# SCH_DV_MR_rev_modbus_18_16_2022-01-16.net
KiCad netlist of a schematic drawn in EasyEDA
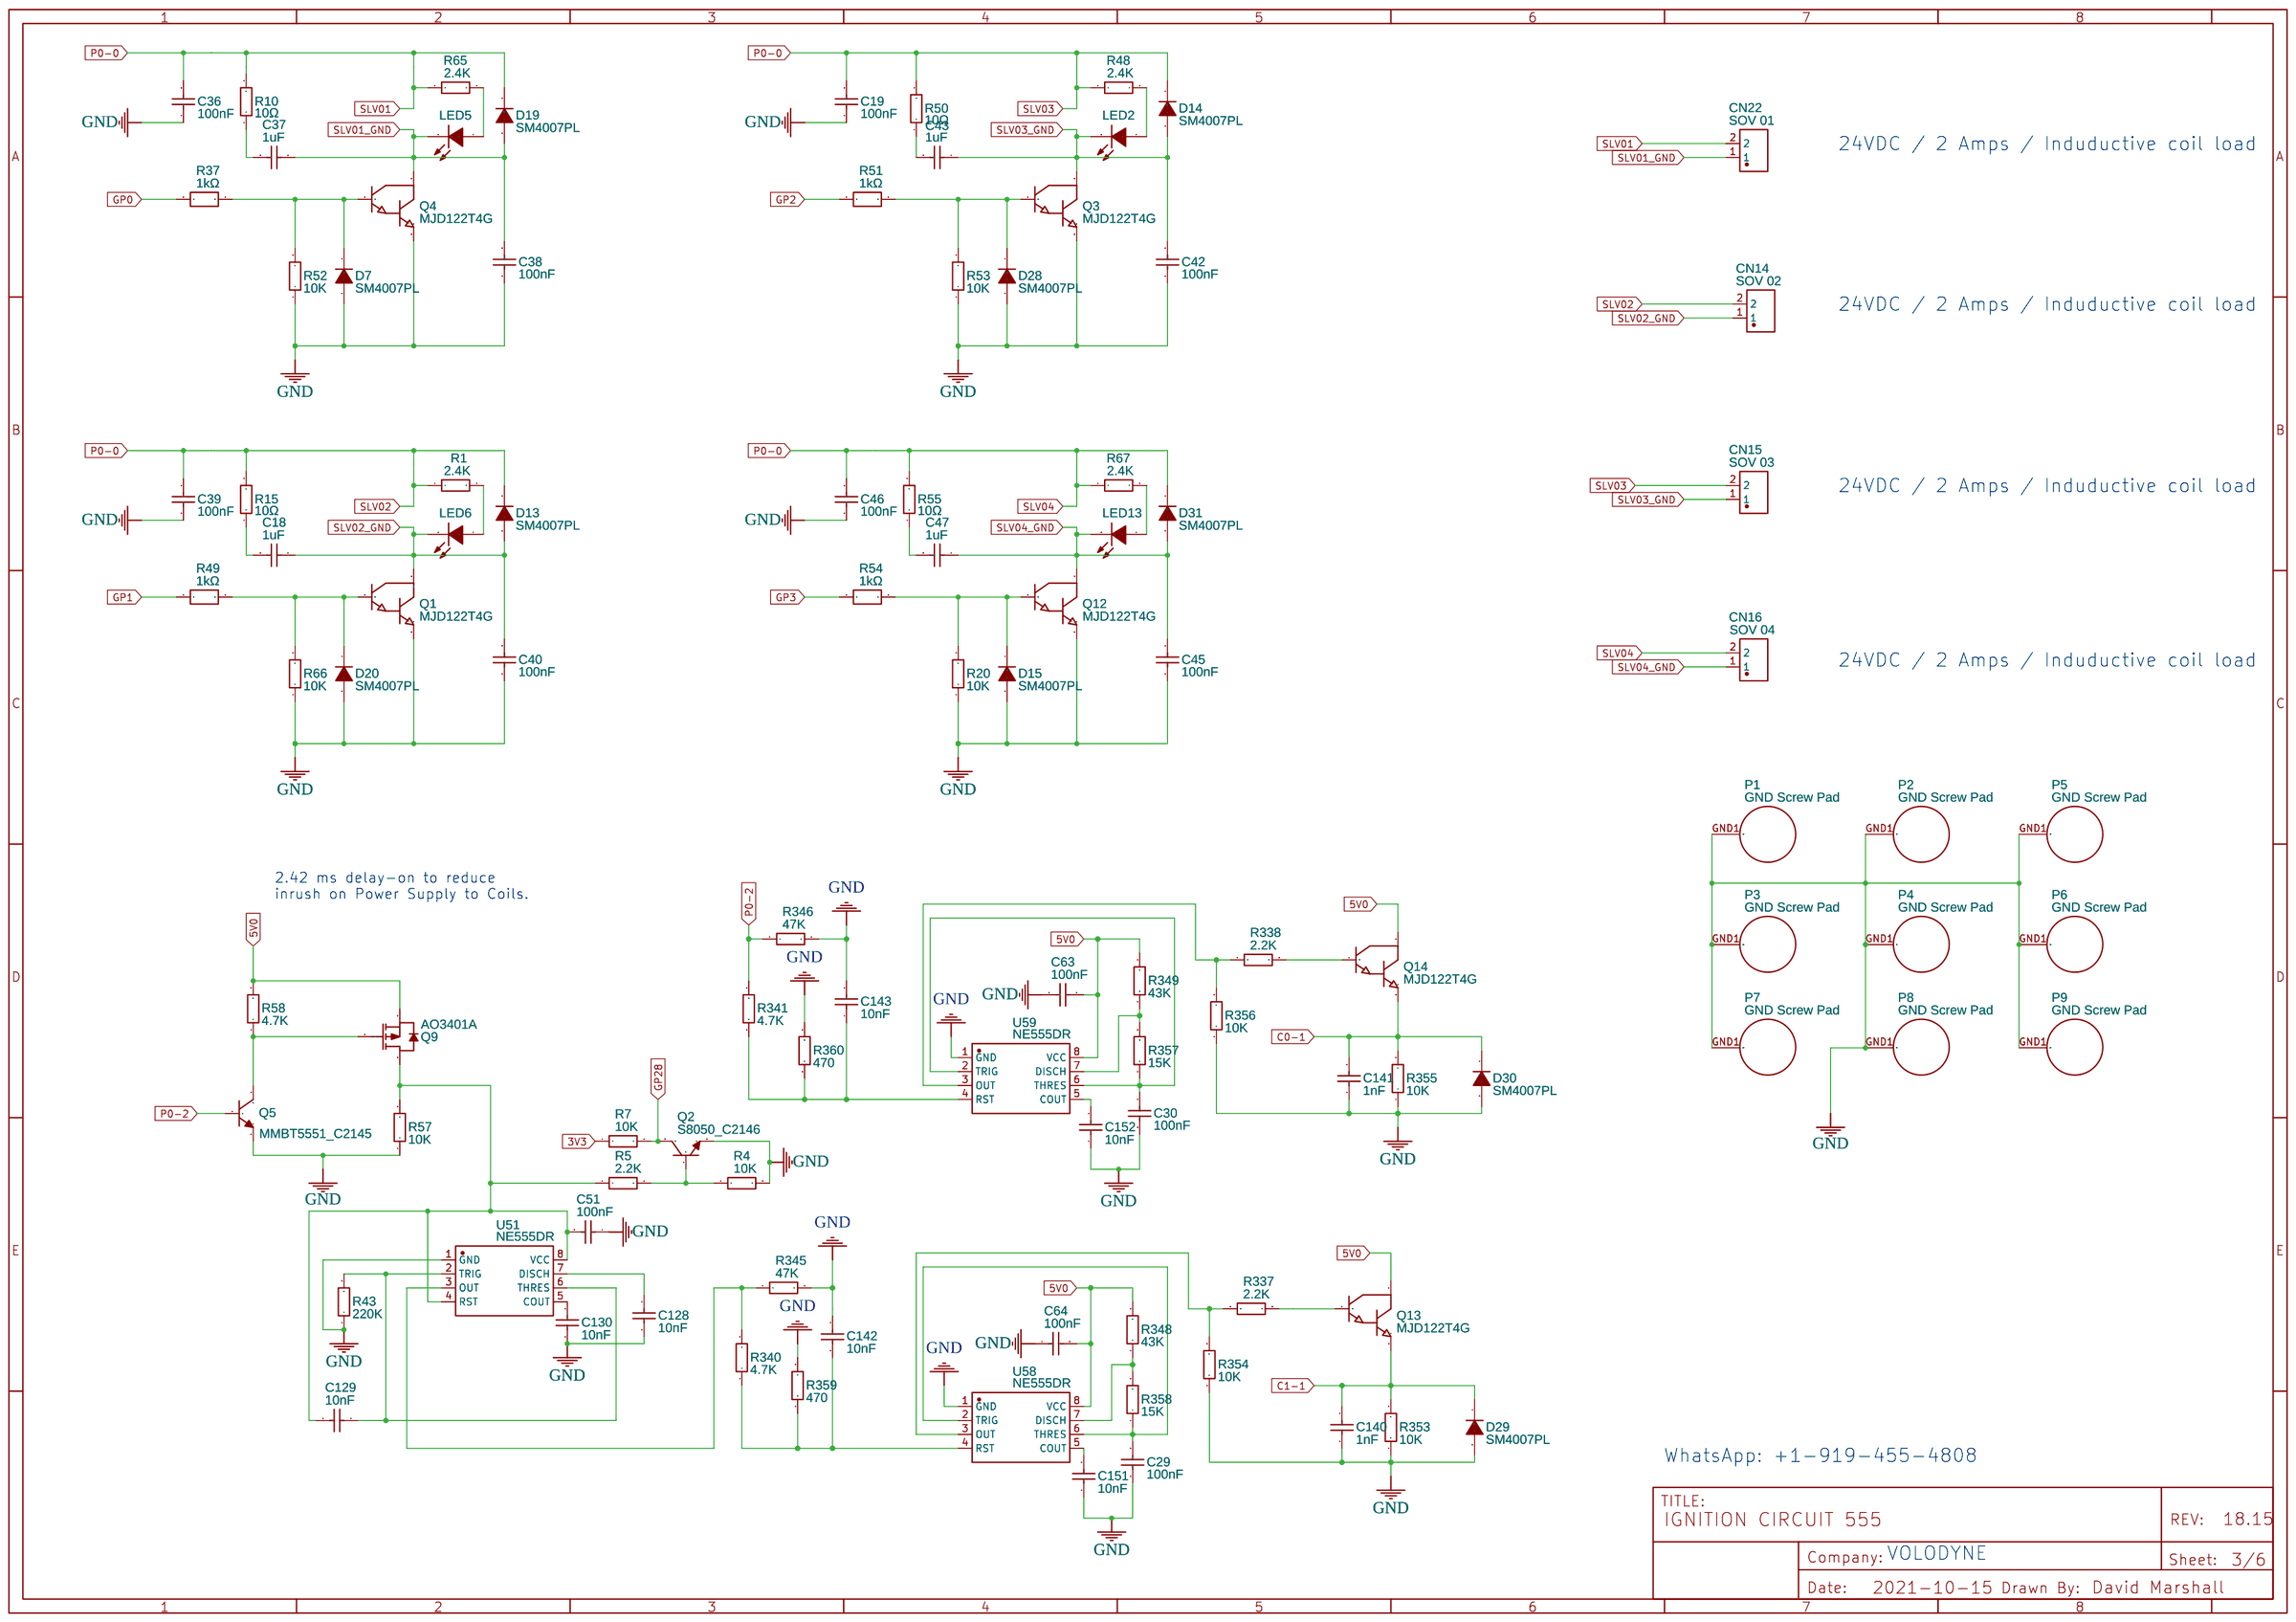
[diagram p0: DV_MR_rev_18.16_modbus_ADC_555 COILER TIMERS]
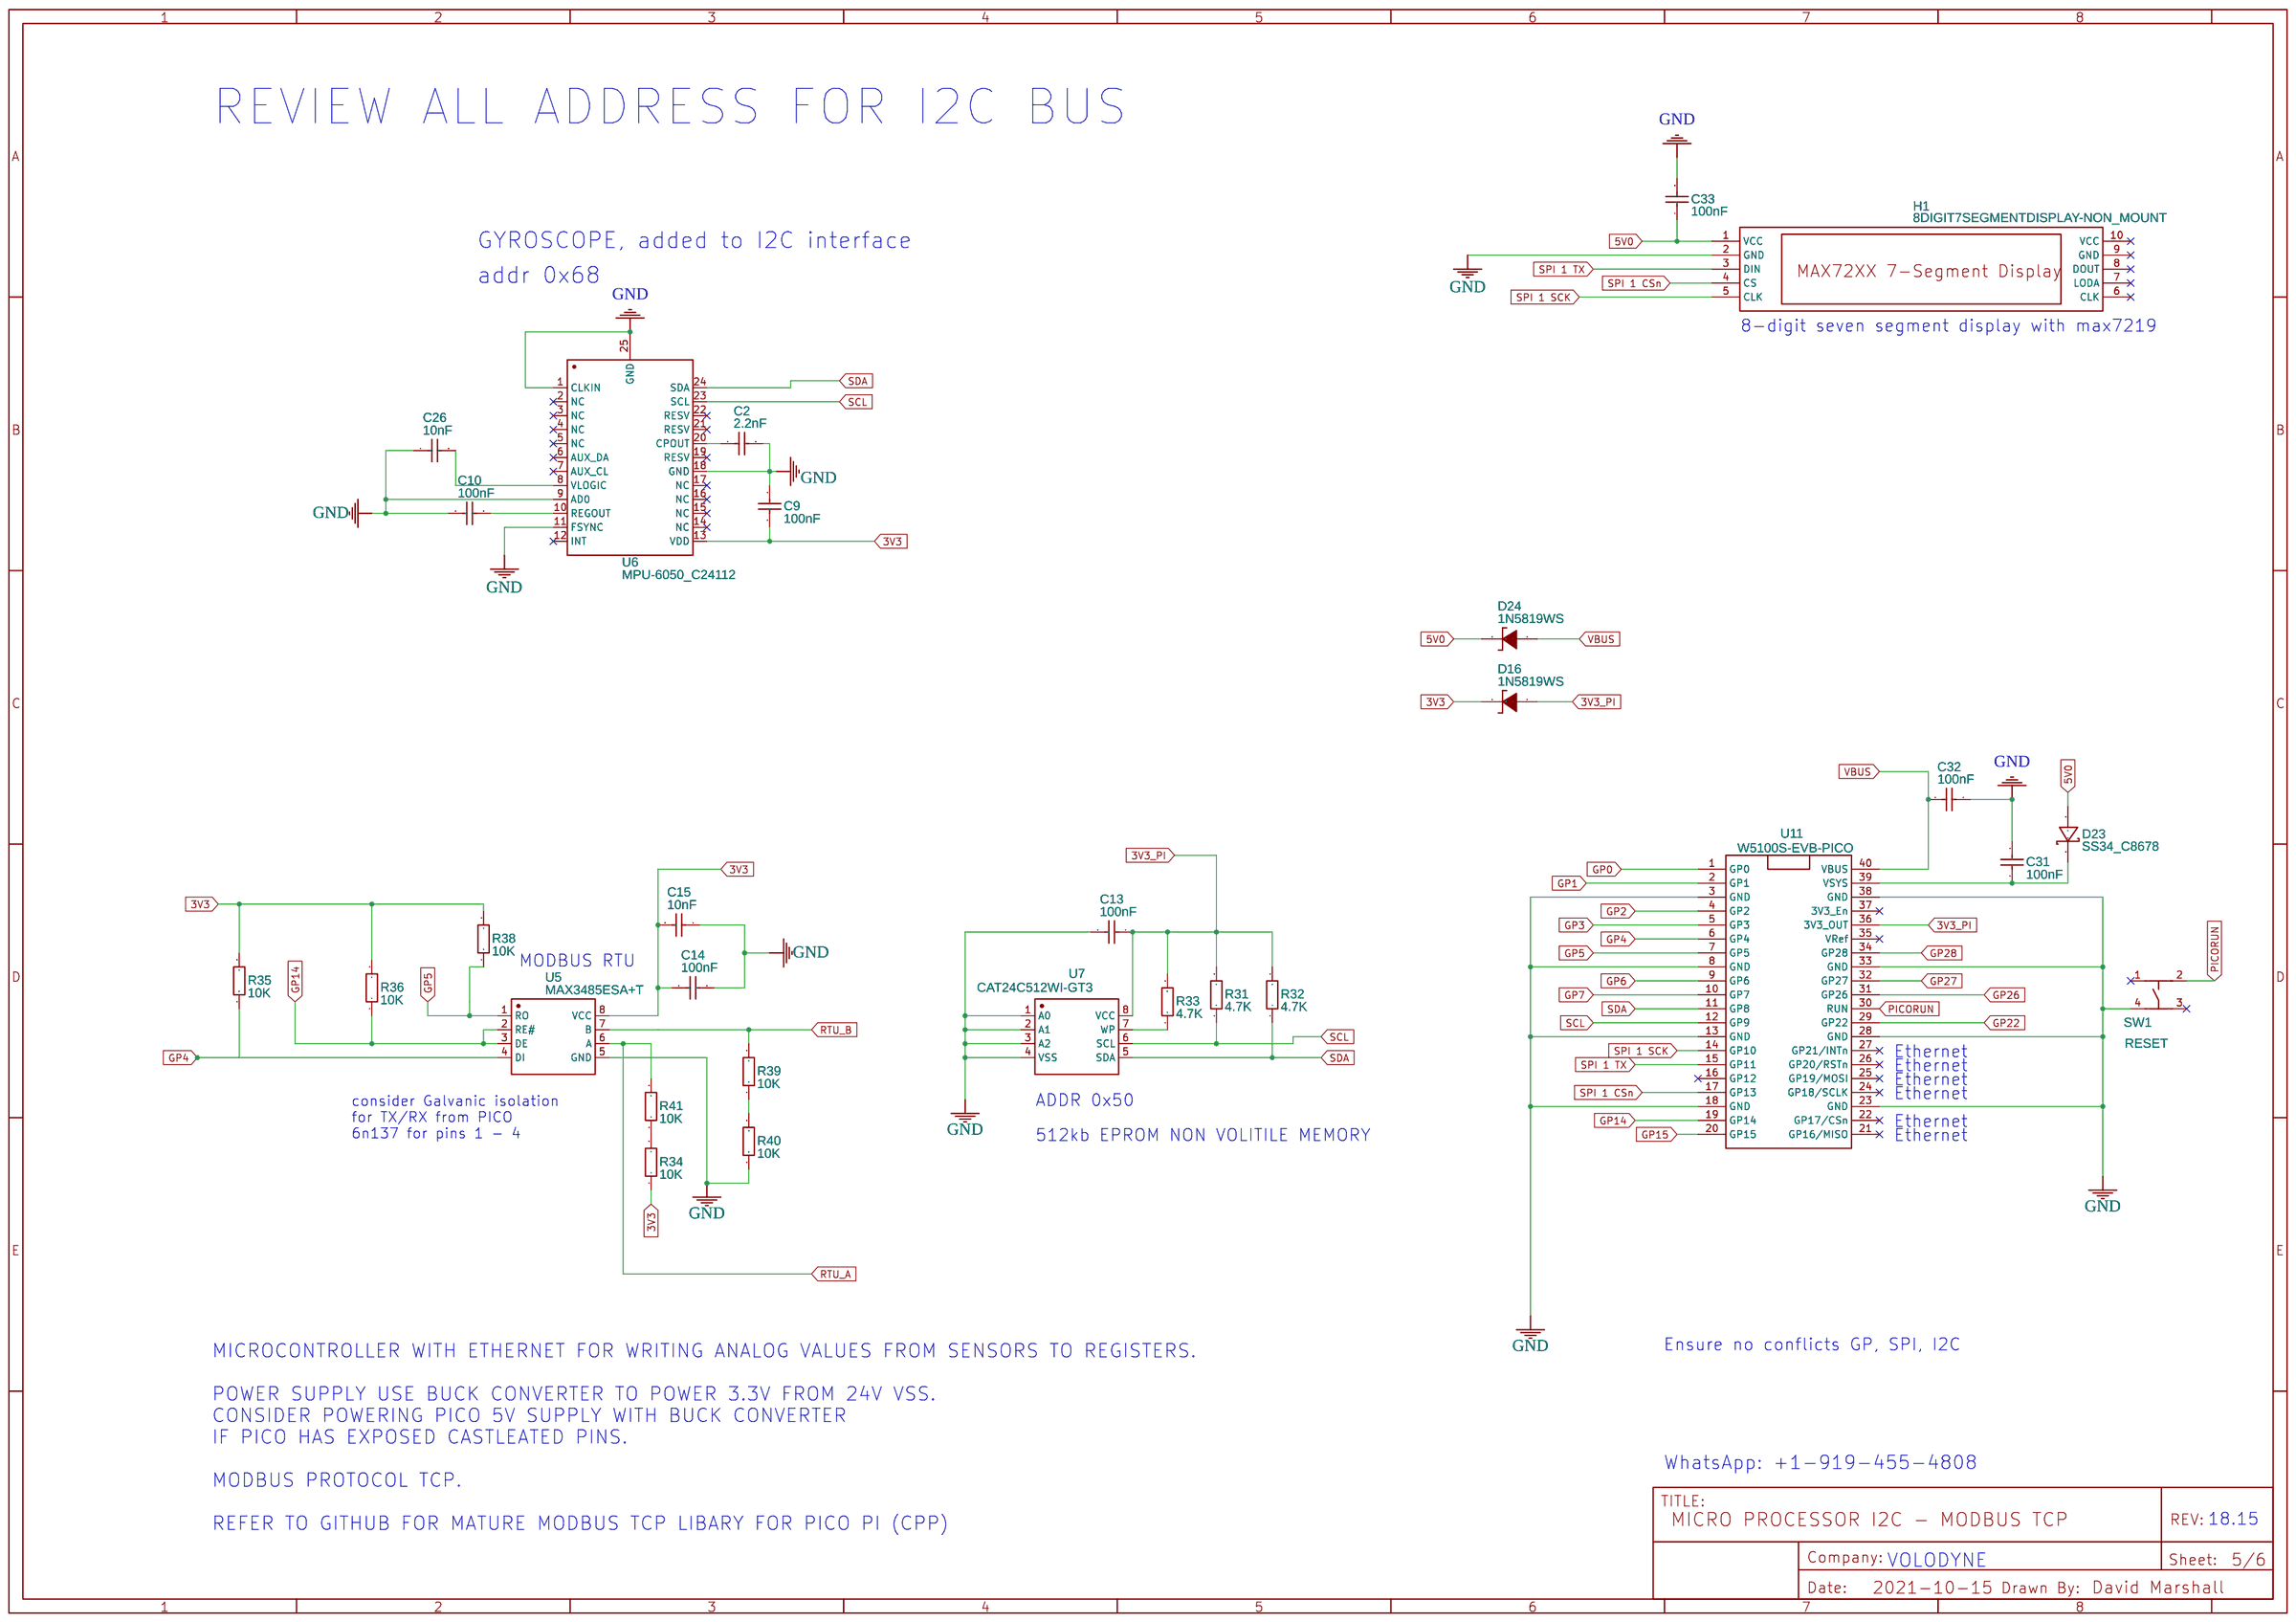
[diagram p1: DV_MR_rev_18.16_modbus_ADC_PICO PI MCU]
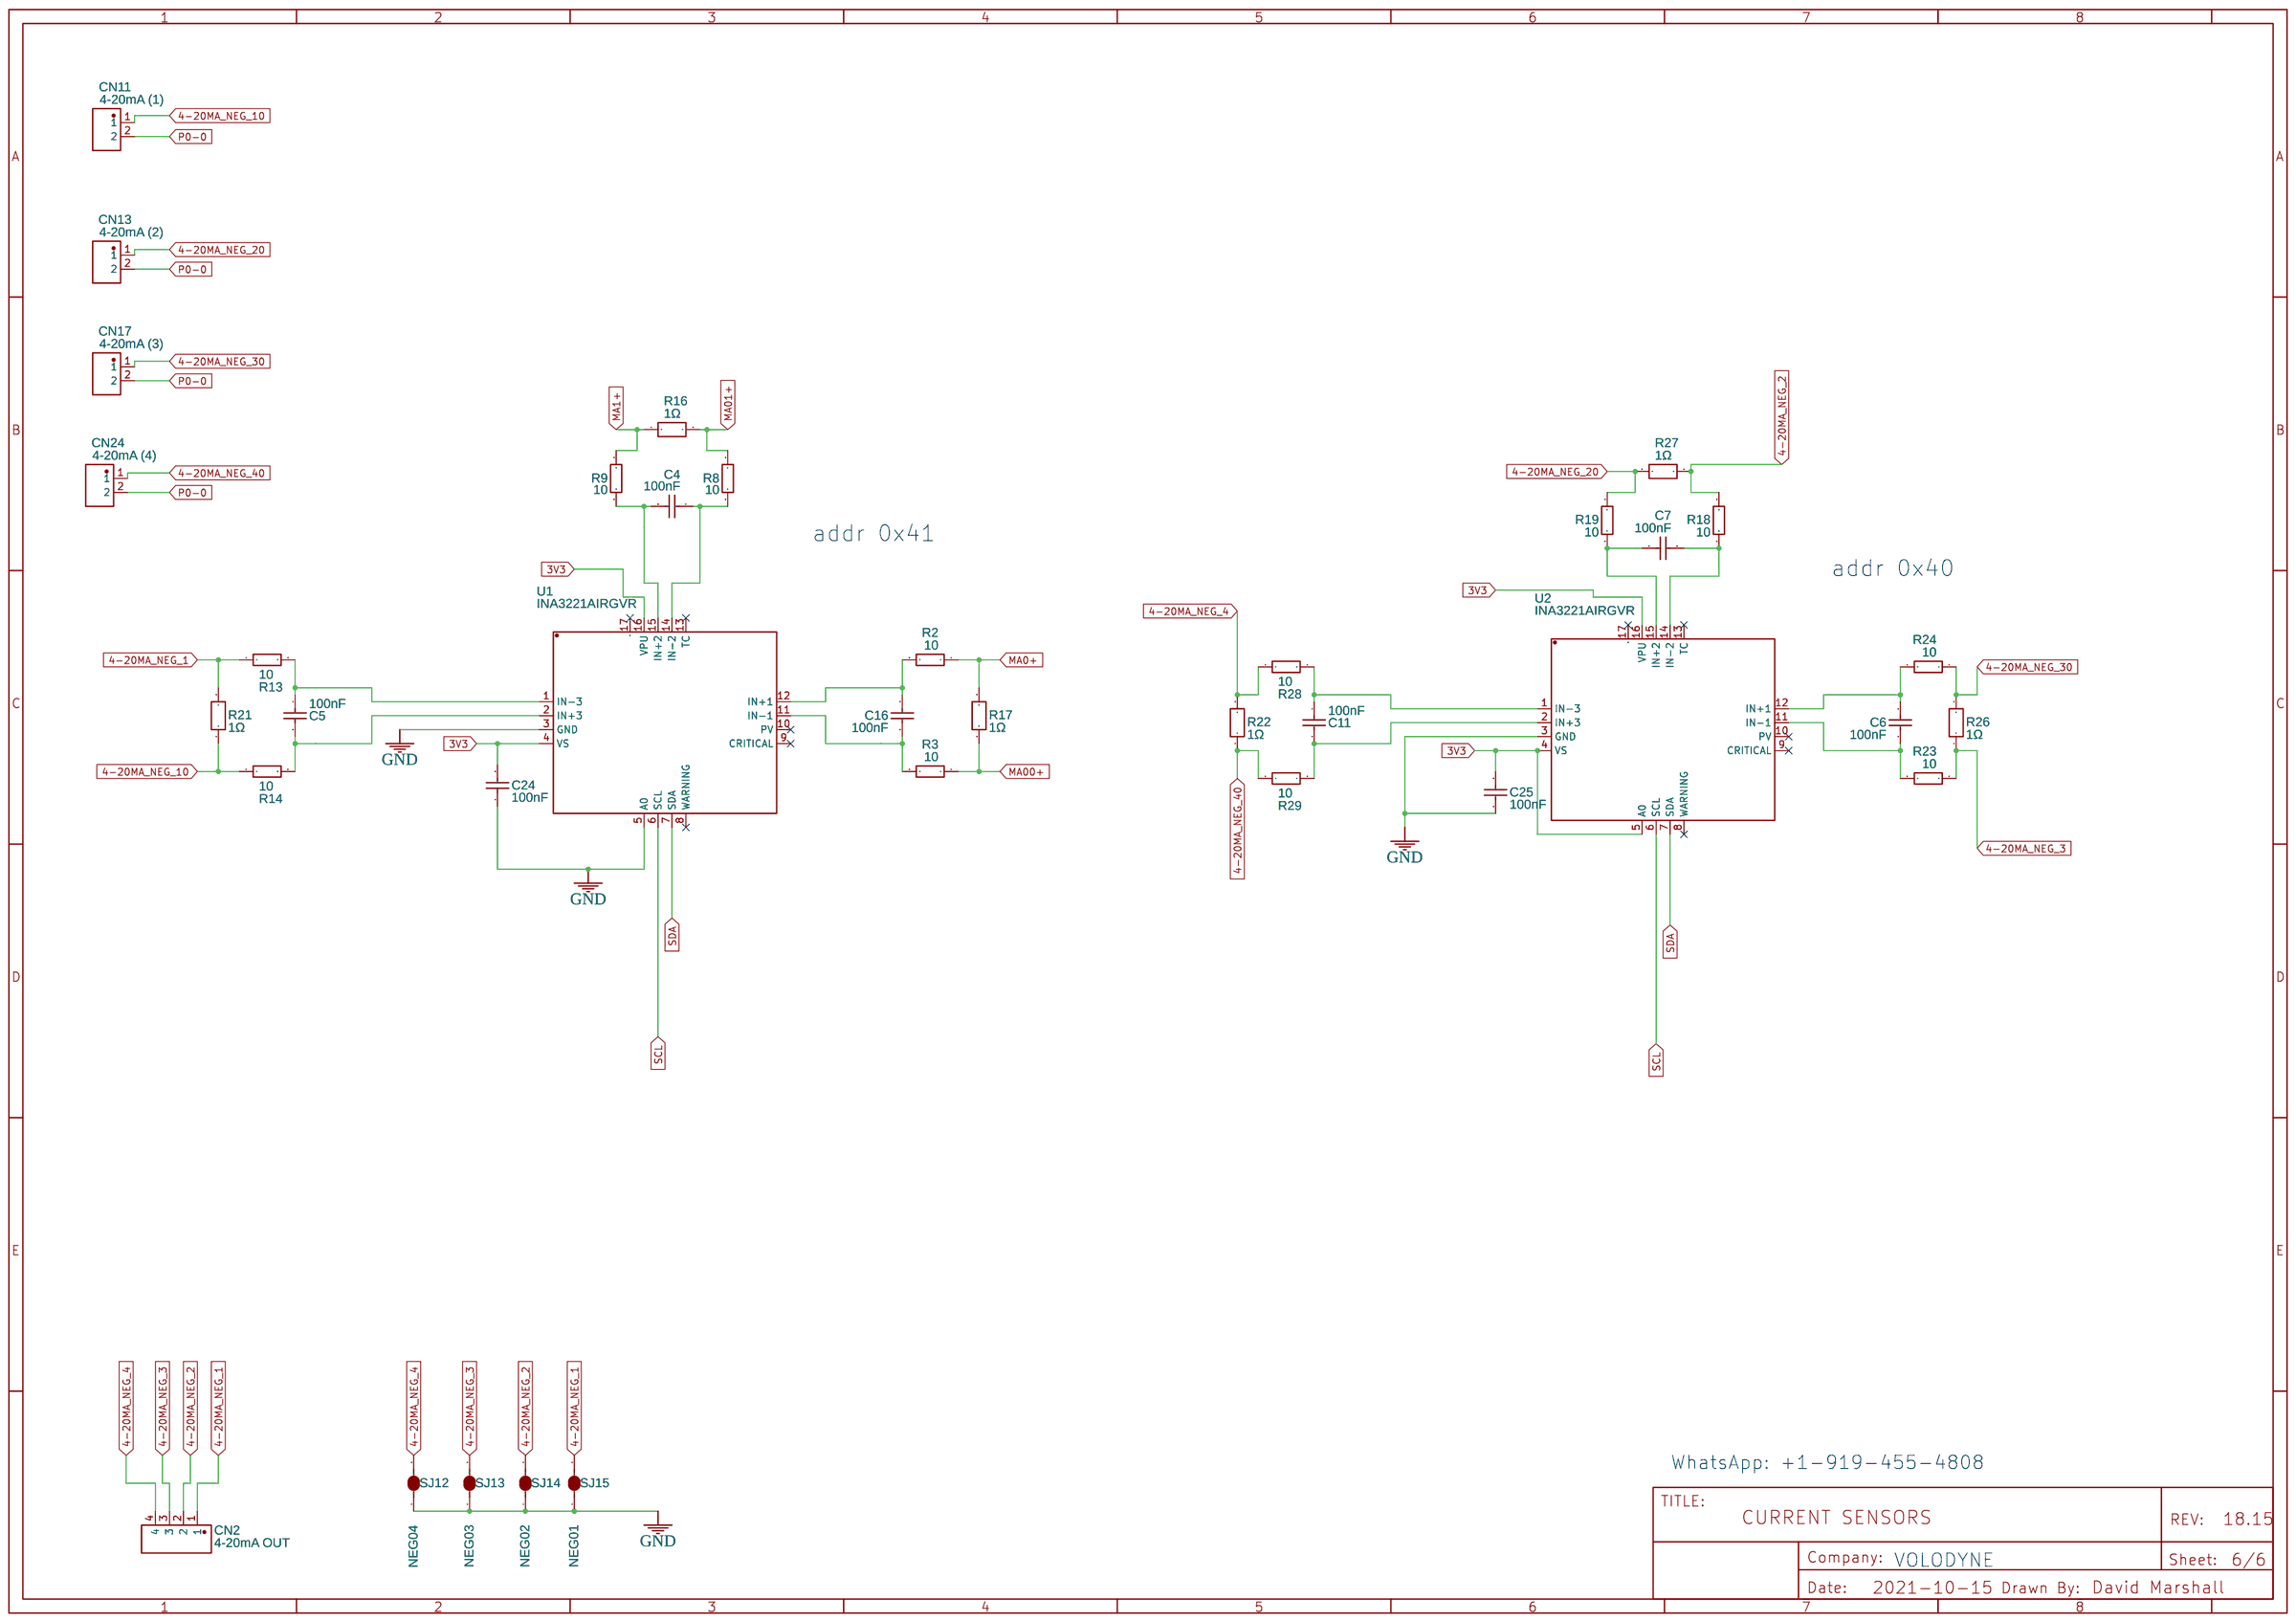
[diagram p2: DV_MR_rev_18.16_modbus_ADC_CURRENT SENSORS]
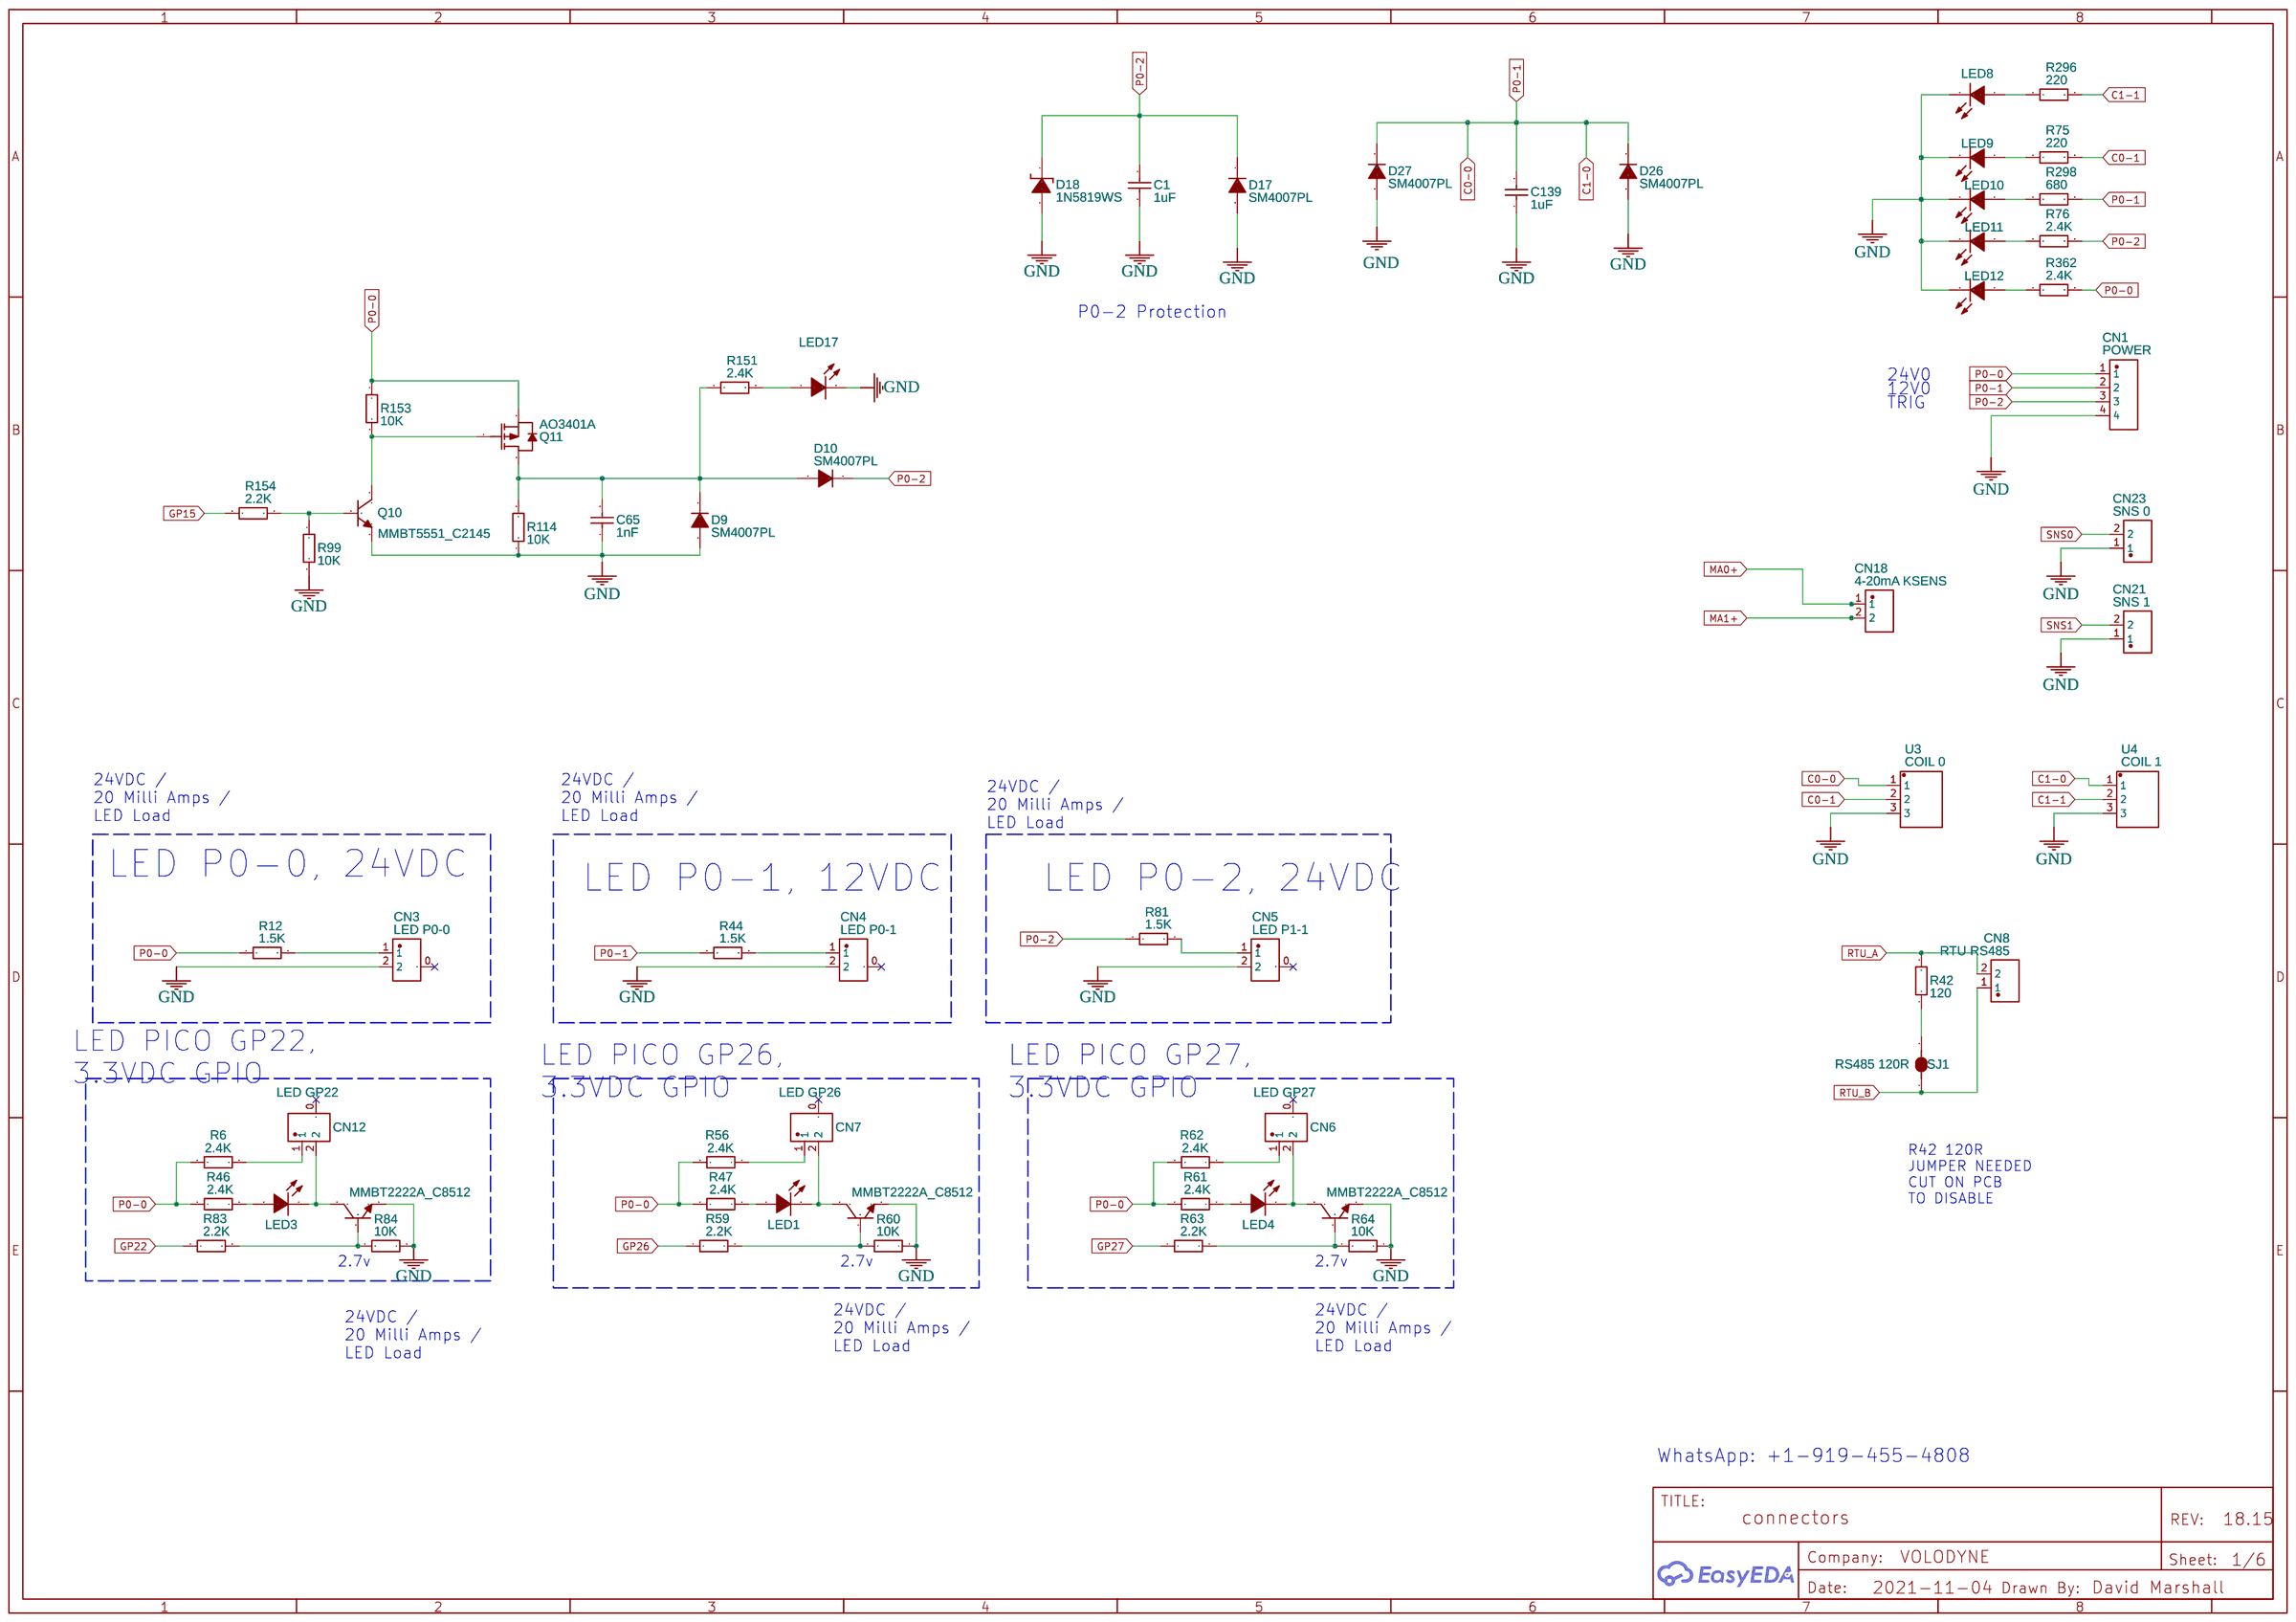
[diagram p3: DV_MR_rev_18.16_modbus_ADC_Connectors]
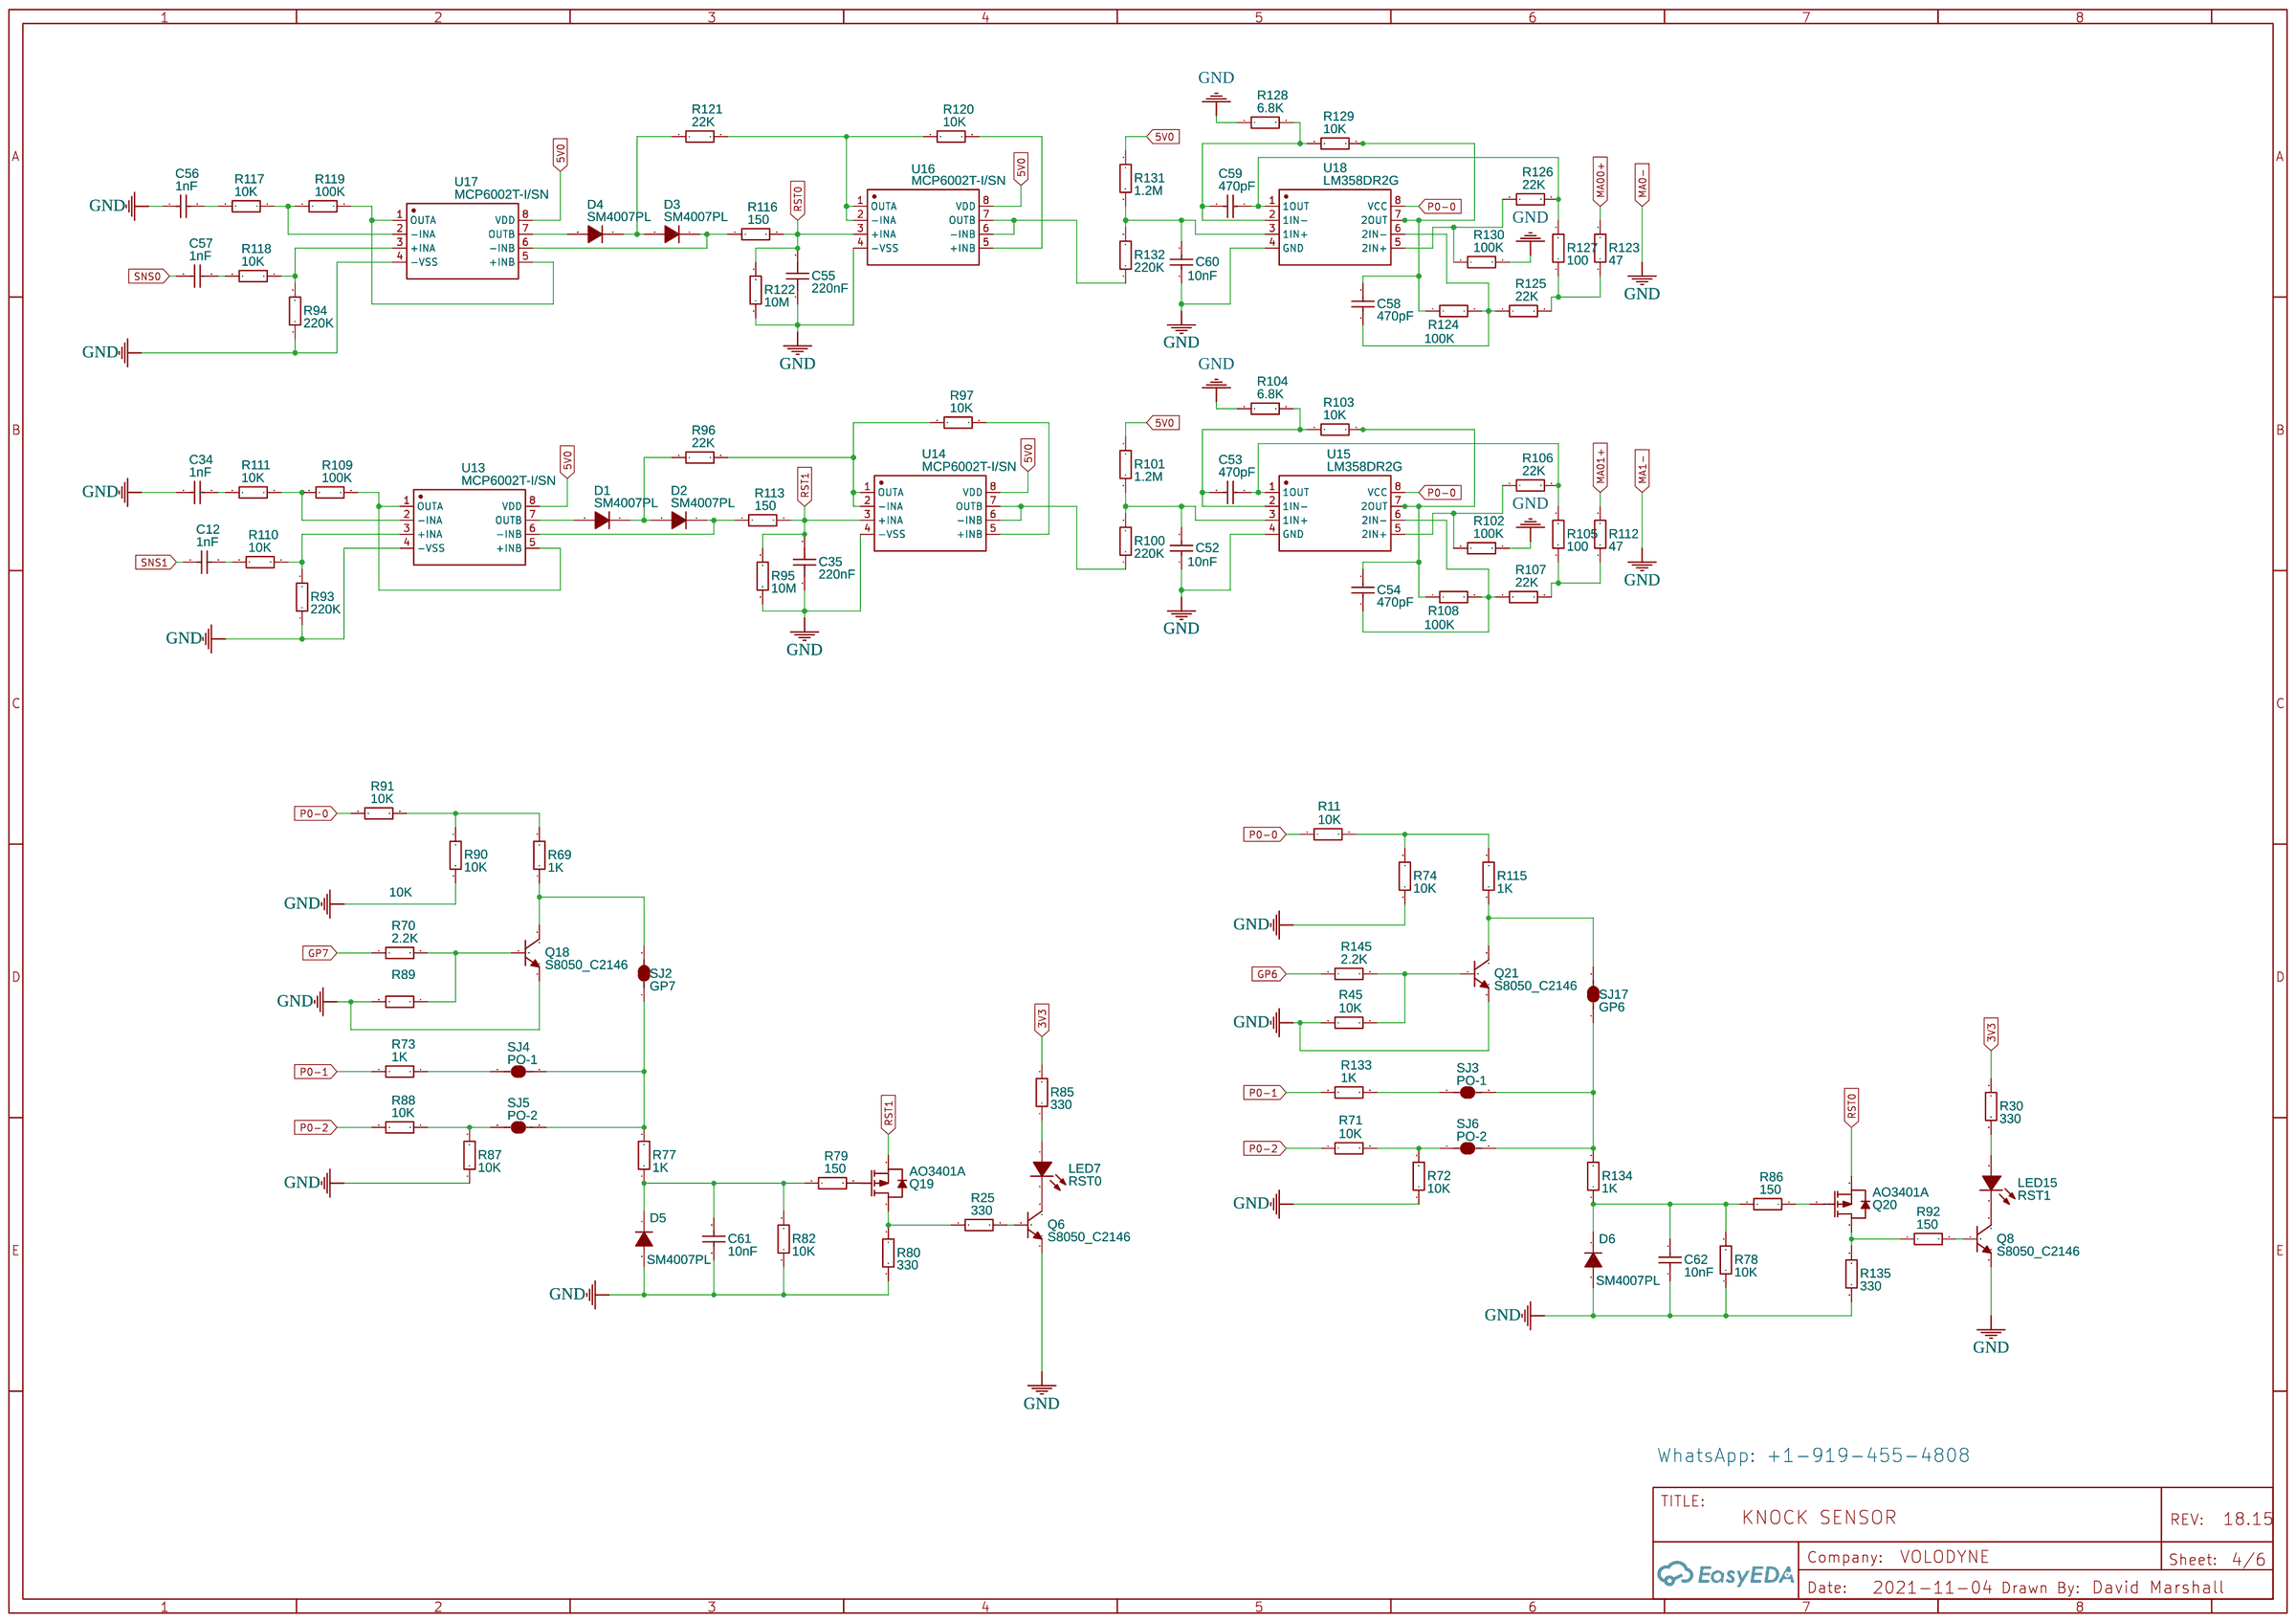
[diagram p4: DV_MR_rev_18.16_modbus_ADC_IGN SENSORS]
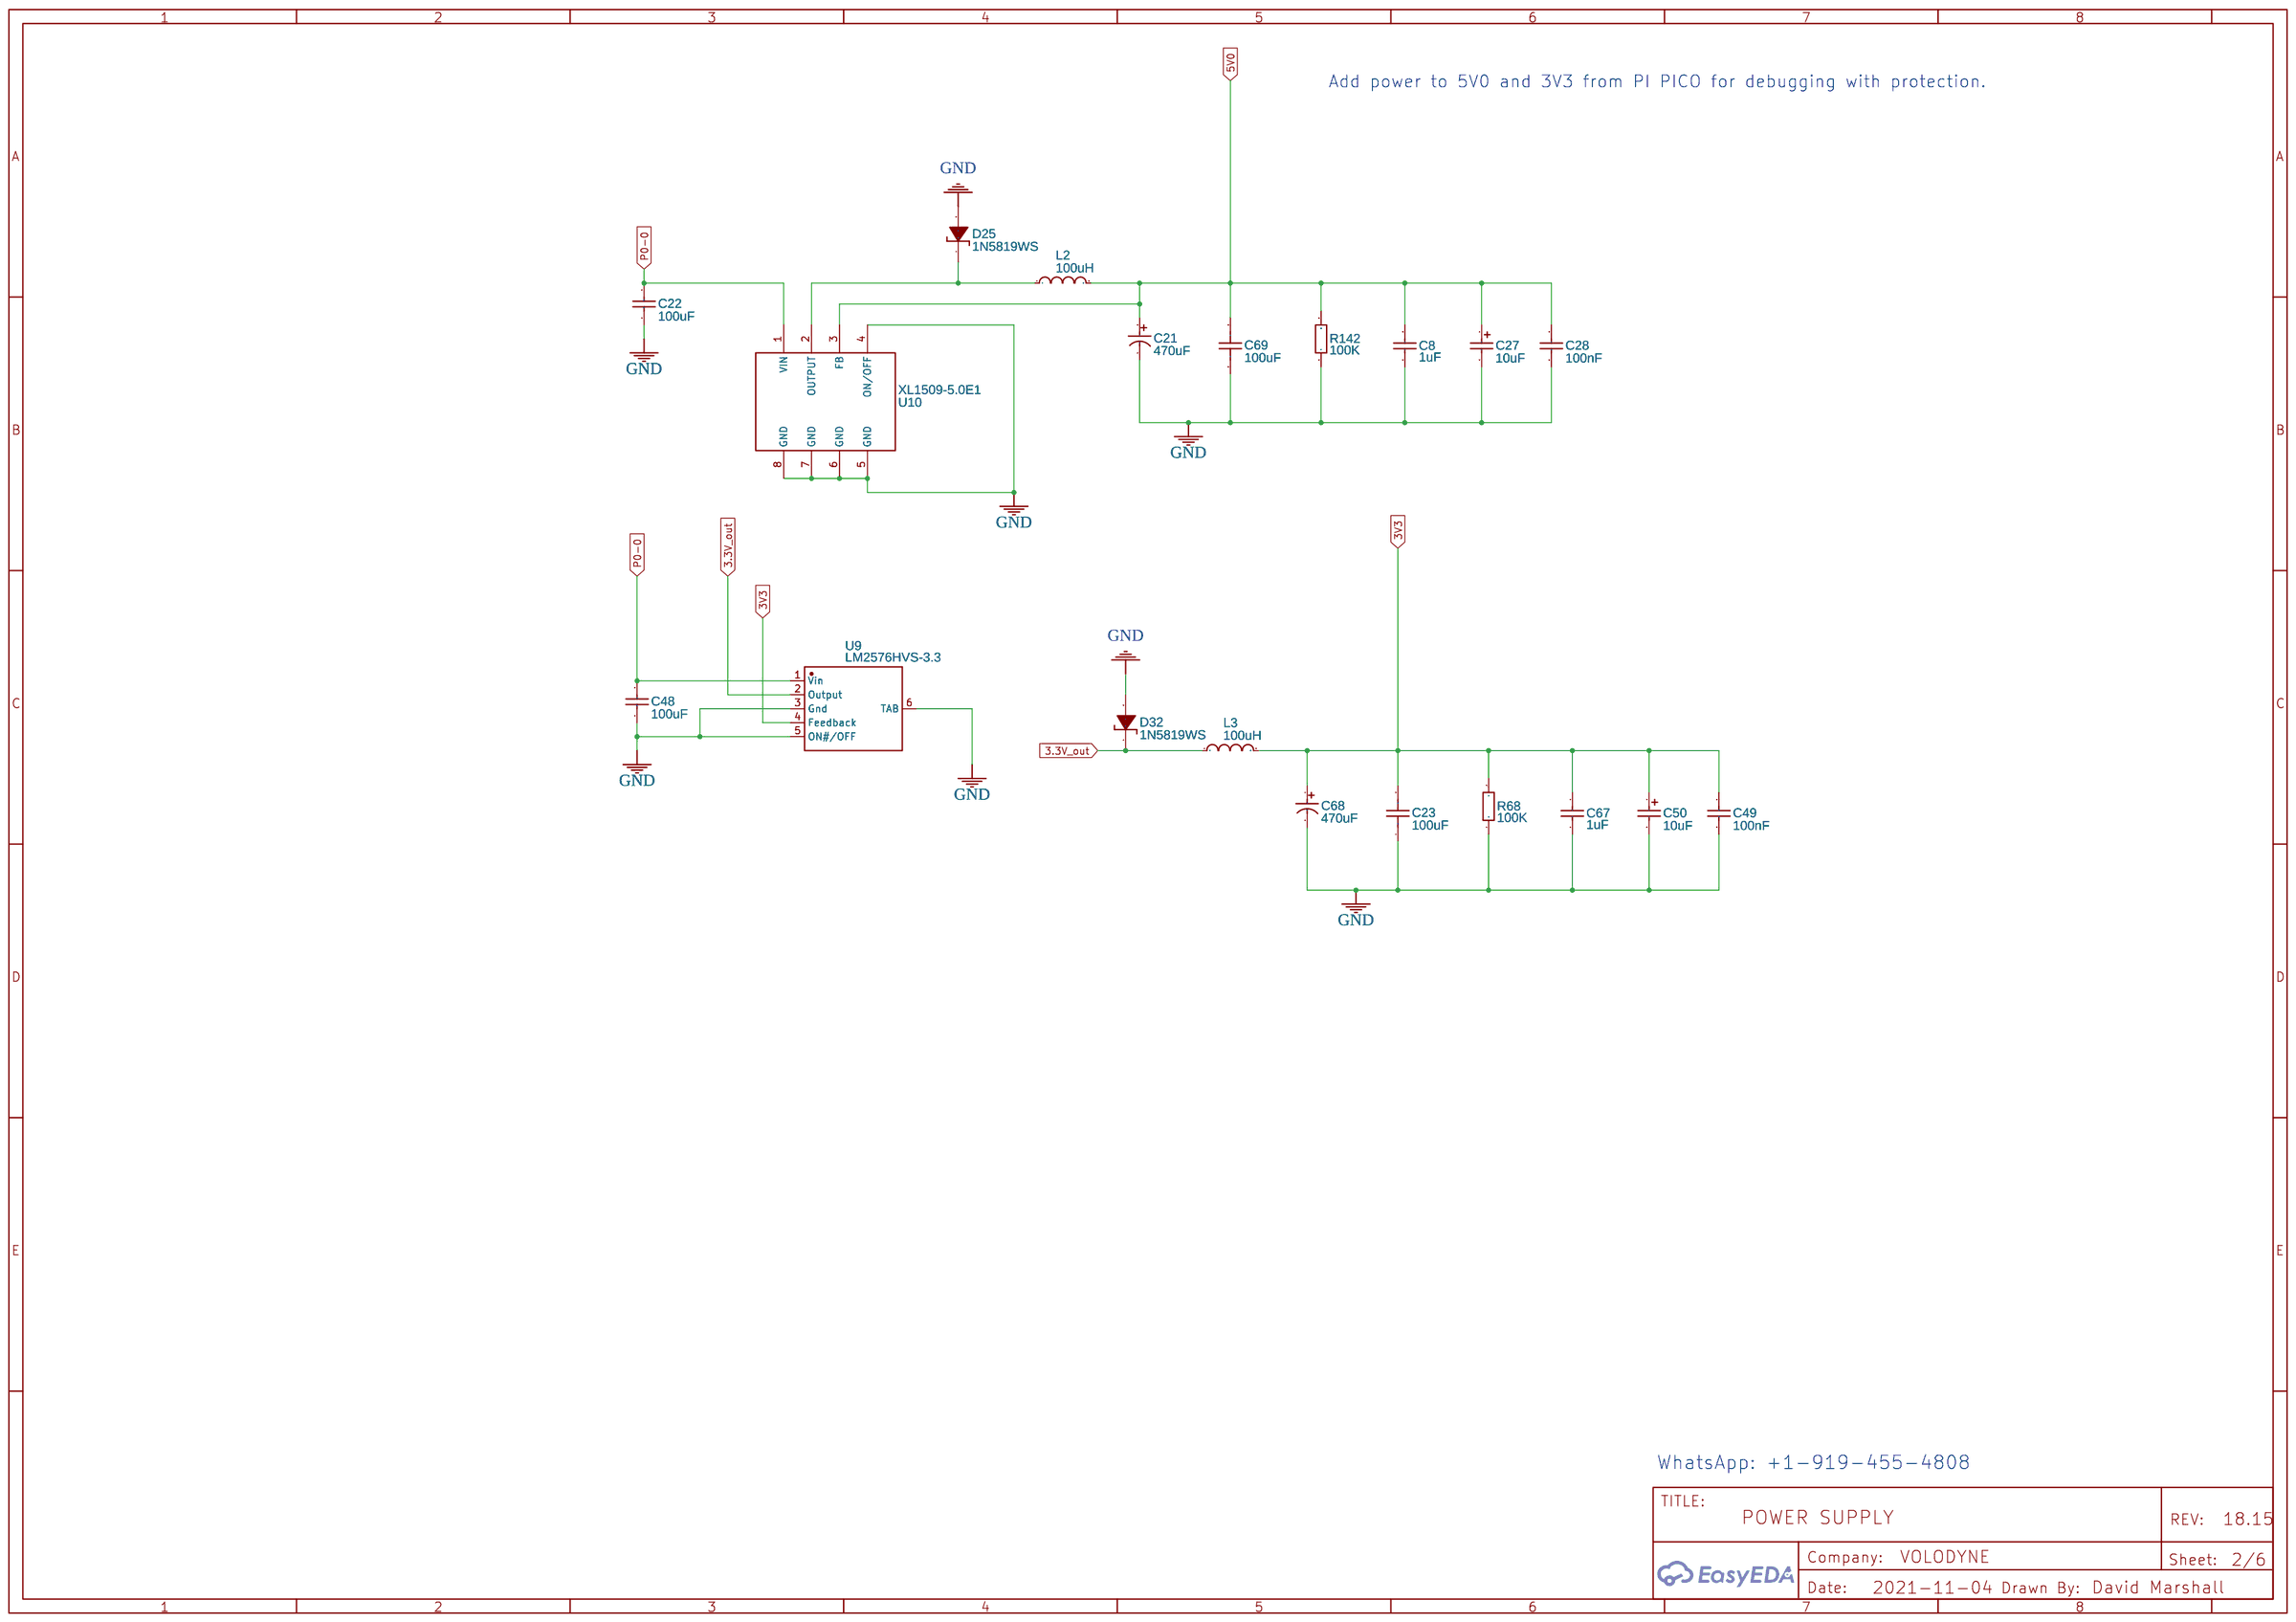
[diagram p5: DV_MR_rev_18.16_modbus_ADC_POWER]

(export (version "E")
  (design (tool "Eeschema 10.0.6"))
  (components
    (comp (ref "C18")
      (value "1uF")
      (fields
        (field (name "BOM_Manufacturer Part") "CL10A105KB8NNNC")
        (field (name "BOM_Supplier Part") "C15849")
      )
      (libsource (lib "") (part "CL10A105KB8NNNC"))
    )
    (comp (ref "C19")
      (value "100nF")
      (fields
        (field (name "BOM_Manufacturer Part") "CL05B104KO5NNNC")
        (field (name "BOM_Supplier Part") "C1525")
      )
      (libsource (lib "") (part "CL05B104KO5NNNC"))
    )
    (comp (ref "C29")
      (value "100nF")
      (fields
        (field (name "BOM_Manufacturer Part") "CL05B104KO5NNNC")
        (field (name "BOM_Supplier Part") "C1525")
      )
      (libsource (lib "") (part "CL05B104KO5NNNC"))
    )
    (comp (ref "C30")
      (value "100nF")
      (fields
        (field (name "BOM_Manufacturer Part") "CL05B104KO5NNNC")
        (field (name "BOM_Supplier Part") "C1525")
      )
      (libsource (lib "") (part "CL05B104KO5NNNC"))
    )
    (comp (ref "C36")
      (value "100nF")
      (fields
        (field (name "BOM_Manufacturer Part") "CL05B104KO5NNNC")
        (field (name "BOM_Supplier Part") "C1525")
      )
      (libsource (lib "") (part "CL05B104KO5NNNC"))
    )
    (comp (ref "C37")
      (value "1uF")
      (fields
        (field (name "BOM_Manufacturer Part") "CL10A105KB8NNNC")
        (field (name "BOM_Supplier Part") "C15849")
      )
      (libsource (lib "") (part "CL10A105KB8NNNC"))
    )
    (comp (ref "C38")
      (value "100nF")
      (fields
        (field (name "BOM_Manufacturer Part") "CL05B104KO5NNNC")
        (field (name "BOM_Supplier Part") "C1525")
      )
      (libsource (lib "") (part "CL05B104KO5NNNC"))
    )
    (comp (ref "C39")
      (value "100nF")
      (fields
        (field (name "BOM_Manufacturer Part") "CL05B104KO5NNNC")
        (field (name "BOM_Supplier Part") "C1525")
      )
      (libsource (lib "") (part "CL05B104KO5NNNC"))
    )
    (comp (ref "C40")
      (value "100nF")
      (fields
        (field (name "BOM_Manufacturer Part") "CL05B104KO5NNNC")
        (field (name "BOM_Supplier Part") "C1525")
      )
      (libsource (lib "") (part "CL05B104KO5NNNC"))
    )
    (comp (ref "C42")
      (value "100nF")
      (fields
        (field (name "BOM_Manufacturer Part") "CL05B104KO5NNNC")
        (field (name "BOM_Supplier Part") "C1525")
      )
      (libsource (lib "") (part "CL05B104KO5NNNC"))
    )
    (comp (ref "C43")
      (value "1uF")
      (fields
        (field (name "BOM_Manufacturer Part") "CL10A105KB8NNNC")
        (field (name "BOM_Supplier Part") "C15849")
      )
      (libsource (lib "") (part "CL10A105KB8NNNC"))
    )
    (comp (ref "C45")
      (value "100nF")
      (fields
        (field (name "BOM_Manufacturer Part") "CL05B104KO5NNNC")
        (field (name "BOM_Supplier Part") "C1525")
      )
      (libsource (lib "") (part "CL05B104KO5NNNC"))
    )
    (comp (ref "C46")
      (value "100nF")
      (fields
        (field (name "BOM_Manufacturer Part") "CL05B104KO5NNNC")
        (field (name "BOM_Supplier Part") "C1525")
      )
      (libsource (lib "") (part "CL05B104KO5NNNC"))
    )
    (comp (ref "C47")
      (value "1uF")
      (fields
        (field (name "BOM_Manufacturer Part") "CL10A105KB8NNNC")
        (field (name "BOM_Supplier Part") "C15849")
      )
      (libsource (lib "") (part "CL10A105KB8NNNC"))
    )
    (comp (ref "C51")
      (value "100nF")
      (fields
        (field (name "BOM_Manufacturer Part") "CL05B104KO5NNNC")
        (field (name "BOM_Supplier Part") "C1525")
      )
      (libsource (lib "") (part "CL05B104KO5NNNC_2"))
    )
    (comp (ref "C63")
      (value "100nF")
      (fields
        (field (name "BOM_Manufacturer Part") "CL05B104KO5NNNC")
        (field (name "BOM_Supplier Part") "C1525")
      )
      (libsource (lib "") (part "CL05B104KO5NNNC_1"))
    )
    (comp (ref "C64")
      (value "100nF")
      (fields
        (field (name "BOM_Manufacturer Part") "CL05B104KO5NNNC")
        (field (name "BOM_Supplier Part") "C1525")
      )
      (libsource (lib "") (part "CL05B104KO5NNNC_1"))
    )
    (comp (ref "C128")
      (value "10nF")
      (fields
        (field (name "BOM_Manufacturer Part") "0603B103K500NT")
        (field (name "BOM_Supplier Part") "C57112")
      )
      (libsource (lib "") (part "0603B103K500NT_2"))
    )
    (comp (ref "C129")
      (value "10nF")
      (fields
        (field (name "BOM_Manufacturer Part") "0603B103K500NT")
        (field (name "BOM_Supplier Part") "C57112")
      )
      (libsource (lib "") (part "0603B103K500NT_1"))
    )
    (comp (ref "C130")
      (value "10nF")
      (fields
        (field (name "BOM_Manufacturer Part") "0603B103K500NT")
        (field (name "BOM_Supplier Part") "C57112")
      )
      (libsource (lib "") (part "0603B103K500NT_2"))
    )
    (comp (ref "C140")
      (value "1nF")
      (fields
        (field (name "BOM_Manufacturer Part") "0402B102K500NT")
        (field (name "BOM_Supplier Part") "C1523")
      )
      (libsource (lib "") (part "0402B102K500NT"))
    )
    (comp (ref "C141")
      (value "1nF")
      (fields
        (field (name "BOM_Manufacturer Part") "0402B102K500NT")
        (field (name "BOM_Supplier Part") "C1523")
      )
      (libsource (lib "") (part "0402B102K500NT"))
    )
    (comp (ref "C142")
      (value "10nF")
      (fields
        (field (name "BOM_Manufacturer Part") "0603B103K500NT")
        (field (name "BOM_Supplier Part") "C57112")
      )
      (libsource (lib "") (part "0603B103K500NT"))
    )
    (comp (ref "C143")
      (value "10nF")
      (fields
        (field (name "BOM_Manufacturer Part") "0603B103K500NT")
        (field (name "BOM_Supplier Part") "C57112")
      )
      (libsource (lib "") (part "0603B103K500NT"))
    )
    (comp (ref "C151")
      (value "10nF")
      (fields
        (field (name "BOM_Manufacturer Part") "0603B103K500NT")
        (field (name "BOM_Supplier Part") "C57112")
      )
      (libsource (lib "") (part "0603B103K500NT"))
    )
    (comp (ref "C152")
      (value "10nF")
      (fields
        (field (name "BOM_Manufacturer Part") "0603B103K500NT")
        (field (name "BOM_Supplier Part") "C57112")
      )
      (libsource (lib "") (part "0603B103K500NT"))
    )
    (comp (ref "CN14")
      (value "SOV 02")
      (fields
        (field (name "BOM_Manufacturer Part") "15EDGVM-3.81-02P-14-00A(H)")
        (field (name "BOM_Supplier Part") "C507020")
      )
      (libsource (lib "") (part "15EDGVM-3.81-02P-14-00A(H)"))
    )
    (comp (ref "CN15")
      (value "SOV 03")
      (fields
        (field (name "BOM_Manufacturer Part") "15EDGVM-3.81-02P-14-00A(H)")
        (field (name "BOM_Supplier Part") "C507020")
      )
      (libsource (lib "") (part "15EDGVM-3.81-02P-14-00A(H)"))
    )
    (comp (ref "CN16")
      (value "SOV 04")
      (fields
        (field (name "BOM_Manufacturer Part") "15EDGVM-3.81-02P-14-00A(H)")
        (field (name "BOM_Supplier Part") "C507020")
      )
      (libsource (lib "") (part "15EDGVM-3.81-02P-14-00A(H)"))
    )
    (comp (ref "CN22")
      (value "SOV 01")
      (fields
        (field (name "BOM_Manufacturer Part") "15EDGVM-3.81-02P-14-00A(H)")
        (field (name "BOM_Supplier Part") "C507020")
      )
      (libsource (lib "") (part "15EDGVM-3.81-02P-14-00A(H)"))
    )
    (comp (ref "D7")
      (value "SM4007PL")
      (fields (field (name "BOM_Supplier Part") "C64898"))
      (libsource (lib "") (part "SM4007PL"))
    )
    (comp (ref "D13")
      (value "SM4007PL")
      (fields (field (name "BOM_Supplier Part") "C64898"))
      (libsource (lib "") (part "SM4007PL"))
    )
    (comp (ref "D14")
      (value "SM4007PL")
      (fields (field (name "BOM_Supplier Part") "C64898"))
      (libsource (lib "") (part "SM4007PL"))
    )
    (comp (ref "D15")
      (value "SM4007PL")
      (fields (field (name "BOM_Supplier Part") "C64898"))
      (libsource (lib "") (part "SM4007PL"))
    )
    (comp (ref "D19")
      (value "SM4007PL")
      (fields (field (name "BOM_Supplier Part") "C64898"))
      (libsource (lib "") (part "SM4007PL"))
    )
    (comp (ref "D20")
      (value "SM4007PL")
      (fields (field (name "BOM_Supplier Part") "C64898"))
      (libsource (lib "") (part "SM4007PL"))
    )
    (comp (ref "D28")
      (value "SM4007PL")
      (fields (field (name "BOM_Supplier Part") "C64898"))
      (libsource (lib "") (part "SM4007PL"))
    )
    (comp (ref "D29")
      (value "SM4007PL")
      (fields (field (name "BOM_Supplier Part") "C64898"))
      (libsource (lib "") (part "SM4007PL"))
    )
    (comp (ref "D30")
      (value "SM4007PL")
      (fields (field (name "BOM_Supplier Part") "C64898"))
      (libsource (lib "") (part "SM4007PL"))
    )
    (comp (ref "D31")
      (value "SM4007PL")
      (fields (field (name "BOM_Supplier Part") "C64898"))
      (libsource (lib "") (part "SM4007PL"))
    )
    (comp (ref "LED2")
      (value "SLV03")
      (fields (field (name "BOM_Manufacturer Part") "KT-0603R") (field (name "BOM_Supplier Part") "C2286"))
      (libsource (lib "") (part "KT-0603R"))
    )
    (comp (ref "LED5")
      (value "SLV01")
      (fields (field (name "BOM_Manufacturer Part") "KT-0603R") (field (name "BOM_Supplier Part") "C2286"))
      (libsource (lib "") (part "KT-0603R"))
    )
    (comp (ref "LED6")
      (value "SLV02")
      (fields (field (name "BOM_Manufacturer Part") "KT-0603R") (field (name "BOM_Supplier Part") "C2286"))
      (libsource (lib "") (part "KT-0603R"))
    )
    (comp (ref "LED13")
      (value "SLV04")
      (fields (field (name "BOM_Manufacturer Part") "KT-0603R") (field (name "BOM_Supplier Part") "C2286"))
      (libsource (lib "") (part "KT-0603R"))
    )
    (comp (ref "P1") (value "GND Screw Pad") (libsource (lib "") (part "GND Screw Pad")))
    (comp (ref "P2") (value "GND Screw Pad") (libsource (lib "") (part "GND Screw Pad")))
    (comp (ref "P3") (value "GND Screw Pad") (libsource (lib "") (part "GND Screw Pad_1")))
    (comp (ref "P4") (value "GND Screw Pad") (libsource (lib "") (part "GND Screw Pad_1")))
    (comp (ref "P5") (value "GND Screw Pad") (libsource (lib "") (part "GND Screw Pad")))
    (comp (ref "P6") (value "GND Screw Pad") (libsource (lib "") (part "GND Screw Pad_1")))
    (comp (ref "P7") (value "GND Screw Pad") (libsource (lib "") (part "GND Screw Pad_2")))
    (comp (ref "P8") (value "GND Screw Pad") (libsource (lib "") (part "GND Screw Pad_2")))
    (comp (ref "P9") (value "GND Screw Pad") (libsource (lib "") (part "GND Screw Pad_2")))
    (comp (ref "Q1")
      (value "MJD122T4G")
      (fields (field (name "BOM_Supplier Part") "C12789"))
      (libsource (lib "") (part "MJD122T4G"))
    )
    (comp (ref "Q2")
      (value "S8050_C2146")
      (fields (field (name "BOM_Manufacturer Part") "S8050") (field (name "BOM_Supplier Part") "C2146"))
      (libsource (lib "") (part "S8050_C2146"))
    )
    (comp (ref "Q3")
      (value "MJD122T4G")
      (fields (field (name "BOM_Supplier Part") "C12789"))
      (libsource (lib "") (part "MJD122T4G"))
    )
    (comp (ref "Q4")
      (value "MJD122T4G")
      (fields (field (name "BOM_Supplier Part") "C12789"))
      (libsource (lib "") (part "MJD122T4G"))
    )
    (comp (ref "Q5")
      (value "MMBT5551_C2145")
      (fields (field (name "BOM_Manufacturer Part") "MMBT5551") (field (name "BOM_Supplier Part") "C2145"))
      (libsource (lib "") (part "MMBT5551_C2145"))
    )
    (comp (ref "Q9")
      (value "AO3401A")
      (fields (field (name "BOM_Supplier Part") "C15127"))
      (libsource (lib "") (part "AO3401A"))
    )
    (comp (ref "Q12")
      (value "MJD122T4G")
      (fields (field (name "BOM_Supplier Part") "C12789"))
      (libsource (lib "") (part "MJD122T4G"))
    )
    (comp (ref "Q13")
      (value "MJD122T4G")
      (fields (field (name "BOM_Supplier Part") "C12789"))
      (libsource (lib "") (part "MJD122T4G"))
    )
    (comp (ref "Q14")
      (value "MJD122T4G")
      (fields (field (name "BOM_Supplier Part") "C12789"))
      (libsource (lib "") (part "MJD122T4G"))
    )
    (comp (ref "R1")
      (value "2.4K")
      (fields
        (field (name "BOM_Manufacturer Part") "1206W4F2401T5E")
        (field (name "BOM_Supplier Part") "C17949")
      )
      (libsource (lib "") (part "1206W4F2401T5E"))
    )
    (comp (ref "R4")
      (value "10K")
      (fields
        (field (name "BOM_Manufacturer Part") "0603WAF1002T5E")
        (field (name "BOM_Supplier Part") "C25804")
      )
      (libsource (lib "") (part "0603WAF1002T5E_1"))
    )
    (comp (ref "R5")
      (value "2.2K")
      (fields
        (field (name "BOM_Manufacturer Part") "0603WAF2201T5E")
        (field (name "BOM_Supplier Part") "C4190")
      )
      (libsource (lib "") (part "0603WAF2201T5E"))
    )
    (comp (ref "R7")
      (value "10K")
      (fields
        (field (name "BOM_Manufacturer Part") "0603WAF1002T5E")
        (field (name "BOM_Supplier Part") "C25804")
      )
      (libsource (lib "") (part "0603WAF1002T5E_1"))
    )
    (comp (ref "R10")
      (value "10Ω")
      (fields
        (field (name "BOM_Manufacturer Part") "0603WAF100JT5E")
        (field (name "BOM_Supplier Part") "C22859")
      )
      (libsource (lib "") (part "0603WAF100JT5E"))
    )
    (comp (ref "R15")
      (value "10Ω")
      (fields
        (field (name "BOM_Manufacturer Part") "0603WAF100JT5E")
        (field (name "BOM_Supplier Part") "C22859")
      )
      (libsource (lib "") (part "0603WAF100JT5E"))
    )
    (comp (ref "R20")
      (value "10K")
      (fields
        (field (name "BOM_Manufacturer Part") "0603WAF1002T5E")
        (field (name "BOM_Supplier Part") "C25804")
      )
      (libsource (lib "") (part "0603WAF1002T5E"))
    )
    (comp (ref "R37")
      (value "1kΩ")
      (fields
        (field (name "BOM_Manufacturer Part") "RN731JTTD1001F25")
        (field (name "BOM_Supplier Part") "C719293")
      )
      (libsource (lib "") (part "RN731JTTD1001F25"))
    )
    (comp (ref "R43")
      (value "220K")
      (fields
        (field (name "BOM_Manufacturer Part") "0603WAF2203T5E")
        (field (name "BOM_Supplier Part") "C22961")
      )
      (libsource (lib "") (part "0603WAF2203T5E"))
    )
    (comp (ref "R48")
      (value "2.4K")
      (fields
        (field (name "BOM_Manufacturer Part") "1206W4F2401T5E")
        (field (name "BOM_Supplier Part") "C17949")
      )
      (libsource (lib "") (part "1206W4F2401T5E"))
    )
    (comp (ref "R49")
      (value "1kΩ")
      (fields
        (field (name "BOM_Manufacturer Part") "RN731JTTD1001F25")
        (field (name "BOM_Supplier Part") "C719293")
      )
      (libsource (lib "") (part "RN731JTTD1001F25"))
    )
    (comp (ref "R50")
      (value "10Ω")
      (fields
        (field (name "BOM_Manufacturer Part") "0603WAF100JT5E")
        (field (name "BOM_Supplier Part") "C22859")
      )
      (libsource (lib "") (part "0603WAF100JT5E"))
    )
    (comp (ref "R51")
      (value "1kΩ")
      (fields
        (field (name "BOM_Manufacturer Part") "RN731JTTD1001F25")
        (field (name "BOM_Supplier Part") "C719293")
      )
      (libsource (lib "") (part "RN731JTTD1001F25"))
    )
    (comp (ref "R52")
      (value "10K")
      (fields
        (field (name "BOM_Manufacturer Part") "0603WAF1002T5E")
        (field (name "BOM_Supplier Part") "C25804")
      )
      (libsource (lib "") (part "0603WAF1002T5E"))
    )
    (comp (ref "R53")
      (value "10K")
      (fields
        (field (name "BOM_Manufacturer Part") "0603WAF1002T5E")
        (field (name "BOM_Supplier Part") "C25804")
      )
      (libsource (lib "") (part "0603WAF1002T5E"))
    )
    (comp (ref "R54")
      (value "1kΩ")
      (fields
        (field (name "BOM_Manufacturer Part") "RN731JTTD1001F25")
        (field (name "BOM_Supplier Part") "C719293")
      )
      (libsource (lib "") (part "RN731JTTD1001F25"))
    )
    (comp (ref "R55")
      (value "10Ω")
      (fields
        (field (name "BOM_Manufacturer Part") "0603WAF100JT5E")
        (field (name "BOM_Supplier Part") "C22859")
      )
      (libsource (lib "") (part "0603WAF100JT5E"))
    )
    (comp (ref "R57")
      (value "10K")
      (fields
        (field (name "BOM_Manufacturer Part") "0603WAF1002T5E")
        (field (name "BOM_Supplier Part") "C25804")
      )
      (libsource (lib "") (part "0603WAF1002T5E"))
    )
    (comp (ref "R58")
      (value "4.7K")
      (fields
        (field (name "BOM_Manufacturer Part") "1206W4F4701T5E")
        (field (name "BOM_Supplier Part") "C17936")
      )
      (libsource (lib "") (part "1206W4F4701T5E"))
    )
    (comp (ref "R65")
      (value "2.4K")
      (fields
        (field (name "BOM_Manufacturer Part") "1206W4F2401T5E")
        (field (name "BOM_Supplier Part") "C17949")
      )
      (libsource (lib "") (part "1206W4F2401T5E"))
    )
    (comp (ref "R66")
      (value "10K")
      (fields
        (field (name "BOM_Manufacturer Part") "0603WAF1002T5E")
        (field (name "BOM_Supplier Part") "C25804")
      )
      (libsource (lib "") (part "0603WAF1002T5E"))
    )
    (comp (ref "R67")
      (value "2.4K")
      (fields
        (field (name "BOM_Manufacturer Part") "1206W4F2401T5E")
        (field (name "BOM_Supplier Part") "C17949")
      )
      (libsource (lib "") (part "1206W4F2401T5E"))
    )
    (comp (ref "R337")
      (value "2.2K")
      (fields
        (field (name "BOM_Manufacturer Part") "0603WAF2201T5E")
        (field (name "BOM_Supplier Part") "C4190")
      )
      (libsource (lib "") (part "0603WAF2201T5E"))
    )
    (comp (ref "R338")
      (value "2.2K")
      (fields
        (field (name "BOM_Manufacturer Part") "0603WAF2201T5E")
        (field (name "BOM_Supplier Part") "C4190")
      )
      (libsource (lib "") (part "0603WAF2201T5E"))
    )
    (comp (ref "R340")
      (value "4.7K")
      (fields
        (field (name "BOM_Manufacturer Part") "1206W4F4701T5E")
        (field (name "BOM_Supplier Part") "C17936")
      )
      (libsource (lib "") (part "1206W4F4701T5E"))
    )
    (comp (ref "R341")
      (value "4.7K")
      (fields
        (field (name "BOM_Manufacturer Part") "1206W4F4701T5E")
        (field (name "BOM_Supplier Part") "C17936")
      )
      (libsource (lib "") (part "1206W4F4701T5E"))
    )
    (comp (ref "R345")
      (value "47K")
      (fields
        (field (name "BOM_Manufacturer Part") "0805W8F4702T5E")
        (field (name "BOM_Supplier Part") "C17713")
      )
      (libsource (lib "") (part "0805W8F4702T5E"))
    )
    (comp (ref "R346")
      (value "47K")
      (fields
        (field (name "BOM_Manufacturer Part") "0805W8F4702T5E")
        (field (name "BOM_Supplier Part") "C17713")
      )
      (libsource (lib "") (part "0805W8F4702T5E"))
    )
    (comp (ref "R348")
      (value "43K")
      (fields
        (field (name "BOM_Manufacturer Part") "0603WAF4302T5E")
        (field (name "BOM_Supplier Part") "C23172")
      )
      (libsource (lib "") (part "0603WAF4302T5E"))
    )
    (comp (ref "R349")
      (value "43K")
      (fields
        (field (name "BOM_Manufacturer Part") "0603WAF4302T5E")
        (field (name "BOM_Supplier Part") "C23172")
      )
      (libsource (lib "") (part "0603WAF4302T5E"))
    )
    (comp (ref "R353")
      (value "10K")
      (fields
        (field (name "BOM_Manufacturer Part") "0603WAF1002T5E")
        (field (name "BOM_Supplier Part") "C25804")
      )
      (libsource (lib "") (part "0603WAF1002T5E"))
    )
    (comp (ref "R354")
      (value "10K")
      (fields
        (field (name "BOM_Manufacturer Part") "0603WAF1002T5E")
        (field (name "BOM_Supplier Part") "C25804")
      )
      (libsource (lib "") (part "0603WAF1002T5E"))
    )
    (comp (ref "R355")
      (value "10K")
      (fields
        (field (name "BOM_Manufacturer Part") "0603WAF1002T5E")
        (field (name "BOM_Supplier Part") "C25804")
      )
      (libsource (lib "") (part "0603WAF1002T5E"))
    )
    (comp (ref "R356")
      (value "10K")
      (fields
        (field (name "BOM_Manufacturer Part") "0603WAF1002T5E")
        (field (name "BOM_Supplier Part") "C25804")
      )
      (libsource (lib "") (part "0603WAF1002T5E"))
    )
    (comp (ref "R357")
      (value "15K")
      (fields
        (field (name "BOM_Manufacturer Part") "0603WAF1502T5E")
        (field (name "BOM_Supplier Part") "C22809")
      )
      (libsource (lib "") (part "0603WAF1502T5E"))
    )
    (comp (ref "R358")
      (value "15K")
      (fields
        (field (name "BOM_Manufacturer Part") "0603WAF1502T5E")
        (field (name "BOM_Supplier Part") "C22809")
      )
      (libsource (lib "") (part "0603WAF1502T5E"))
    )
    (comp (ref "R359")
      (value "470")
      (fields
        (field (name "BOM_Manufacturer Part") "0805W8F4700T5E")
        (field (name "BOM_Supplier Part") "C17710")
      )
      (libsource (lib "") (part "0805W8F4700T5E"))
    )
    (comp (ref "R360")
      (value "470")
      (fields
        (field (name "BOM_Manufacturer Part") "0805W8F4700T5E")
        (field (name "BOM_Supplier Part") "C17710")
      )
      (libsource (lib "") (part "0805W8F4700T5E"))
    )
    (comp (ref "U51")
      (value "NE555DR")
      (fields (field (name "BOM_Supplier Part") "C7593"))
      (libsource (lib "") (part "NE555DR"))
    )
    (comp (ref "U58")
      (value "NE555DR")
      (fields (field (name "BOM_Supplier Part") "C7593"))
      (libsource (lib "") (part "NE555DR"))
    )
    (comp (ref "U59")
      (value "NE555DR")
      (fields (field (name "BOM_Supplier Part") "C7593"))
      (libsource (lib "") (part "NE555DR"))
    )
    (comp (ref "C2")
      (value "2.2nF")
      (fields
        (field (name "BOM_Manufacturer Part") "0402B222K500NT")
        (field (name "BOM_Supplier Part") "C1531")
      )
      (libsource (lib "") (part "0402B222K500NT"))
    )
    (comp (ref "C9")
      (value "100nF")
      (fields
        (field (name "BOM_Manufacturer Part") "CL05B104KO5NNNC")
        (field (name "BOM_Supplier Part") "C1525")
      )
      (libsource (lib "") (part "CL05B104KO5NNNC_5"))
    )
    (comp (ref "C10")
      (value "100nF")
      (fields
        (field (name "BOM_Manufacturer Part") "CL05B104KO5NNNC")
        (field (name "BOM_Supplier Part") "C1525")
      )
      (libsource (lib "") (part "CL05B104KO5NNNC_3"))
    )
    (comp (ref "C13")
      (value "100nF")
      (fields
        (field (name "BOM_Manufacturer Part") "CL05B104KO5NNNC")
        (field (name "BOM_Supplier Part") "C1525")
      )
      (libsource (lib "") (part "CL05B104KO5NNNC_1"))
    )
    (comp (ref "C14")
      (value "100nF")
      (fields
        (field (name "BOM_Manufacturer Part") "CL05B104KO5NNNC")
        (field (name "BOM_Supplier Part") "C1525")
      )
      (libsource (lib "") (part "CL05B104KO5NNNC_1"))
    )
    (comp (ref "C15")
      (value "10nF")
      (fields
        (field (name "BOM_Manufacturer Part") "0603B103K500NT")
        (field (name "BOM_Supplier Part") "C57112")
      )
      (libsource (lib "") (part "0603B103K500NT"))
    )
    (comp (ref "C26")
      (value "10nF")
      (fields
        (field (name "BOM_Manufacturer Part") "0603B103K500NT")
        (field (name "BOM_Supplier Part") "C57112")
      )
      (libsource (lib "") (part "0603B103K500NT_1"))
    )
    (comp (ref "C31")
      (value "100nF")
      (fields
        (field (name "BOM_Manufacturer Part") "CL05B104KO5NNNC")
        (field (name "BOM_Supplier Part") "C1525")
      )
      (libsource (lib "") (part "CL05B104KO5NNNC_4"))
    )
    (comp (ref "C32")
      (value "100nF")
      (fields
        (field (name "BOM_Manufacturer Part") "CL05B104KO5NNNC")
        (field (name "BOM_Supplier Part") "C1525")
      )
      (libsource (lib "") (part "CL05B104KO5NNNC"))
    )
    (comp (ref "C33")
      (value "100nF")
      (fields
        (field (name "BOM_Manufacturer Part") "CL05B104KO5NNNC")
        (field (name "BOM_Supplier Part") "C1525")
      )
      (libsource (lib "") (part "CL05B104KO5NNNC_2"))
    )
    (comp (ref "D16")
      (value "1N5819WS")
      (fields (field (name "BOM_Supplier Part") "C191023"))
      (libsource (lib "") (part "1N5819WS"))
    )
    (comp (ref "D23")
      (value "SS34_C8678")
      (fields (field (name "BOM_Manufacturer Part") "SS34") (field (name "BOM_Supplier Part") "C8678"))
      (libsource (lib "") (part "SS34_C8678"))
    )
    (comp (ref "D24")
      (value "1N5819WS")
      (fields (field (name "BOM_Supplier Part") "C191023"))
      (libsource (lib "") (part "1N5819WS"))
    )
    (comp (ref "H1")
      (value "8DIGIT7SEGMENTDISPLAY-NON_MOUNT")
      (libsource (lib "") (part "8DIGIT7SEGMENTDISPLAY-NON_MOUNT"))
    )
    (comp (ref "R31")
      (value "4.7K")
      (fields
        (field (name "BOM_Manufacturer Part") "1206W4F4701T5E")
        (field (name "BOM_Supplier Part") "C17936")
      )
      (libsource (lib "") (part "1206W4F4701T5E"))
    )
    (comp (ref "R32")
      (value "4.7K")
      (fields
        (field (name "BOM_Manufacturer Part") "1206W4F4701T5E")
        (field (name "BOM_Supplier Part") "C17936")
      )
      (libsource (lib "") (part "1206W4F4701T5E"))
    )
    (comp (ref "R33")
      (value "4.7K")
      (fields
        (field (name "BOM_Manufacturer Part") "1206W4F4701T5E")
        (field (name "BOM_Supplier Part") "C17936")
      )
      (libsource (lib "") (part "1206W4F4701T5E"))
    )
    (comp (ref "R34")
      (value "10K")
      (fields
        (field (name "BOM_Manufacturer Part") "0402WGF1002TCE")
        (field (name "BOM_Supplier Part") "C25744")
      )
      (libsource (lib "") (part "0402WGF1002TCE"))
    )
    (comp (ref "R35")
      (value "10K")
      (fields
        (field (name "BOM_Manufacturer Part") "0402WGF1002TCE")
        (field (name "BOM_Supplier Part") "C25744")
      )
      (libsource (lib "") (part "0402WGF1002TCE"))
    )
    (comp (ref "R36")
      (value "10K")
      (fields
        (field (name "BOM_Manufacturer Part") "0402WGF1002TCE")
        (field (name "BOM_Supplier Part") "C25744")
      )
      (libsource (lib "") (part "0402WGF1002TCE"))
    )
    (comp (ref "R38")
      (value "10K")
      (fields
        (field (name "BOM_Manufacturer Part") "0402WGF1002TCE")
        (field (name "BOM_Supplier Part") "C25744")
      )
      (libsource (lib "") (part "0402WGF1002TCE"))
    )
    (comp (ref "R39")
      (value "10K")
      (fields
        (field (name "BOM_Manufacturer Part") "0402WGF1002TCE")
        (field (name "BOM_Supplier Part") "C25744")
      )
      (libsource (lib "") (part "0402WGF1002TCE"))
    )
    (comp (ref "R40")
      (value "10K")
      (fields
        (field (name "BOM_Manufacturer Part") "0402WGF1002TCE")
        (field (name "BOM_Supplier Part") "C25744")
      )
      (libsource (lib "") (part "0402WGF1002TCE"))
    )
    (comp (ref "R41")
      (value "10K")
      (fields
        (field (name "BOM_Manufacturer Part") "0402WGF1002TCE")
        (field (name "BOM_Supplier Part") "C25744")
      )
      (libsource (lib "") (part "0402WGF1002TCE"))
    )
    (comp (ref "SW1")
      (value "RESET")
      (fields
        (field (name "BOM_Manufacturer Part") "GT-TC048A-H025-L1")
        (field (name "BOM_Supplier Part") "C778166")
      )
      (libsource (lib "") (part "GT-TC048A-H025-L1"))
    )
    (comp (ref "U5")
      (value "MAX3485ESA+T")
      (fields (field (name "BOM_Supplier Part") "C18148"))
      (libsource (lib "") (part "MAX3485ESA+T"))
    )
    (comp (ref "U6")
      (value "MPU-6050_C24112")
      (fields (field (name "BOM_Manufacturer Part") "MPU-6050") (field (name "BOM_Supplier Part") "C24112"))
      (libsource (lib "") (part "MPU-6050_C24112"))
    )
    (comp (ref "U7")
      (value "CAT24C512WI-GT3")
      (fields (field (name "BOM_Supplier Part") "C79986"))
      (libsource (lib "") (part "CAT24C512WI-GT3"))
    )
    (comp (ref "U11")
      (value "W5100S-EVB-PICO")
      (fields
        (field (name "BOM_Manufacturer Part") "W5100S-EVB-Pico")
        (field (name "BOM_Supplier Part") "950-W5100S-EVB-PICO")
      )
      (libsource (lib "") (part "W5100S-EVB-PICO COPY"))
    )
    (comp (ref "C4")
      (value "100nF")
      (fields
        (field (name "BOM_Manufacturer Part") "CL05B104KO5NNNC")
        (field (name "BOM_Supplier Part") "C1525")
      )
      (libsource (lib "") (part "CL05B104KO5NNNC_2"))
    )
    (comp (ref "C5")
      (value "100nF")
      (fields
        (field (name "BOM_Manufacturer Part") "CL05B104KO5NNNC")
        (field (name "BOM_Supplier Part") "C1525")
      )
      (libsource (lib "") (part "CL05B104KO5NNNC"))
    )
    (comp (ref "C6")
      (value "100nF")
      (fields
        (field (name "BOM_Manufacturer Part") "CL05B104KO5NNNC")
        (field (name "BOM_Supplier Part") "C1525")
      )
      (libsource (lib "") (part "CL05B104KO5NNNC_1"))
    )
    (comp (ref "C7")
      (value "100nF")
      (fields
        (field (name "BOM_Manufacturer Part") "CL05B104KO5NNNC")
        (field (name "BOM_Supplier Part") "C1525")
      )
      (libsource (lib "") (part "CL05B104KO5NNNC_2"))
    )
    (comp (ref "C11")
      (value "100nF")
      (fields
        (field (name "BOM_Manufacturer Part") "CL05B104KO5NNNC")
        (field (name "BOM_Supplier Part") "C1525")
      )
      (libsource (lib "") (part "CL05B104KO5NNNC"))
    )
    (comp (ref "C16")
      (value "100nF")
      (fields
        (field (name "BOM_Manufacturer Part") "CL05B104KO5NNNC")
        (field (name "BOM_Supplier Part") "C1525")
      )
      (libsource (lib "") (part "CL05B104KO5NNNC_1"))
    )
    (comp (ref "C24")
      (value "100nF")
      (fields
        (field (name "BOM_Manufacturer Part") "CL05B104KO5NNNC")
        (field (name "BOM_Supplier Part") "C1525")
      )
      (libsource (lib "") (part "CL05B104KO5NNNC_3"))
    )
    (comp (ref "C25")
      (value "100nF")
      (fields
        (field (name "BOM_Manufacturer Part") "CL05B104KO5NNNC")
        (field (name "BOM_Supplier Part") "C1525")
      )
      (libsource (lib "") (part "CL05B104KO5NNNC_3"))
    )
    (comp (ref "CN2")
      (value "4-20mA OUT")
      (fields
        (field (name "BOM_Manufacturer Part") "WJ15EDGVM-3.81-04P-14-00A")
        (field (name "BOM_Supplier Part") "C157478")
      )
      (libsource (lib "") (part "WJ15EDGVM-3.81-04P-14-00A"))
    )
    (comp (ref "CN11")
      (value "4-20mA (1)")
      (fields
        (field (name "BOM_Manufacturer Part") "15EDGVM-3.81-02P-14-00A(H)")
        (field (name "BOM_Supplier Part") "C507020")
      )
      (libsource (lib "") (part "15EDGVM-3.81-02P-14-00A(H)"))
    )
    (comp (ref "CN13")
      (value "4-20mA (2)")
      (fields
        (field (name "BOM_Manufacturer Part") "15EDGVM-3.81-02P-14-00A(H)")
        (field (name "BOM_Supplier Part") "C507020")
      )
      (libsource (lib "") (part "15EDGVM-3.81-02P-14-00A(H)"))
    )
    (comp (ref "CN17")
      (value "4-20mA (3)")
      (fields
        (field (name "BOM_Manufacturer Part") "15EDGVM-3.81-02P-14-00A(H)")
        (field (name "BOM_Supplier Part") "C507020")
      )
      (libsource (lib "") (part "15EDGVM-3.81-02P-14-00A(H)"))
    )
    (comp (ref "CN24")
      (value "4-20mA (4)")
      (fields
        (field (name "BOM_Manufacturer Part") "15EDGVM-3.81-02P-14-00A(H)")
        (field (name "BOM_Supplier Part") "C507020")
      )
      (libsource (lib "") (part "15EDGVM-3.81-02P-14-00A(H)"))
    )
    (comp (ref "R2")
      (value "10")
      (fields
        (field (name "BOM_Manufacturer Part") "0402WGF100JTCE")
        (field (name "BOM_Supplier Part") "C25077")
      )
      (libsource (lib "") (part "0402WGF100JTCE_2"))
    )
    (comp (ref "R3")
      (value "10")
      (fields
        (field (name "BOM_Manufacturer Part") "0402WGF100JTCE")
        (field (name "BOM_Supplier Part") "C25077")
      )
      (libsource (lib "") (part "0402WGF100JTCE_2"))
    )
    (comp (ref "R8")
      (value "10")
      (fields
        (field (name "BOM_Manufacturer Part") "0402WGF100JTCE")
        (field (name "BOM_Supplier Part") "C25077")
      )
      (libsource (lib "") (part "0402WGF100JTCE"))
    )
    (comp (ref "R9")
      (value "10")
      (fields
        (field (name "BOM_Manufacturer Part") "0402WGF100JTCE")
        (field (name "BOM_Supplier Part") "C25077")
      )
      (libsource (lib "") (part "0402WGF100JTCE"))
    )
    (comp (ref "R13")
      (value "10")
      (fields
        (field (name "BOM_Manufacturer Part") "0402WGF100JTCE")
        (field (name "BOM_Supplier Part") "C25077")
      )
      (libsource (lib "") (part "0402WGF100JTCE_1"))
    )
    (comp (ref "R14")
      (value "10")
      (fields
        (field (name "BOM_Manufacturer Part") "0402WGF100JTCE")
        (field (name "BOM_Supplier Part") "C25077")
      )
      (libsource (lib "") (part "0402WGF100JTCE_1"))
    )
    (comp (ref "R16")
      (value "1Ω")
      (fields
        (field (name "BOM_Manufacturer Part") "RT1206BRD071RL")
        (field (name "BOM_Supplier Part") "C513714")
      )
      (libsource (lib "") (part "RT1206BRD071RL_1"))
    )
    (comp (ref "R17")
      (value "1Ω")
      (fields
        (field (name "BOM_Manufacturer Part") "RT1206BRD071RL")
        (field (name "BOM_Supplier Part") "C513714")
      )
      (libsource (lib "") (part "RT1206BRD071RL"))
    )
    (comp (ref "R18")
      (value "10")
      (fields
        (field (name "BOM_Manufacturer Part") "0402WGF100JTCE")
        (field (name "BOM_Supplier Part") "C25077")
      )
      (libsource (lib "") (part "0402WGF100JTCE"))
    )
    (comp (ref "R19")
      (value "10")
      (fields
        (field (name "BOM_Manufacturer Part") "0402WGF100JTCE")
        (field (name "BOM_Supplier Part") "C25077")
      )
      (libsource (lib "") (part "0402WGF100JTCE"))
    )
    (comp (ref "R21")
      (value "1Ω")
      (fields
        (field (name "BOM_Manufacturer Part") "RT1206BRD071RL")
        (field (name "BOM_Supplier Part") "C513714")
      )
      (libsource (lib "") (part "RT1206BRD071RL"))
    )
    (comp (ref "R22")
      (value "1Ω")
      (fields
        (field (name "BOM_Manufacturer Part") "RT1206BRD071RL")
        (field (name "BOM_Supplier Part") "C513714")
      )
      (libsource (lib "") (part "RT1206BRD071RL"))
    )
    (comp (ref "R23")
      (value "10")
      (fields
        (field (name "BOM_Manufacturer Part") "0402WGF100JTCE")
        (field (name "BOM_Supplier Part") "C25077")
      )
      (libsource (lib "") (part "0402WGF100JTCE_2"))
    )
    (comp (ref "R24")
      (value "10")
      (fields
        (field (name "BOM_Manufacturer Part") "0402WGF100JTCE")
        (field (name "BOM_Supplier Part") "C25077")
      )
      (libsource (lib "") (part "0402WGF100JTCE_2"))
    )
    (comp (ref "R26")
      (value "1Ω")
      (fields
        (field (name "BOM_Manufacturer Part") "RT1206BRD071RL")
        (field (name "BOM_Supplier Part") "C513714")
      )
      (libsource (lib "") (part "RT1206BRD071RL"))
    )
    (comp (ref "R27")
      (value "1Ω")
      (fields
        (field (name "BOM_Manufacturer Part") "RT1206BRD071RL")
        (field (name "BOM_Supplier Part") "C513714")
      )
      (libsource (lib "") (part "RT1206BRD071RL_2"))
    )
    (comp (ref "R28")
      (value "10")
      (fields
        (field (name "BOM_Manufacturer Part") "0402WGF100JTCE")
        (field (name "BOM_Supplier Part") "C25077")
      )
      (libsource (lib "") (part "0402WGF100JTCE_1"))
    )
    (comp (ref "R29")
      (value "10")
      (fields
        (field (name "BOM_Manufacturer Part") "0402WGF100JTCE")
        (field (name "BOM_Supplier Part") "C25077")
      )
      (libsource (lib "") (part "0402WGF100JTCE_1"))
    )
    (comp (ref "SJ12") (value "NEG04") (libsource (lib "") (part "JUMPER-PAD-2-NOYES_SILK")))
    (comp (ref "SJ13") (value "NEG03") (libsource (lib "") (part "JUMPER-PAD-2-NOYES_SILK")))
    (comp (ref "SJ14") (value "NEG02") (libsource (lib "") (part "JUMPER-PAD-2-NOYES_SILK")))
    (comp (ref "SJ15") (value "NEG01") (libsource (lib "") (part "JUMPER-PAD-2-NOYES_SILK")))
    (comp (ref "U1")
      (value "INA3221AIRGVR")
      (fields (field (name "BOM_Supplier Part") "C181255"))
      (libsource (lib "") (part "INA3221AIRGVR"))
    )
    (comp (ref "U2")
      (value "INA3221AIRGVR")
      (fields (field (name "BOM_Supplier Part") "C181255"))
      (libsource (lib "") (part "INA3221AIRGVR"))
    )
    (comp (ref "C1")
      (value "1uF")
      (fields
        (field (name "BOM_Manufacturer Part") "CL10A105KB8NNNC")
        (field (name "BOM_Supplier Part") "C15849")
      )
      (libsource (lib "") (part "CL10A105KB8NNNC"))
    )
    (comp (ref "C65")
      (value "1nF")
      (fields
        (field (name "BOM_Manufacturer Part") "0402B102K500NT")
        (field (name "BOM_Supplier Part") "C1523")
      )
      (libsource (lib "") (part "0402B102K500NT"))
    )
    (comp (ref "C139")
      (value "1uF")
      (fields
        (field (name "BOM_Manufacturer Part") "CL10A105KB8NNNC")
        (field (name "BOM_Supplier Part") "C15849")
      )
      (libsource (lib "") (part "CL10A105KB8NNNC"))
    )
    (comp (ref "CN1")
      (value "POWER")
      (fields
        (field (name "BOM_Manufacturer Part") "WJ15EDGVM-3.81-04P-14-00A")
        (field (name "BOM_Supplier Part") "C157478")
      )
      (libsource (lib "") (part "WJ15EDGVM-3.81-04P-14-00A"))
    )
    (comp (ref "CN3")
      (value "LED P0-0")
      (fields
        (field (name "BOM_Manufacturer Part") "A2008WV-S-2P")
        (field (name "BOM_Supplier Part") "C273123")
      )
      (libsource (lib "") (part "A2008WV-S-2P_1"))
    )
    (comp (ref "CN4")
      (value "LED P0-1")
      (fields
        (field (name "BOM_Manufacturer Part") "A2008WV-S-2P")
        (field (name "BOM_Supplier Part") "C273123")
      )
      (libsource (lib "") (part "A2008WV-S-2P_1"))
    )
    (comp (ref "CN5")
      (value "LED P1-1")
      (fields
        (field (name "BOM_Manufacturer Part") "A2008WV-S-2P")
        (field (name "BOM_Supplier Part") "C273123")
      )
      (libsource (lib "") (part "A2008WV-S-2P_1"))
    )
    (comp (ref "CN6")
      (value "LED GP27")
      (fields
        (field (name "BOM_Manufacturer Part") "A2008WV-S-2P")
        (field (name "BOM_Supplier Part") "C273123")
      )
      (libsource (lib "") (part "A2008WV-S-2P"))
    )
    (comp (ref "CN7")
      (value "LED GP26")
      (fields
        (field (name "BOM_Manufacturer Part") "A2008WV-S-2P")
        (field (name "BOM_Supplier Part") "C273123")
      )
      (libsource (lib "") (part "A2008WV-S-2P"))
    )
    (comp (ref "CN8")
      (value "RTU RS485")
      (fields
        (field (name "BOM_Manufacturer Part") "15EDGVM-3.81-02P-14-00A(H)")
        (field (name "BOM_Supplier Part") "C507020")
      )
      (libsource (lib "") (part "15EDGVM-3.81-02P-14-00A(H)"))
    )
    (comp (ref "CN12")
      (value "LED GP22")
      (fields
        (field (name "BOM_Manufacturer Part") "A2008WV-S-2P")
        (field (name "BOM_Supplier Part") "C273123")
      )
      (libsource (lib "") (part "A2008WV-S-2P"))
    )
    (comp (ref "CN18")
      (value "4-20mA KSENS")
      (fields
        (field (name "BOM_Manufacturer Part") "15EDGVM-3.81-02P-14-00A(H)")
        (field (name "BOM_Supplier Part") "C507020")
      )
      (libsource (lib "") (part "15EDGVM-3.81-02P-14-00A(H)_1"))
    )
    (comp (ref "CN21")
      (value "SNS 1")
      (fields
        (field (name "BOM_Manufacturer Part") "15EDGVM-3.81-02P-14-00A(H)")
        (field (name "BOM_Supplier Part") "C507020")
      )
      (libsource (lib "") (part "15EDGVM-3.81-02P-14-00A(H)"))
    )
    (comp (ref "CN23")
      (value "SNS 0")
      (fields
        (field (name "BOM_Manufacturer Part") "15EDGVM-3.81-02P-14-00A(H)")
        (field (name "BOM_Supplier Part") "C507020")
      )
      (libsource (lib "") (part "15EDGVM-3.81-02P-14-00A(H)"))
    )
    (comp (ref "D9")
      (value "SM4007PL")
      (fields (field (name "BOM_Supplier Part") "C64898"))
      (libsource (lib "") (part "SM4007PL"))
    )
    (comp (ref "D10")
      (value "SM4007PL")
      (fields (field (name "BOM_Supplier Part") "C64898"))
      (libsource (lib "") (part "SM4007PL_1"))
    )
    (comp (ref "D17")
      (value "SM4007PL")
      (fields (field (name "BOM_Supplier Part") "C64898"))
      (libsource (lib "") (part "SM4007PL"))
    )
    (comp (ref "D18")
      (value "1N5819WS")
      (fields (field (name "BOM_Supplier Part") "C191023"))
      (libsource (lib "") (part "1N5819WS"))
    )
    (comp (ref "D26")
      (value "SM4007PL")
      (fields (field (name "BOM_Supplier Part") "C64898"))
      (libsource (lib "") (part "SM4007PL"))
    )
    (comp (ref "D27")
      (value "SM4007PL")
      (fields (field (name "BOM_Supplier Part") "C64898"))
      (libsource (lib "") (part "SM4007PL"))
    )
    (comp (ref "LED1")
      (value "LED GP26")
      (fields (field (name "BOM_Manufacturer Part") "KT-0603R") (field (name "BOM_Supplier Part") "C2286"))
      (libsource (lib "") (part "KT-0603R"))
    )
    (comp (ref "LED3")
      (value "LED GP22")
      (fields (field (name "BOM_Manufacturer Part") "KT-0603R") (field (name "BOM_Supplier Part") "C2286"))
      (libsource (lib "") (part "KT-0603R"))
    )
    (comp (ref "LED4")
      (value "LED GP27")
      (fields (field (name "BOM_Manufacturer Part") "KT-0603R") (field (name "BOM_Supplier Part") "C2286"))
      (libsource (lib "") (part "KT-0603R"))
    )
    (comp (ref "LED8")
      (value "C1-1")
      (fields
        (field (name "BOM_Manufacturer Part") "whiteLEDSMD")
        (field (name "BOM_Supplier Part") "C34499")
      )
      (libsource (lib "") (part "whiteLEDSMD"))
    )
    (comp (ref "LED9")
      (value "C0-1")
      (fields
        (field (name "BOM_Manufacturer Part") "whiteLEDSMD")
        (field (name "BOM_Supplier Part") "C34499")
      )
      (libsource (lib "") (part "whiteLEDSMD"))
    )
    (comp (ref "LED10")
      (value "P0-1")
      (fields
        (field (name "BOM_Manufacturer Part") "whiteLEDSMD")
        (field (name "BOM_Supplier Part") "C34499")
      )
      (libsource (lib "") (part "whiteLEDSMD"))
    )
    (comp (ref "LED11")
      (value "P1-1")
      (fields
        (field (name "BOM_Manufacturer Part") "whiteLEDSMD")
        (field (name "BOM_Supplier Part") "C34499")
      )
      (libsource (lib "") (part "whiteLEDSMD"))
    )
    (comp (ref "LED12")
      (value "P0-0")
      (fields
        (field (name "BOM_Manufacturer Part") "whiteLEDSMD")
        (field (name "BOM_Supplier Part") "C34499")
      )
      (libsource (lib "") (part "whiteLEDSMD"))
    )
    (comp (ref "LED17")
      (value "GP15 TRIG")
      (fields
        (field (name "BOM_Manufacturer Part") "0603White light")
        (field (name "BOM_Supplier Part") "C2290")
      )
      (libsource (lib "") (part "0603White light_C2290"))
    )
    (comp (ref "Q10")
      (value "MMBT5551_C2145")
      (fields (field (name "BOM_Manufacturer Part") "MMBT5551") (field (name "BOM_Supplier Part") "C2145"))
      (libsource (lib "") (part "MMBT5551_C2145"))
    )
    (comp (ref "Q11")
      (value "AO3401A")
      (fields (field (name "BOM_Supplier Part") "C15127"))
      (libsource (lib "") (part "AO3401A"))
    )
    (comp (ref "Q15")
      (value "MMBT2222A_C8512")
      (fields (field (name "BOM_Manufacturer Part") "MMBT2222A") (field (name "BOM_Supplier Part") "C8512"))
      (libsource (lib "") (part "MMBT2222A_C8512"))
    )
    (comp (ref "Q17")
      (value "MMBT2222A_C8512")
      (fields (field (name "BOM_Manufacturer Part") "MMBT2222A") (field (name "BOM_Supplier Part") "C8512"))
      (libsource (lib "") (part "MMBT2222A_C8512"))
    )
    (comp (ref "Q22")
      (value "MMBT2222A_C8512")
      (fields (field (name "BOM_Manufacturer Part") "MMBT2222A") (field (name "BOM_Supplier Part") "C8512"))
      (libsource (lib "") (part "MMBT2222A_C8512"))
    )
    (comp (ref "R6")
      (value "2.4K")
      (fields
        (field (name "BOM_Manufacturer Part") "1206W4F2401T5E")
        (field (name "BOM_Supplier Part") "C17949")
      )
      (libsource (lib "") (part "1206W4F2401T5E"))
    )
    (comp (ref "R12")
      (value "1.5K")
      (fields
        (field (name "BOM_Manufacturer Part") "0603WAF1501T5E")
        (field (name "BOM_Supplier Part") "C22843")
      )
      (libsource (lib "") (part "0603WAF1501T5E"))
    )
    (comp (ref "R42")
      (value "120")
      (fields
        (field (name "BOM_Manufacturer Part") "0603WAF1200T5E")
        (field (name "BOM_Supplier Part") "C22787")
      )
      (libsource (lib "") (part "0603WAF1200T5E"))
    )
    (comp (ref "R44")
      (value "1.5K")
      (fields
        (field (name "BOM_Manufacturer Part") "0603WAF1501T5E")
        (field (name "BOM_Supplier Part") "C22843")
      )
      (libsource (lib "") (part "0603WAF1501T5E"))
    )
    (comp (ref "R46")
      (value "2.4K")
      (fields
        (field (name "BOM_Manufacturer Part") "1206W4F2401T5E")
        (field (name "BOM_Supplier Part") "C17949")
      )
      (libsource (lib "") (part "1206W4F2401T5E_1"))
    )
    (comp (ref "R47")
      (value "2.4K")
      (fields
        (field (name "BOM_Manufacturer Part") "1206W4F2401T5E")
        (field (name "BOM_Supplier Part") "C17949")
      )
      (libsource (lib "") (part "1206W4F2401T5E_1"))
    )
    (comp (ref "R56")
      (value "2.4K")
      (fields
        (field (name "BOM_Manufacturer Part") "1206W4F2401T5E")
        (field (name "BOM_Supplier Part") "C17949")
      )
      (libsource (lib "") (part "1206W4F2401T5E"))
    )
    (comp (ref "R59")
      (value "2.2K")
      (fields
        (field (name "BOM_Manufacturer Part") "0603WAF2201T5E")
        (field (name "BOM_Supplier Part") "C4190")
      )
      (libsource (lib "") (part "0603WAF2201T5E"))
    )
    (comp (ref "R60")
      (value "10K")
      (fields
        (field (name "BOM_Manufacturer Part") "0603WAF1002T5E")
        (field (name "BOM_Supplier Part") "C25804")
      )
      (libsource (lib "") (part "0603WAF1002T5E_1"))
    )
    (comp (ref "R61")
      (value "2.4K")
      (fields
        (field (name "BOM_Manufacturer Part") "1206W4F2401T5E")
        (field (name "BOM_Supplier Part") "C17949")
      )
      (libsource (lib "") (part "1206W4F2401T5E_1"))
    )
    (comp (ref "R62")
      (value "2.4K")
      (fields
        (field (name "BOM_Manufacturer Part") "1206W4F2401T5E")
        (field (name "BOM_Supplier Part") "C17949")
      )
      (libsource (lib "") (part "1206W4F2401T5E"))
    )
    (comp (ref "R63")
      (value "2.2K")
      (fields
        (field (name "BOM_Manufacturer Part") "0603WAF2201T5E")
        (field (name "BOM_Supplier Part") "C4190")
      )
      (libsource (lib "") (part "0603WAF2201T5E"))
    )
    (comp (ref "R64")
      (value "10K")
      (fields
        (field (name "BOM_Manufacturer Part") "0603WAF1002T5E")
        (field (name "BOM_Supplier Part") "C25804")
      )
      (libsource (lib "") (part "0603WAF1002T5E_1"))
    )
    (comp (ref "R75")
      (value "220")
      (fields
        (field (name "BOM_Manufacturer Part") "0402WGF2200TCE")
        (field (name "BOM_Supplier Part") "C25091")
      )
      (libsource (lib "") (part "0402WGF2200TCE"))
    )
    (comp (ref "R76")
      (value "2.4K")
      (fields
        (field (name "BOM_Manufacturer Part") "1206W4F2401T5E")
        (field (name "BOM_Supplier Part") "C17949")
      )
      (libsource (lib "") (part "1206W4F2401T5E_1"))
    )
    (comp (ref "R81")
      (value "1.5K")
      (fields
        (field (name "BOM_Manufacturer Part") "0603WAF1501T5E")
        (field (name "BOM_Supplier Part") "C22843")
      )
      (libsource (lib "") (part "0603WAF1501T5E"))
    )
    (comp (ref "R83")
      (value "2.2K")
      (fields
        (field (name "BOM_Manufacturer Part") "0603WAF2201T5E")
        (field (name "BOM_Supplier Part") "C4190")
      )
      (libsource (lib "") (part "0603WAF2201T5E"))
    )
    (comp (ref "R84")
      (value "10K")
      (fields
        (field (name "BOM_Manufacturer Part") "0603WAF1002T5E")
        (field (name "BOM_Supplier Part") "C25804")
      )
      (libsource (lib "") (part "0603WAF1002T5E_1"))
    )
    (comp (ref "R99")
      (value "10K")
      (fields
        (field (name "BOM_Manufacturer Part") "0603WAF1002T5E")
        (field (name "BOM_Supplier Part") "C25804")
      )
      (libsource (lib "") (part "0603WAF1002T5E"))
    )
    (comp (ref "R114")
      (value "10K")
      (fields
        (field (name "BOM_Manufacturer Part") "0603WAF1002T5E")
        (field (name "BOM_Supplier Part") "C25804")
      )
      (libsource (lib "") (part "0603WAF1002T5E_2"))
    )
    (comp (ref "R151")
      (value "2.4K")
      (fields
        (field (name "BOM_Manufacturer Part") "1206W4F2401T5E")
        (field (name "BOM_Supplier Part") "C17949")
      )
      (libsource (lib "") (part "1206W4F2401T5E_1"))
    )
    (comp (ref "R153")
      (value "10K")
      (fields
        (field (name "BOM_Manufacturer Part") "0603WAF1002T5E")
        (field (name "BOM_Supplier Part") "C25804")
      )
      (libsource (lib "") (part "0603WAF1002T5E"))
    )
    (comp (ref "R154")
      (value "2.2K")
      (fields
        (field (name "BOM_Manufacturer Part") "0603WAF2201T5E")
        (field (name "BOM_Supplier Part") "C4190")
      )
      (libsource (lib "") (part "0603WAF2201T5E"))
    )
    (comp (ref "R296")
      (value "220")
      (fields
        (field (name "BOM_Manufacturer Part") "0402WGF2200TCE")
        (field (name "BOM_Supplier Part") "C25091")
      )
      (libsource (lib "") (part "0402WGF2200TCE"))
    )
    (comp (ref "R298")
      (value "680")
      (fields
        (field (name "BOM_Manufacturer Part") "0402WGF6800TCE")
        (field (name "BOM_Supplier Part") "C25130")
      )
      (libsource (lib "") (part "0402WGF6800TCE"))
    )
    (comp (ref "R362")
      (value "2.4K")
      (fields
        (field (name "BOM_Manufacturer Part") "1206W4F2401T5E")
        (field (name "BOM_Supplier Part") "C17949")
      )
      (libsource (lib "") (part "1206W4F2401T5E_1"))
    )
    (comp (ref "SJ1") (value "RS485 120R") (libsource (lib "") (part "JUMPER-PAD-2-NOYES_SILK")))
    (comp (ref "U3")
      (value "COIL 0")
      (fields
        (field (name "BOM_Manufacturer Part") "WJ15EDGVM-3.81-3P-14-00A")
        (field (name "BOM_Supplier Part") "C106870")
      )
      (libsource (lib "") (part "WJ15EDGVM-3.81-3P-14-00A"))
    )
    (comp (ref "U4")
      (value "COIL 1")
      (fields
        (field (name "BOM_Manufacturer Part") "WJ15EDGVM-3.81-3P-14-00A")
        (field (name "BOM_Supplier Part") "C106870")
      )
      (libsource (lib "") (part "WJ15EDGVM-3.81-3P-14-00A"))
    )
    (comp (ref "C12")
      (value "1nF")
      (fields
        (field (name "BOM_Manufacturer Part") "0402B102K500NT")
        (field (name "BOM_Supplier Part") "C1523")
      )
      (libsource (lib "") (part "0402B102K500NT"))
    )
    (comp (ref "C34")
      (value "1nF")
      (fields
        (field (name "BOM_Manufacturer Part") "0402B102K500NT")
        (field (name "BOM_Supplier Part") "C1523")
      )
      (libsource (lib "") (part "0402B102K500NT"))
    )
    (comp (ref "C35")
      (value "220nF")
      (fields
        (field (name "BOM_Manufacturer Part") "PE224J2A0501")
        (field (name "BOM_Supplier Part") "C393118")
      )
      (libsource (lib "") (part "PE224J2A0501"))
    )
    (comp (ref "C52")
      (value "10nF")
      (fields
        (field (name "BOM_Manufacturer Part") "0603B103K500NT")
        (field (name "BOM_Supplier Part") "C57112")
      )
      (libsource (lib "") (part "0603B103K500NT"))
    )
    (comp (ref "C53")
      (value "470pF")
      (fields
        (field (name "BOM_Manufacturer Part") "0603B471K500NT")
        (field (name "BOM_Supplier Part") "C1620")
      )
      (libsource (lib "") (part "0603B471K500NT_1"))
    )
    (comp (ref "C54")
      (value "470pF")
      (fields
        (field (name "BOM_Manufacturer Part") "0603B471K500NT")
        (field (name "BOM_Supplier Part") "C1620")
      )
      (libsource (lib "") (part "0603B471K500NT"))
    )
    (comp (ref "C55")
      (value "220nF")
      (fields
        (field (name "BOM_Manufacturer Part") "PE224J2A0501")
        (field (name "BOM_Supplier Part") "C393118")
      )
      (libsource (lib "") (part "PE224J2A0501"))
    )
    (comp (ref "C56")
      (value "1nF")
      (fields
        (field (name "BOM_Manufacturer Part") "0402B102K500NT")
        (field (name "BOM_Supplier Part") "C1523")
      )
      (libsource (lib "") (part "0402B102K500NT"))
    )
    (comp (ref "C57")
      (value "1nF")
      (fields
        (field (name "BOM_Manufacturer Part") "0402B102K500NT")
        (field (name "BOM_Supplier Part") "C1523")
      )
      (libsource (lib "") (part "0402B102K500NT"))
    )
    (comp (ref "C58")
      (value "470pF")
      (fields
        (field (name "BOM_Manufacturer Part") "0603B471K500NT")
        (field (name "BOM_Supplier Part") "C1620")
      )
      (libsource (lib "") (part "0603B471K500NT"))
    )
    (comp (ref "C59")
      (value "470pF")
      (fields
        (field (name "BOM_Manufacturer Part") "0603B471K500NT")
        (field (name "BOM_Supplier Part") "C1620")
      )
      (libsource (lib "") (part "0603B471K500NT_1"))
    )
    (comp (ref "C60")
      (value "10nF")
      (fields
        (field (name "BOM_Manufacturer Part") "0603B103K500NT")
        (field (name "BOM_Supplier Part") "C57112")
      )
      (libsource (lib "") (part "0603B103K500NT"))
    )
    (comp (ref "C61")
      (value "10nF")
      (fields
        (field (name "BOM_Manufacturer Part") "0603B103K500NT")
        (field (name "BOM_Supplier Part") "C57112")
      )
      (libsource (lib "") (part "0603B103K500NT"))
    )
    (comp (ref "C62")
      (value "10nF")
      (fields
        (field (name "BOM_Manufacturer Part") "0603B103K500NT")
        (field (name "BOM_Supplier Part") "C57112")
      )
      (libsource (lib "") (part "0603B103K500NT"))
    )
    (comp (ref "D1")
      (value "SM4007PL")
      (fields (field (name "BOM_Supplier Part") "C64898"))
      (libsource (lib "") (part "SM4007PL"))
    )
    (comp (ref "D2")
      (value "SM4007PL")
      (fields (field (name "BOM_Supplier Part") "C64898"))
      (libsource (lib "") (part "SM4007PL"))
    )
    (comp (ref "D3")
      (value "SM4007PL")
      (fields (field (name "BOM_Supplier Part") "C64898"))
      (libsource (lib "") (part "SM4007PL"))
    )
    (comp (ref "D4")
      (value "SM4007PL")
      (fields (field (name "BOM_Supplier Part") "C64898"))
      (libsource (lib "") (part "SM4007PL"))
    )
    (comp (ref "D5")
      (value "SM4007PL")
      (fields (field (name "BOM_Supplier Part") "C64898"))
      (libsource (lib "") (part "SM4007PL_1"))
    )
    (comp (ref "D6")
      (value "SM4007PL")
      (fields (field (name "BOM_Supplier Part") "C64898"))
      (libsource (lib "") (part "SM4007PL_1"))
    )
    (comp (ref "LED7")
      (value "RST0")
      (fields
        (field (name "BOM_Manufacturer Part") "0603White light")
        (field (name "BOM_Supplier Part") "C2290")
      )
      (libsource (lib "") (part "0603White light_C2290"))
    )
    (comp (ref "LED15")
      (value "RST1")
      (fields
        (field (name "BOM_Manufacturer Part") "0603White light")
        (field (name "BOM_Supplier Part") "C2290")
      )
      (libsource (lib "") (part "0603White light_C2290"))
    )
    (comp (ref "Q6")
      (value "S8050_C2146")
      (fields (field (name "BOM_Manufacturer Part") "S8050") (field (name "BOM_Supplier Part") "C2146"))
      (libsource (lib "") (part "S8050_C2146"))
    )
    (comp (ref "Q8")
      (value "S8050_C2146")
      (fields (field (name "BOM_Manufacturer Part") "S8050") (field (name "BOM_Supplier Part") "C2146"))
      (libsource (lib "") (part "S8050_C2146"))
    )
    (comp (ref "Q18")
      (value "S8050_C2146")
      (fields (field (name "BOM_Manufacturer Part") "S8050") (field (name "BOM_Supplier Part") "C2146"))
      (libsource (lib "") (part "S8050_C2146"))
    )
    (comp (ref "Q19")
      (value "AO3401A")
      (fields (field (name "BOM_Supplier Part") "C15127"))
      (libsource (lib "") (part "AO3401A"))
    )
    (comp (ref "Q20")
      (value "AO3401A")
      (fields (field (name "BOM_Supplier Part") "C15127"))
      (libsource (lib "") (part "AO3401A"))
    )
    (comp (ref "Q21")
      (value "S8050_C2146")
      (fields (field (name "BOM_Manufacturer Part") "S8050") (field (name "BOM_Supplier Part") "C2146"))
      (libsource (lib "") (part "S8050_C2146"))
    )
    (comp (ref "R11")
      (value "10K")
      (fields
        (field (name "BOM_Manufacturer Part") "0402WGF1002TCE")
        (field (name "BOM_Supplier Part") "C25744")
      )
      (libsource (lib "") (part "0402WGF1002TCE_1"))
    )
    (comp (ref "R25")
      (value "330")
      (fields
        (field (name "BOM_Manufacturer Part") "0402WGF3300TCE")
        (field (name "BOM_Supplier Part") "C25104")
      )
      (libsource (lib "") (part "0402WGF3300TCE_2"))
    )
    (comp (ref "R30")
      (value "330")
      (fields
        (field (name "BOM_Manufacturer Part") "0402WGF3300TCE")
        (field (name "BOM_Supplier Part") "C25104")
      )
      (libsource (lib "") (part "0402WGF3300TCE"))
    )
    (comp (ref "R45")
      (value "10K")
      (fields
        (field (name "BOM_Manufacturer Part") "0402WGF1002TCE")
        (field (name "BOM_Supplier Part") "C25744")
      )
      (libsource (lib "") (part "0402WGF1002TCE_1"))
    )
    (comp (ref "R69")
      (value "1K")
      (fields
        (field (name "BOM_Manufacturer Part") "0402WGF1001TCE")
        (field (name "BOM_Supplier Part") "C11702")
      )
      (libsource (lib "") (part "0402WGF1001TCE"))
    )
    (comp (ref "R70")
      (value "2.2K")
      (fields
        (field (name "BOM_Manufacturer Part") "0603WAF2201T5E")
        (field (name "BOM_Supplier Part") "C4190")
      )
      (libsource (lib "") (part "0603WAF2201T5E"))
    )
    (comp (ref "R71")
      (value "10K")
      (fields
        (field (name "BOM_Manufacturer Part") "0402WGF1002TCE")
        (field (name "BOM_Supplier Part") "C25744")
      )
      (libsource (lib "") (part "0402WGF1002TCE_1"))
    )
    (comp (ref "R72")
      (value "10K")
      (fields
        (field (name "BOM_Manufacturer Part") "0402WGF1002TCE")
        (field (name "BOM_Supplier Part") "C25744")
      )
      (libsource (lib "") (part "0402WGF1002TCE_2"))
    )
    (comp (ref "R73")
      (value "1K")
      (fields
        (field (name "BOM_Manufacturer Part") "0402WGF1001TCE")
        (field (name "BOM_Supplier Part") "C11702")
      )
      (libsource (lib "") (part "0402WGF1001TCE_1"))
    )
    (comp (ref "R74")
      (value "10K")
      (fields
        (field (name "BOM_Manufacturer Part") "0402WGF1002TCE")
        (field (name "BOM_Supplier Part") "C25744")
      )
      (libsource (lib "") (part "0402WGF1002TCE_2"))
    )
    (comp (ref "R77")
      (value "1K")
      (fields
        (field (name "BOM_Manufacturer Part") "0402WGF1001TCE")
        (field (name "BOM_Supplier Part") "C11702")
      )
      (libsource (lib "") (part "0402WGF1001TCE"))
    )
    (comp (ref "R78")
      (value "10K")
      (fields
        (field (name "BOM_Manufacturer Part") "0402WGF1002TCE")
        (field (name "BOM_Supplier Part") "C25744")
      )
      (libsource (lib "") (part "0402WGF1002TCE_2"))
    )
    (comp (ref "R79")
      (value "150")
      (fields
        (field (name "BOM_Manufacturer Part") "0402WGF1500TCE")
        (field (name "BOM_Supplier Part") "C25082")
      )
      (libsource (lib "") (part "0402WGF1500TCE"))
    )
    (comp (ref "R80")
      (value "330")
      (fields
        (field (name "BOM_Manufacturer Part") "0603WAF3300T5E")
        (field (name "BOM_Supplier Part") "C23138")
      )
      (libsource (lib "") (part "0603WAF3300T5E"))
    )
    (comp (ref "R82")
      (value "10K")
      (fields
        (field (name "BOM_Manufacturer Part") "0402WGF1002TCE")
        (field (name "BOM_Supplier Part") "C25744")
      )
      (libsource (lib "") (part "0402WGF1002TCE_2"))
    )
    (comp (ref "R85")
      (value "330")
      (fields
        (field (name "BOM_Manufacturer Part") "0402WGF3300TCE")
        (field (name "BOM_Supplier Part") "C25104")
      )
      (libsource (lib "") (part "0402WGF3300TCE_1"))
    )
    (comp (ref "R86")
      (value "150")
      (fields
        (field (name "BOM_Manufacturer Part") "0402WGF1500TCE")
        (field (name "BOM_Supplier Part") "C25082")
      )
      (libsource (lib "") (part "0402WGF1500TCE"))
    )
    (comp (ref "R87")
      (value "10K")
      (fields
        (field (name "BOM_Manufacturer Part") "0402WGF1002TCE")
        (field (name "BOM_Supplier Part") "C25744")
      )
      (libsource (lib "") (part "0402WGF1002TCE_2"))
    )
    (comp (ref "R88")
      (value "10K")
      (fields
        (field (name "BOM_Manufacturer Part") "0402WGF1002TCE")
        (field (name "BOM_Supplier Part") "C25744")
      )
      (libsource (lib "") (part "0402WGF1002TCE_3"))
    )
    (comp (ref "R89")
      (value "10K")
      (fields
        (field (name "BOM_Manufacturer Part") "0402WGF1002TCE")
        (field (name "BOM_Supplier Part") "C25744")
      )
      (libsource (lib "") (part "0402WGF1002TCE_3"))
    )
    (comp (ref "R90")
      (value "10K")
      (fields
        (field (name "BOM_Manufacturer Part") "0402WGF1002TCE")
        (field (name "BOM_Supplier Part") "C25744")
      )
      (libsource (lib "") (part "0402WGF1002TCE"))
    )
    (comp (ref "R91")
      (value "10K")
      (fields
        (field (name "BOM_Manufacturer Part") "0402WGF1002TCE")
        (field (name "BOM_Supplier Part") "C25744")
      )
      (libsource (lib "") (part "0402WGF1002TCE_1"))
    )
    (comp (ref "R92")
      (value "150")
      (fields
        (field (name "BOM_Manufacturer Part") "0402WGF1500TCE")
        (field (name "BOM_Supplier Part") "C25082")
      )
      (libsource (lib "") (part "0402WGF1500TCE"))
    )
    (comp (ref "R93")
      (value "220K")
      (fields
        (field (name "BOM_Manufacturer Part") "0603WAF2203T5E")
        (field (name "BOM_Supplier Part") "C22961")
      )
      (libsource (lib "") (part "0603WAF2203T5E"))
    )
    (comp (ref "R94")
      (value "220K")
      (fields
        (field (name "BOM_Manufacturer Part") "0603WAF2203T5E")
        (field (name "BOM_Supplier Part") "C22961")
      )
      (libsource (lib "") (part "0603WAF2203T5E"))
    )
    (comp (ref "R95")
      (value "10M")
      (fields
        (field (name "BOM_Manufacturer Part") "0603WAF1005T5E")
        (field (name "BOM_Supplier Part") "C7250")
      )
      (libsource (lib "") (part "0603WAF1005T5E"))
    )
    (comp (ref "R96")
      (value "22K")
      (fields
        (field (name "BOM_Manufacturer Part") "0402WGF2202TCE")
        (field (name "BOM_Supplier Part") "C25768")
      )
      (libsource (lib "") (part "0402WGF2202TCE"))
    )
    (comp (ref "R97")
      (value "10K")
      (fields
        (field (name "BOM_Manufacturer Part") "0402WGF1002TCE")
        (field (name "BOM_Supplier Part") "C25744")
      )
      (libsource (lib "") (part "0402WGF1002TCE_1"))
    )
    (comp (ref "R100")
      (value "220K")
      (fields
        (field (name "BOM_Manufacturer Part") "0603WAF2203T5E")
        (field (name "BOM_Supplier Part") "C22961")
      )
      (libsource (lib "") (part "0603WAF2203T5E"))
    )
    (comp (ref "R101")
      (value "1.2M")
      (fields
        (field (name "BOM_Manufacturer Part") "0805W8F1204T5E")
        (field (name "BOM_Supplier Part") "C17380")
      )
      (libsource (lib "") (part "0805W8F1204T5E"))
    )
    (comp (ref "R102")
      (value "100K")
      (fields
        (field (name "BOM_Manufacturer Part") "0603WAF1003T5E")
        (field (name "BOM_Supplier Part") "C25803")
      )
      (libsource (lib "") (part "0603WAF1003T5E"))
    )
    (comp (ref "R103")
      (value "10K")
      (fields
        (field (name "BOM_Manufacturer Part") "0402WGF1002TCE")
        (field (name "BOM_Supplier Part") "C25744")
      )
      (libsource (lib "") (part "0402WGF1002TCE_1"))
    )
    (comp (ref "R104")
      (value "6.8K")
      (fields
        (field (name "BOM_Manufacturer Part") "0603WAF6801T5E")
        (field (name "BOM_Supplier Part") "C23212")
      )
      (libsource (lib "") (part "0603WAF6801T5E"))
    )
    (comp (ref "R105")
      (value "100")
      (fields
        (field (name "BOM_Manufacturer Part") "0603WAF1000T5E")
        (field (name "BOM_Supplier Part") "C22775")
      )
      (libsource (lib "") (part "0603WAF1000T5E"))
    )
    (comp (ref "R106")
      (value "22K")
      (fields
        (field (name "BOM_Manufacturer Part") "0402WGF2202TCE")
        (field (name "BOM_Supplier Part") "C25768")
      )
      (libsource (lib "") (part "0402WGF2202TCE"))
    )
    (comp (ref "R107")
      (value "22K")
      (fields
        (field (name "BOM_Manufacturer Part") "0402WGF2202TCE")
        (field (name "BOM_Supplier Part") "C25768")
      )
      (libsource (lib "") (part "0402WGF2202TCE"))
    )
    (comp (ref "R108")
      (value "100K")
      (fields
        (field (name "BOM_Manufacturer Part") "0603WAF1003T5E")
        (field (name "BOM_Supplier Part") "C25803")
      )
      (libsource (lib "") (part "0603WAF1003T5E"))
    )
    (comp (ref "R109")
      (value "100K")
      (fields
        (field (name "BOM_Manufacturer Part") "0603WAF1003T5E")
        (field (name "BOM_Supplier Part") "C25803")
      )
      (libsource (lib "") (part "0603WAF1003T5E"))
    )
    (comp (ref "R110")
      (value "10K")
      (fields
        (field (name "BOM_Manufacturer Part") "0603WAF1002T5E")
        (field (name "BOM_Supplier Part") "C25804")
      )
      (libsource (lib "") (part "0603WAF1002T5E"))
    )
    (comp (ref "R111")
      (value "10K")
      (fields
        (field (name "BOM_Manufacturer Part") "0603WAF1002T5E")
        (field (name "BOM_Supplier Part") "C25804")
      )
      (libsource (lib "") (part "0603WAF1002T5E"))
    )
    (comp (ref "R112")
      (value "47")
      (fields
        (field (name "BOM_Manufacturer Part") "0603WAF470JT5E")
        (field (name "BOM_Supplier Part") "C23182")
      )
      (libsource (lib "") (part "0603WAF470JT5E"))
    )
    (comp (ref "R113")
      (value "150")
      (fields
        (field (name "BOM_Manufacturer Part") "0805W8F1500T5E")
        (field (name "BOM_Supplier Part") "C17471")
      )
      (libsource (lib "") (part "0805W8F1500T5E"))
    )
    (comp (ref "R115")
      (value "1K")
      (fields
        (field (name "BOM_Manufacturer Part") "0402WGF1001TCE")
        (field (name "BOM_Supplier Part") "C11702")
      )
      (libsource (lib "") (part "0402WGF1001TCE"))
    )
    (comp (ref "R116")
      (value "150")
      (fields
        (field (name "BOM_Manufacturer Part") "0805W8F1500T5E")
        (field (name "BOM_Supplier Part") "C17471")
      )
      (libsource (lib "") (part "0805W8F1500T5E"))
    )
    (comp (ref "R117")
      (value "10K")
      (fields
        (field (name "BOM_Manufacturer Part") "0603WAF1002T5E")
        (field (name "BOM_Supplier Part") "C25804")
      )
      (libsource (lib "") (part "0603WAF1002T5E"))
    )
    (comp (ref "R118")
      (value "10K")
      (fields
        (field (name "BOM_Manufacturer Part") "0603WAF1002T5E")
        (field (name "BOM_Supplier Part") "C25804")
      )
      (libsource (lib "") (part "0603WAF1002T5E"))
    )
    (comp (ref "R119")
      (value "100K")
      (fields
        (field (name "BOM_Manufacturer Part") "0603WAF1003T5E")
        (field (name "BOM_Supplier Part") "C25803")
      )
      (libsource (lib "") (part "0603WAF1003T5E"))
    )
    (comp (ref "R120")
      (value "10K")
      (fields
        (field (name "BOM_Manufacturer Part") "0402WGF1002TCE")
        (field (name "BOM_Supplier Part") "C25744")
      )
      (libsource (lib "") (part "0402WGF1002TCE_1"))
    )
    (comp (ref "R121")
      (value "22K")
      (fields
        (field (name "BOM_Manufacturer Part") "0402WGF2202TCE")
        (field (name "BOM_Supplier Part") "C25768")
      )
      (libsource (lib "") (part "0402WGF2202TCE"))
    )
    (comp (ref "R122")
      (value "10M")
      (fields
        (field (name "BOM_Manufacturer Part") "0603WAF1005T5E")
        (field (name "BOM_Supplier Part") "C7250")
      )
      (libsource (lib "") (part "0603WAF1005T5E"))
    )
    (comp (ref "R123")
      (value "47")
      (fields
        (field (name "BOM_Manufacturer Part") "0603WAF470JT5E")
        (field (name "BOM_Supplier Part") "C23182")
      )
      (libsource (lib "") (part "0603WAF470JT5E"))
    )
    (comp (ref "R124")
      (value "100K")
      (fields
        (field (name "BOM_Manufacturer Part") "0603WAF1003T5E")
        (field (name "BOM_Supplier Part") "C25803")
      )
      (libsource (lib "") (part "0603WAF1003T5E"))
    )
    (comp (ref "R125")
      (value "22K")
      (fields
        (field (name "BOM_Manufacturer Part") "0402WGF2202TCE")
        (field (name "BOM_Supplier Part") "C25768")
      )
      (libsource (lib "") (part "0402WGF2202TCE"))
    )
    (comp (ref "R126")
      (value "22K")
      (fields
        (field (name "BOM_Manufacturer Part") "0402WGF2202TCE")
        (field (name "BOM_Supplier Part") "C25768")
      )
      (libsource (lib "") (part "0402WGF2202TCE"))
    )
    (comp (ref "R127")
      (value "100")
      (fields
        (field (name "BOM_Manufacturer Part") "0603WAF1000T5E")
        (field (name "BOM_Supplier Part") "C22775")
      )
      (libsource (lib "") (part "0603WAF1000T5E"))
    )
    (comp (ref "R128")
      (value "6.8K")
      (fields
        (field (name "BOM_Manufacturer Part") "0603WAF6801T5E")
        (field (name "BOM_Supplier Part") "C23212")
      )
      (libsource (lib "") (part "0603WAF6801T5E"))
    )
    (comp (ref "R129")
      (value "10K")
      (fields
        (field (name "BOM_Manufacturer Part") "0402WGF1002TCE")
        (field (name "BOM_Supplier Part") "C25744")
      )
      (libsource (lib "") (part "0402WGF1002TCE_1"))
    )
    (comp (ref "R130")
      (value "100K")
      (fields
        (field (name "BOM_Manufacturer Part") "0603WAF1003T5E")
        (field (name "BOM_Supplier Part") "C25803")
      )
      (libsource (lib "") (part "0603WAF1003T5E"))
    )
    (comp (ref "R131")
      (value "1.2M")
      (fields
        (field (name "BOM_Manufacturer Part") "0805W8F1204T5E")
        (field (name "BOM_Supplier Part") "C17380")
      )
      (libsource (lib "") (part "0805W8F1204T5E"))
    )
    (comp (ref "R132")
      (value "220K")
      (fields
        (field (name "BOM_Manufacturer Part") "0603WAF2203T5E")
        (field (name "BOM_Supplier Part") "C22961")
      )
      (libsource (lib "") (part "0603WAF2203T5E"))
    )
    (comp (ref "R133")
      (value "1K")
      (fields
        (field (name "BOM_Manufacturer Part") "0402WGF1001TCE")
        (field (name "BOM_Supplier Part") "C11702")
      )
      (libsource (lib "") (part "0402WGF1001TCE_2"))
    )
    (comp (ref "R134")
      (value "1K")
      (fields
        (field (name "BOM_Manufacturer Part") "0402WGF1001TCE")
        (field (name "BOM_Supplier Part") "C11702")
      )
      (libsource (lib "") (part "0402WGF1001TCE"))
    )
    (comp (ref "R135")
      (value "330")
      (fields
        (field (name "BOM_Manufacturer Part") "0402WGF3300TCE")
        (field (name "BOM_Supplier Part") "C25104")
      )
      (libsource (lib "") (part "0402WGF3300TCE_1"))
    )
    (comp (ref "R145")
      (value "2.2K")
      (fields
        (field (name "BOM_Manufacturer Part") "0603WAF2201T5E")
        (field (name "BOM_Supplier Part") "C4190")
      )
      (libsource (lib "") (part "0603WAF2201T5E"))
    )
    (comp (ref "SJ2") (value "GP7") (libsource (lib "") (part "JUMPER-PAD-2-NC_BY_TRACE")))
    (comp (ref "SJ3") (value "PO-1") (libsource (lib "") (part "JUMPER-PAD-2-NOYES_SILK")))
    (comp (ref "SJ4") (value "PO-1") (libsource (lib "") (part "JUMPER-PAD-2-NOYES_SILK")))
    (comp (ref "SJ5") (value "PO-2") (libsource (lib "") (part "JUMPER-PAD-2-NOYES_SILK")))
    (comp (ref "SJ6") (value "PO-2") (libsource (lib "") (part "JUMPER-PAD-2-NOYES_SILK")))
    (comp (ref "SJ17") (value "GP6") (libsource (lib "") (part "JUMPER-PAD-2-NC_BY_TRACE")))
    (comp (ref "U13")
      (value "MCP6002T-I/SN")
      (fields (field (name "BOM_Supplier Part") "C7377"))
      (libsource (lib "") (part "MCP6002T-I/SN"))
    )
    (comp (ref "U14")
      (value "MCP6002T-I/SN")
      (fields (field (name "BOM_Supplier Part") "C7377"))
      (libsource (lib "") (part "MCP6002T-I/SN"))
    )
    (comp (ref "U15")
      (value "LM358DR2G")
      (fields (field (name "BOM_Supplier Part") "C7950"))
      (libsource (lib "") (part "LM358DR2G"))
    )
    (comp (ref "U16")
      (value "MCP6002T-I/SN")
      (fields (field (name "BOM_Supplier Part") "C7377"))
      (libsource (lib "") (part "MCP6002T-I/SN"))
    )
    (comp (ref "U17")
      (value "MCP6002T-I/SN")
      (fields (field (name "BOM_Supplier Part") "C7377"))
      (libsource (lib "") (part "MCP6002T-I/SN"))
    )
    (comp (ref "U18")
      (value "LM358DR2G")
      (fields (field (name "BOM_Supplier Part") "C7950"))
      (libsource (lib "") (part "LM358DR2G"))
    )
    (comp (ref "C8")
      (value "1uF")
      (fields
        (field (name "BOM_Manufacturer Part") "CL10A105KB8NNNC")
        (field (name "BOM_Supplier Part") "C15849")
      )
      (libsource (lib "") (part "CL10A105KB8NNNC"))
    )
    (comp (ref "C21")
      (value "470uF")
      (fields
        (field (name "BOM_Manufacturer Part") "RVT1V471M1010")
        (field (name "BOM_Supplier Part") "C3350")
      )
      (libsource (lib "") (part "RVT1V471M1010"))
    )
    (comp (ref "C22")
      (value "100uF")
      (fields
        (field (name "BOM_Manufacturer Part") "CL31A107MQHNNNE")
        (field (name "BOM_Supplier Part") "C15008")
      )
      (libsource (lib "") (part "CL31A107MQHNNNE"))
    )
    (comp (ref "C23")
      (value "100uF")
      (fields
        (field (name "BOM_Manufacturer Part") "EMK325ABJ107MM-P")
        (field (name "BOM_Supplier Part") "C90143")
      )
      (libsource (lib "") (part "EMK325ABJ107MM-P"))
    )
    (comp (ref "C27")
      (value "10uF")
      (fields
        (field (name "BOM_Manufacturer Part") "CA45-A-16V-10uF-K")
        (field (name "BOM_Supplier Part") "C128254")
      )
      (libsource (lib "") (part "CA45-A-16V-10UF-K"))
    )
    (comp (ref "C28")
      (value "100nF")
      (fields
        (field (name "BOM_Manufacturer Part") "CL05B104KO5NNNC")
        (field (name "BOM_Supplier Part") "C1525")
      )
      (libsource (lib "") (part "CL05B104KO5NNNC"))
    )
    (comp (ref "C48")
      (value "100uF")
      (fields
        (field (name "BOM_Manufacturer Part") "CL31A107MQHNNNE")
        (field (name "BOM_Supplier Part") "C15008")
      )
      (libsource (lib "") (part "CL31A107MQHNNNE"))
    )
    (comp (ref "C49")
      (value "100nF")
      (fields
        (field (name "BOM_Manufacturer Part") "CL05B104KO5NNNC")
        (field (name "BOM_Supplier Part") "C1525")
      )
      (libsource (lib "") (part "CL05B104KO5NNNC"))
    )
    (comp (ref "C50")
      (value "10uF")
      (fields
        (field (name "BOM_Manufacturer Part") "CA45-A-16V-10uF-K")
        (field (name "BOM_Supplier Part") "C128254")
      )
      (libsource (lib "") (part "CA45-A-16V-10UF-K"))
    )
    (comp (ref "C67")
      (value "1uF")
      (fields
        (field (name "BOM_Manufacturer Part") "CL10A105KB8NNNC")
        (field (name "BOM_Supplier Part") "C15849")
      )
      (libsource (lib "") (part "CL10A105KB8NNNC"))
    )
    (comp (ref "C68")
      (value "470uF")
      (fields
        (field (name "BOM_Manufacturer Part") "RVT1V471M1010")
        (field (name "BOM_Supplier Part") "C3350")
      )
      (libsource (lib "") (part "RVT1V471M1010"))
    )
    (comp (ref "C69")
      (value "100uF")
      (fields
        (field (name "BOM_Manufacturer Part") "EMK325ABJ107MM-P")
        (field (name "BOM_Supplier Part") "C90143")
      )
      (libsource (lib "") (part "EMK325ABJ107MM-P"))
    )
    (comp (ref "D25")
      (value "1N5819WS")
      (fields (field (name "BOM_Supplier Part") "C191023"))
      (libsource (lib "") (part "1N5819WS"))
    )
    (comp (ref "D32")
      (value "1N5819WS")
      (fields (field (name "BOM_Supplier Part") "C191023"))
      (libsource (lib "") (part "1N5819WS"))
    )
    (comp (ref "L2")
      (value "100uH")
      (fields
        (field (name "BOM_Manufacturer Part") "SMMS1360-101M")
        (field (name "BOM_Supplier Part") "C149534")
      )
      (libsource (lib "") (part "SMMS1360-101M"))
    )
    (comp (ref "L3")
      (value "100uH")
      (fields
        (field (name "BOM_Manufacturer Part") "SMMS1360-101M")
        (field (name "BOM_Supplier Part") "C149534")
      )
      (libsource (lib "") (part "SMMS1360-101M"))
    )
    (comp (ref "R68")
      (value "100K")
      (fields
        (field (name "BOM_Manufacturer Part") "0603WAF1003T5E")
        (field (name "BOM_Supplier Part") "C25803")
      )
      (libsource (lib "") (part "0603WAF1003T5E"))
    )
    (comp (ref "R142")
      (value "100K")
      (fields
        (field (name "BOM_Manufacturer Part") "0603WAF1003T5E")
        (field (name "BOM_Supplier Part") "C25803")
      )
      (libsource (lib "") (part "0603WAF1003T5E"))
    )
    (comp (ref "U9")
      (value "LM2576HVS-3.3")
      (fields (field (name "BOM_Supplier Part") "C347436"))
      (libsource (lib "") (part "LM2576HVS-3.3"))
    )
    (comp (ref "U10")
      (value "XL1509-5.0E1")
      (fields (field (name "BOM_Supplier Part") "C61063"))
      (libsource (lib "") (part "XL1509-5.0E1"))
    )
  )
  (nets
    (net (code "1") (name "3.3V_out") (class "Default")
      (node (ref "D32") (pin "1") (pinfunction "C_1") (pintype "unspecified"))
      (node (ref "L3") (pin "1") (pinfunction "1_1") (pintype "unspecified"))
      (node (ref "U9") (pin "2") (pinfunction "Output_2") (pintype "unspecified"))
    )
    (net (code "2") (name "3V3") (class "Default")
      (node (ref "C14") (pin "2") (pinfunction "2_2") (pintype "input"))
      (node (ref "C15") (pin "2") (pinfunction "2_2") (pintype "input"))
      (node (ref "C23") (pin "2") (pinfunction "2_2") (pintype "unspecified"))
      (node (ref "C24") (pin "2") (pinfunction "2_2") (pintype "input"))
      (node (ref "C25") (pin "2") (pinfunction "2_2") (pintype "input"))
      (node (ref "C49") (pin "1") (pinfunction "1_1") (pintype "input"))
      (node (ref "C50") (pin "1") (pinfunction "1_1") (pintype "input"))
      (node (ref "C67") (pin "2") (pinfunction "2_2") (pintype "input"))
      (node (ref "C68") (pin "1") (pinfunction "1_1") (pintype "input"))
      (node (ref "C9") (pin "2") (pinfunction "2_2") (pintype "input"))
      (node (ref "D16") (pin "1") (pinfunction "C_1") (pintype "unspecified"))
      (node (ref "L3") (pin "2") (pinfunction "2_2") (pintype "unspecified"))
      (node (ref "R30") (pin "1") (pinfunction "1_1") (pintype "input"))
      (node (ref "R34") (pin "1") (pinfunction "1_1") (pintype "input"))
      (node (ref "R35") (pin "2") (pinfunction "2_2") (pintype "input"))
      (node (ref "R36") (pin "2") (pinfunction "2_2") (pintype "input"))
      (node (ref "R38") (pin "2") (pinfunction "2_2") (pintype "input"))
      (node (ref "R68") (pin "2") (pinfunction "2_2") (pintype "input"))
      (node (ref "R7") (pin "1") (pinfunction "1_1") (pintype "input"))
      (node (ref "R85") (pin "2") (pinfunction "2_2") (pintype "input"))
      (node (ref "U1") (pin "16") (pinfunction "VPU_16") (pintype "unspecified"))
      (node (ref "U1") (pin "4") (pinfunction "VS_4") (pintype "unspecified"))
      (node (ref "U2") (pin "16") (pinfunction "VPU_16") (pintype "unspecified"))
      (node (ref "U2") (pin "4") (pinfunction "VS_4") (pintype "unspecified"))
      (node (ref "U2") (pin "5") (pinfunction "A0_5") (pintype "unspecified"))
      (node (ref "U5") (pin "8") (pinfunction "VCC_8") (pintype "unspecified"))
      (node (ref "U6") (pin "13") (pinfunction "VDD_13") (pintype "unspecified"))
      (node (ref "U9") (pin "4") (pinfunction "Feedback_4") (pintype "unspecified"))
    )
    (net (code "3") (name "3V3_PI") (class "Default")
      (node (ref "C13") (pin "1") (pinfunction "1_1") (pintype "input"))
      (node (ref "D16") (pin "2") (pinfunction "A_2") (pintype "unspecified"))
      (node (ref "R31") (pin "2") (pinfunction "2_2") (pintype "input"))
      (node (ref "R32") (pin "2") (pinfunction "2_2") (pintype "input"))
      (node (ref "R33") (pin "2") (pinfunction "2_2") (pintype "input"))
      (node (ref "U11") (pin "36") (pinfunction "3V3_OUT_36") (pintype "unspecified"))
      (node (ref "U7") (pin "8") (pinfunction "VCC_8") (pintype "unspecified"))
    )
    (net (code "4") (name "4-20MA_NEG_1") (class "Default")
      (node (ref "CN2") (pin "1") (pinfunction "1_1") (pintype "unspecified"))
      (node (ref "R13") (pin "1") (pinfunction "1_1") (pintype "input"))
      (node (ref "R21") (pin "2") (pinfunction "2_2") (pintype "unspecified"))
      (node (ref "SJ15") (pin "2") (pinfunction "2_2") (pintype "unspecified"))
    )
    (net (code "5") (name "4-20MA_NEG_2") (class "Default")
      (node (ref "CN2") (pin "2") (pinfunction "2_2") (pintype "unspecified"))
      (node (ref "R18") (pin "1") (pinfunction "1_1") (pintype "input"))
      (node (ref "R27") (pin "1") (pinfunction "1_1") (pintype "unspecified"))
      (node (ref "SJ14") (pin "2") (pinfunction "2_2") (pintype "unspecified"))
    )
    (net (code "6") (name "4-20MA_NEG_3") (class "Default")
      (node (ref "CN2") (pin "3") (pinfunction "3_3") (pintype "unspecified"))
      (node (ref "R23") (pin "1") (pinfunction "1_1") (pintype "input"))
      (node (ref "R26") (pin "1") (pinfunction "1_1") (pintype "unspecified"))
      (node (ref "SJ13") (pin "2") (pinfunction "2_2") (pintype "unspecified"))
    )
    (net (code "7") (name "4-20MA_NEG_4") (class "Default")
      (node (ref "CN2") (pin "4") (pinfunction "4_4") (pintype "unspecified"))
      (node (ref "R22") (pin "2") (pinfunction "2_2") (pintype "unspecified"))
      (node (ref "R28") (pin "1") (pinfunction "1_1") (pintype "input"))
      (node (ref "SJ12") (pin "2") (pinfunction "2_2") (pintype "unspecified"))
    )
    (net (code "8") (name "4-20MA_NEG_10") (class "Default")
      (node (ref "CN11") (pin "1") (pinfunction "1_1") (pintype "unspecified"))
      (node (ref "R14") (pin "1") (pinfunction "1_1") (pintype "input"))
      (node (ref "R21") (pin "1") (pinfunction "1_1") (pintype "unspecified"))
    )
    (net (code "9") (name "4-20MA_NEG_20") (class "Default")
      (node (ref "CN13") (pin "1") (pinfunction "1_1") (pintype "unspecified"))
      (node (ref "R19") (pin "1") (pinfunction "1_1") (pintype "input"))
      (node (ref "R27") (pin "2") (pinfunction "2_2") (pintype "unspecified"))
    )
    (net (code "10") (name "4-20MA_NEG_30") (class "Default")
      (node (ref "CN17") (pin "1") (pinfunction "1_1") (pintype "unspecified"))
      (node (ref "R24") (pin "1") (pinfunction "1_1") (pintype "input"))
      (node (ref "R26") (pin "2") (pinfunction "2_2") (pintype "unspecified"))
    )
    (net (code "11") (name "4-20MA_NEG_40") (class "Default")
      (node (ref "CN24") (pin "1") (pinfunction "1_1") (pintype "unspecified"))
      (node (ref "R22") (pin "1") (pinfunction "1_1") (pintype "unspecified"))
      (node (ref "R29") (pin "1") (pinfunction "1_1") (pintype "input"))
    )
    (net (code "12") (name "5V0") (class "Default")
      (node (ref "C21") (pin "1") (pinfunction "1_1") (pintype "input"))
      (node (ref "C27") (pin "1") (pinfunction "1_1") (pintype "input"))
      (node (ref "C28") (pin "1") (pinfunction "1_1") (pintype "input"))
      (node (ref "C33") (pin "1") (pinfunction "1_1") (pintype "input"))
      (node (ref "C63") (pin "2") (pinfunction "2_2") (pintype "input"))
      (node (ref "C64") (pin "2") (pinfunction "2_2") (pintype "input"))
      (node (ref "C69") (pin "2") (pinfunction "2_2") (pintype "unspecified"))
      (node (ref "C8") (pin "2") (pinfunction "2_2") (pintype "input"))
      (node (ref "D23") (pin "2") (pinfunction "A_2") (pintype "unspecified"))
      (node (ref "D24") (pin "1") (pinfunction "C_1") (pintype "unspecified"))
      (node (ref "H1") (pin "1") (pinfunction "VCC_1") (pintype "unspecified"))
      (node (ref "L2") (pin "2") (pinfunction "2_2") (pintype "unspecified"))
      (node (ref "Q13") (pin "2") (pinfunction "C_2") (pintype "unspecified"))
      (node (ref "Q14") (pin "2") (pinfunction "C_2") (pintype "unspecified"))
      (node (ref "Q9") (pin "2") (pinfunction "S_2") (pintype "unspecified"))
      (node (ref "R101") (pin "1") (pinfunction "1_1") (pintype "input"))
      (node (ref "R131") (pin "1") (pinfunction "1_1") (pintype "input"))
      (node (ref "R142") (pin "2") (pinfunction "2_2") (pintype "input"))
      (node (ref "R348") (pin "2") (pinfunction "2_2") (pintype "input"))
      (node (ref "R349") (pin "2") (pinfunction "2_2") (pintype "input"))
      (node (ref "R58") (pin "2") (pinfunction "2_2") (pintype "input"))
      (node (ref "U10") (pin "3") (pinfunction "FB_3") (pintype "unspecified"))
      (node (ref "U13") (pin "8") (pinfunction "VDD_8") (pintype "unspecified"))
      (node (ref "U14") (pin "8") (pinfunction "VDD_8") (pintype "unspecified"))
      (node (ref "U16") (pin "8") (pinfunction "VDD_8") (pintype "unspecified"))
      (node (ref "U17") (pin "8") (pinfunction "VDD_8") (pintype "unspecified"))
      (node (ref "U58") (pin "8") (pinfunction "VCC_8") (pintype "unspecified"))
      (node (ref "U59") (pin "8") (pinfunction "VCC_8") (pintype "unspecified"))
    )
    (net (code "13") (name "C0-0") (class "Default")
      (node (ref "C139") (pin "2") (pinfunction "2_2") (pintype "input"))
      (node (ref "CN1") (pin "2") (pinfunction "2_2") (pintype "unspecified"))
      (node (ref "D26") (pin "1") (pinfunction "C_1") (pintype "unspecified"))
      (node (ref "D27") (pin "1") (pinfunction "C_1") (pintype "unspecified"))
      (node (ref "R133") (pin "1") (pinfunction "1_1") (pintype "input"))
      (node (ref "R298") (pin "2") (pinfunction "2_2") (pintype "input"))
      (node (ref "R44") (pin "1") (pinfunction "1_1") (pintype "input"))
      (node (ref "R73") (pin "2") (pinfunction "2_2") (pintype "input"))
      (node (ref "U3") (pin "1") (pinfunction "1_1") (pintype "unspecified"))
      (node (ref "U4") (pin "1") (pinfunction "1_1") (pintype "unspecified"))
    )
    (net (code "14") (name "C0-1") (class "Default")
      (node (ref "C141") (pin "2") (pinfunction "2_2") (pintype "input"))
      (node (ref "D30") (pin "1") (pinfunction "C_1") (pintype "unspecified"))
      (node (ref "Q14") (pin "3") (pinfunction "E_3") (pintype "unspecified"))
      (node (ref "R355") (pin "2") (pinfunction "2_2") (pintype "input"))
      (node (ref "R75") (pin "2") (pinfunction "2_2") (pintype "input"))
      (node (ref "U3") (pin "2") (pinfunction "2_2") (pintype "unspecified"))
    )
    (net (code "15") (name "C1-1") (class "Default")
      (node (ref "C140") (pin "2") (pinfunction "2_2") (pintype "input"))
      (node (ref "D29") (pin "1") (pinfunction "C_1") (pintype "unspecified"))
      (node (ref "Q13") (pin "3") (pinfunction "E_3") (pintype "unspecified"))
      (node (ref "R296") (pin "2") (pinfunction "2_2") (pintype "input"))
      (node (ref "R353") (pin "2") (pinfunction "2_2") (pintype "input"))
      (node (ref "U4") (pin "2") (pinfunction "2_2") (pintype "unspecified"))
    )
    (net (code "16") (name "GP0") (class "Default")
      (node (ref "R37") (pin "1") (pinfunction "1_1") (pintype "unspecified"))
      (node (ref "U11") (pin "1") (pinfunction "GP0_1") (pintype "unspecified"))
    )
    (net (code "17") (name "GP1") (class "Default")
      (node (ref "R49") (pin "1") (pinfunction "1_1") (pintype "unspecified"))
      (node (ref "U11") (pin "2") (pinfunction "GP1_2") (pintype "unspecified"))
    )
    (net (code "18") (name "GP2") (class "Default")
      (node (ref "R51") (pin "1") (pinfunction "1_1") (pintype "unspecified"))
      (node (ref "U11") (pin "4") (pinfunction "GP2_4") (pintype "unspecified"))
    )
    (net (code "19") (name "GP3") (class "Default")
      (node (ref "R54") (pin "1") (pinfunction "1_1") (pintype "unspecified"))
      (node (ref "U11") (pin "5") (pinfunction "GP3_5") (pintype "unspecified"))
    )
    (net (code "20") (name "GP4") (class "Default")
      (node (ref "R35") (pin "1") (pinfunction "1_1") (pintype "input"))
      (node (ref "U11") (pin "6") (pinfunction "GP4_6") (pintype "unspecified"))
      (node (ref "U5") (pin "4") (pinfunction "DI_4") (pintype "unspecified"))
    )
    (net (code "21") (name "GP5") (class "Default")
      (node (ref "R38") (pin "1") (pinfunction "1_1") (pintype "input"))
      (node (ref "U11") (pin "7") (pinfunction "GP5_7") (pintype "unspecified"))
      (node (ref "U5") (pin "1") (pinfunction "RO_1") (pintype "unspecified"))
    )
    (net (code "22") (name "GP6") (class "Default")
      (node (ref "R145") (pin "1") (pinfunction "1_1") (pintype "input"))
      (node (ref "U11") (pin "9") (pinfunction "GP6_9") (pintype "unspecified"))
    )
    (net (code "23") (name "GP7") (class "Default")
      (node (ref "R70") (pin "1") (pinfunction "1_1") (pintype "input"))
      (node (ref "U11") (pin "10") (pinfunction "GP7_10") (pintype "unspecified"))
    )
    (net (code "24") (name "GP14") (class "Default")
      (node (ref "R36") (pin "1") (pinfunction "1_1") (pintype "input"))
      (node (ref "U11") (pin "19") (pinfunction "GP14_19") (pintype "unspecified"))
      (node (ref "U5") (pin "2") (pinfunction "RE#_2") (pintype "unspecified"))
      (node (ref "U5") (pin "3") (pinfunction "DE_3") (pintype "unspecified"))
    )
    (net (code "25") (name "GP15") (class "Default")
      (node (ref "R154") (pin "1") (pinfunction "1_1") (pintype "input"))
      (node (ref "U11") (pin "20") (pinfunction "GP15_20") (pintype "unspecified"))
    )
    (net (code "26") (name "GP22") (class "Default")
      (node (ref "R83") (pin "1") (pinfunction "1_1") (pintype "input"))
      (node (ref "U11") (pin "29") (pinfunction "GP22_29") (pintype "unspecified"))
    )
    (net (code "27") (name "GP26") (class "Default")
      (node (ref "R59") (pin "1") (pinfunction "1_1") (pintype "input"))
      (node (ref "U11") (pin "31") (pinfunction "GP26_31") (pintype "unspecified"))
    )
    (net (code "28") (name "GP27") (class "Default")
      (node (ref "R63") (pin "1") (pinfunction "1_1") (pintype "input"))
      (node (ref "U11") (pin "32") (pinfunction "GP27_32") (pintype "unspecified"))
    )
    (net (code "29") (name "GP28") (class "Default")
      (node (ref "Q2") (pin "3") (pinfunction "C_3") (pintype "unspecified"))
      (node (ref "R7") (pin "2") (pinfunction "2_2") (pintype "input"))
      (node (ref "U11") (pin "34") (pinfunction "GP28_34") (pintype "unspecified"))
    )
    (net (code "30") (name "MA0+") (class "Default")
      (node (ref "CN18") (pin "1") (pinfunction "1_1") (pintype "unspecified"))
      (node (ref "R17") (pin "2") (pinfunction "2_2") (pintype "unspecified"))
      (node (ref "R2") (pin "1") (pinfunction "1_1") (pintype "input"))
    )
    (net (code "31") (name "MA00+") (class "Default")
      (node (ref "R123") (pin "2") (pinfunction "2_2") (pintype "input"))
      (node (ref "R17") (pin "1") (pinfunction "1_1") (pintype "unspecified"))
      (node (ref "R3") (pin "1") (pinfunction "1_1") (pintype "input"))
    )
    (net (code "32") (name "MA0-") (class "Default")
      (node (ref "C1") (pin "1") (pinfunction "1_1") (pintype "input"))
      (node (ref "C10") (pin "1") (pinfunction "1_1") (pintype "input"))
      (node (ref "C128") (pin "2") (pinfunction "2_2") (pintype "input"))
      (node (ref "C13") (pin "2") (pinfunction "2_2") (pintype "input"))
      (node (ref "C130") (pin "2") (pinfunction "2_2") (pintype "input"))
      (node (ref "C139") (pin "1") (pinfunction "1_1") (pintype "input"))
      (node (ref "C14") (pin "1") (pinfunction "1_1") (pintype "input"))
      (node (ref "C140") (pin "1") (pinfunction "1_1") (pintype "input"))
      (node (ref "C141") (pin "1") (pinfunction "1_1") (pintype "input"))
      (node (ref "C142") (pin "2") (pinfunction "2_2") (pintype "input"))
      (node (ref "C143") (pin "2") (pinfunction "2_2") (pintype "input"))
      (node (ref "C15") (pin "1") (pinfunction "1_1") (pintype "input"))
      (node (ref "C151") (pin "1") (pinfunction "1_1") (pintype "input"))
      (node (ref "C152") (pin "1") (pinfunction "1_1") (pintype "input"))
      (node (ref "C19") (pin "1") (pinfunction "1_1") (pintype "input"))
      (node (ref "C2") (pin "2") (pinfunction "2_2") (pintype "input"))
      (node (ref "C21") (pin "2") (pinfunction "2_2") (pintype "input"))
      (node (ref "C22") (pin "1") (pinfunction "1_1") (pintype "input"))
      (node (ref "C23") (pin "1") (pinfunction "1_1") (pintype "unspecified"))
      (node (ref "C24") (pin "1") (pinfunction "1_1") (pintype "input"))
      (node (ref "C25") (pin "1") (pinfunction "1_1") (pintype "input"))
      (node (ref "C26") (pin "1") (pinfunction "1_1") (pintype "input"))
      (node (ref "C27") (pin "2") (pinfunction "2_2") (pintype "input"))
      (node (ref "C28") (pin "2") (pinfunction "2_2") (pintype "input"))
      (node (ref "C29") (pin "1") (pinfunction "1_1") (pintype "input"))
      (node (ref "C30") (pin "1") (pinfunction "1_1") (pintype "input"))
      (node (ref "C31") (pin "1") (pinfunction "1_1") (pintype "input"))
      (node (ref "C32") (pin "2") (pinfunction "2_2") (pintype "input"))
      (node (ref "C33") (pin "2") (pinfunction "2_2") (pintype "input"))
      (node (ref "C34") (pin "1") (pinfunction "1_1") (pintype "input"))
      (node (ref "C35") (pin "1") (pinfunction "1_1") (pintype "unspecified"))
      (node (ref "C36") (pin "1") (pinfunction "1_1") (pintype "input"))
      (node (ref "C38") (pin "1") (pinfunction "1_1") (pintype "input"))
      (node (ref "C39") (pin "1") (pinfunction "1_1") (pintype "input"))
      (node (ref "C40") (pin "1") (pinfunction "1_1") (pintype "input"))
      (node (ref "C42") (pin "1") (pinfunction "1_1") (pintype "input"))
      (node (ref "C45") (pin "1") (pinfunction "1_1") (pintype "input"))
      (node (ref "C46") (pin "1") (pinfunction "1_1") (pintype "input"))
      (node (ref "C48") (pin "1") (pinfunction "1_1") (pintype "input"))
      (node (ref "C49") (pin "2") (pinfunction "2_2") (pintype "input"))
      (node (ref "C50") (pin "2") (pinfunction "2_2") (pintype "input"))
      (node (ref "C51") (pin "1") (pinfunction "1_1") (pintype "input"))
      (node (ref "C52") (pin "1") (pinfunction "1_1") (pintype "input"))
      (node (ref "C55") (pin "1") (pinfunction "1_1") (pintype "unspecified"))
      (node (ref "C56") (pin "1") (pinfunction "1_1") (pintype "input"))
      (node (ref "C60") (pin "1") (pinfunction "1_1") (pintype "input"))
      (node (ref "C61") (pin "1") (pinfunction "1_1") (pintype "input"))
      (node (ref "C62") (pin "1") (pinfunction "1_1") (pintype "input"))
      (node (ref "C63") (pin "1") (pinfunction "1_1") (pintype "input"))
      (node (ref "C64") (pin "1") (pinfunction "1_1") (pintype "input"))
      (node (ref "C65") (pin "1") (pinfunction "1_1") (pintype "input"))
      (node (ref "C67") (pin "1") (pinfunction "1_1") (pintype "input"))
      (node (ref "C68") (pin "2") (pinfunction "2_2") (pintype "input"))
      (node (ref "C69") (pin "1") (pinfunction "1_1") (pintype "unspecified"))
      (node (ref "C8") (pin "1") (pinfunction "1_1") (pintype "input"))
      (node (ref "C9") (pin "1") (pinfunction "1_1") (pintype "input"))
      (node (ref "CN1") (pin "4") (pinfunction "4_4") (pintype "unspecified"))
      (node (ref "CN21") (pin "1") (pinfunction "1_1") (pintype "unspecified"))
      (node (ref "CN23") (pin "1") (pinfunction "1_1") (pintype "unspecified"))
      (node (ref "CN3") (pin "2") (pinfunction "2_2") (pintype "unspecified"))
      (node (ref "CN4") (pin "2") (pinfunction "2_2") (pintype "unspecified"))
      (node (ref "CN5") (pin "2") (pinfunction "2_2") (pintype "unspecified"))
      (node (ref "D15") (pin "2") (pinfunction "A_2") (pintype "unspecified"))
      (node (ref "D17") (pin "2") (pinfunction "A_2") (pintype "unspecified"))
      (node (ref "D18") (pin "2") (pinfunction "A_2") (pintype "unspecified"))
      (node (ref "D20") (pin "2") (pinfunction "A_2") (pintype "unspecified"))
      (node (ref "D25") (pin "2") (pinfunction "A_2") (pintype "unspecified"))
      (node (ref "D26") (pin "2") (pinfunction "A_2") (pintype "unspecified"))
      (node (ref "D27") (pin "2") (pinfunction "A_2") (pintype "unspecified"))
      (node (ref "D28") (pin "2") (pinfunction "A_2") (pintype "unspecified"))
      (node (ref "D29") (pin "2") (pinfunction "A_2") (pintype "unspecified"))
      (node (ref "D30") (pin "2") (pinfunction "A_2") (pintype "unspecified"))
      (node (ref "D32") (pin "2") (pinfunction "A_2") (pintype "unspecified"))
      (node (ref "D5") (pin "2") (pinfunction "A_2") (pintype "unspecified"))
      (node (ref "D6") (pin "2") (pinfunction "A_2") (pintype "unspecified"))
      (node (ref "D7") (pin "2") (pinfunction "A_2") (pintype "unspecified"))
      (node (ref "D9") (pin "2") (pinfunction "A_2") (pintype "unspecified"))
      (node (ref "H1") (pin "2") (pinfunction "GND_2") (pintype "unspecified"))
      (node (ref "LED10") (pin "2") (pinfunction "K_2") (pintype "unspecified"))
      (node (ref "LED11") (pin "2") (pinfunction "K_2") (pintype "unspecified"))
      (node (ref "LED12") (pin "2") (pinfunction "K_2") (pintype "unspecified"))
      (node (ref "LED17") (pin "2") (pinfunction "K_2") (pintype "unspecified"))
      (node (ref "LED8") (pin "2") (pinfunction "K_2") (pintype "unspecified"))
      (node (ref "LED9") (pin "2") (pinfunction "K_2") (pintype "unspecified"))
      (node (ref "P1") (pin "GND1") (pinfunction "GND_GND1") (pintype "unspecified"))
      (node (ref "P2") (pin "GND1") (pinfunction "GND_GND1") (pintype "unspecified"))
      (node (ref "P3") (pin "GND1") (pinfunction "GND_GND1") (pintype "unspecified"))
      (node (ref "P4") (pin "GND1") (pinfunction "GND_GND1") (pintype "unspecified"))
      (node (ref "P5") (pin "GND1") (pinfunction "GND_GND1") (pintype "unspecified"))
      (node (ref "P6") (pin "GND1") (pinfunction "GND_GND1") (pintype "unspecified"))
      (node (ref "P7") (pin "GND1") (pinfunction "GND_GND1") (pintype "unspecified"))
      (node (ref "P8") (pin "GND1") (pinfunction "GND_GND1") (pintype "unspecified"))
      (node (ref "P9") (pin "GND1") (pinfunction "GND_GND1") (pintype "unspecified"))
      (node (ref "Q1") (pin "3") (pinfunction "E_3") (pintype "unspecified"))
      (node (ref "Q10") (pin "2") (pinfunction "E_2") (pintype "unspecified"))
      (node (ref "Q12") (pin "3") (pinfunction "E_3") (pintype "unspecified"))
      (node (ref "Q15") (pin "2") (pinfunction "E_2") (pintype "unspecified"))
      (node (ref "Q17") (pin "2") (pinfunction "E_2") (pintype "unspecified"))
      (node (ref "Q18") (pin "2") (pinfunction "E_2") (pintype "unspecified"))
      (node (ref "Q2") (pin "2") (pinfunction "E_2") (pintype "unspecified"))
      (node (ref "Q21") (pin "2") (pinfunction "E_2") (pintype "unspecified"))
      (node (ref "Q22") (pin "2") (pinfunction "E_2") (pintype "unspecified"))
      (node (ref "Q3") (pin "3") (pinfunction "E_3") (pintype "unspecified"))
      (node (ref "Q4") (pin "3") (pinfunction "E_3") (pintype "unspecified"))
      (node (ref "Q5") (pin "2") (pinfunction "E_2") (pintype "unspecified"))
      (node (ref "Q6") (pin "2") (pinfunction "E_2") (pintype "unspecified"))
      (node (ref "Q8") (pin "2") (pinfunction "E_2") (pintype "unspecified"))
      (node (ref "R102") (pin "2") (pinfunction "2_2") (pintype "input"))
      (node (ref "R104") (pin "1") (pinfunction "1_1") (pintype "input"))
      (node (ref "R114") (pin "1") (pinfunction "1_1") (pintype "input"))
      (node (ref "R122") (pin "1") (pinfunction "1_1") (pintype "input"))
      (node (ref "R128") (pin "1") (pinfunction "1_1") (pintype "input"))
      (node (ref "R130") (pin "2") (pinfunction "2_2") (pintype "input"))
      (node (ref "R135") (pin "1") (pinfunction "1_1") (pintype "input"))
      (node (ref "R142") (pin "1") (pinfunction "1_1") (pintype "input"))
      (node (ref "R20") (pin "1") (pinfunction "1_1") (pintype "input"))
      (node (ref "R345") (pin "2") (pinfunction "2_2") (pintype "input"))
      (node (ref "R346") (pin "2") (pinfunction "2_2") (pintype "input"))
      (node (ref "R353") (pin "1") (pinfunction "1_1") (pintype "input"))
      (node (ref "R354") (pin "1") (pinfunction "1_1") (pintype "input"))
      (node (ref "R355") (pin "1") (pinfunction "1_1") (pintype "input"))
      (node (ref "R356") (pin "1") (pinfunction "1_1") (pintype "input"))
      (node (ref "R359") (pin "2") (pinfunction "2_2") (pintype "input"))
      (node (ref "R360") (pin "2") (pinfunction "2_2") (pintype "input"))
      (node (ref "R4") (pin "2") (pinfunction "2_2") (pintype "input"))
      (node (ref "R40") (pin "1") (pinfunction "1_1") (pintype "input"))
      (node (ref "R43") (pin "1") (pinfunction "1_1") (pintype "input"))
      (node (ref "R45") (pin "1") (pinfunction "1_1") (pintype "input"))
      (node (ref "R52") (pin "1") (pinfunction "1_1") (pintype "input"))
      (node (ref "R53") (pin "1") (pinfunction "1_1") (pintype "input"))
      (node (ref "R57") (pin "1") (pinfunction "1_1") (pintype "input"))
      (node (ref "R60") (pin "1") (pinfunction "1_1") (pintype "input"))
      (node (ref "R64") (pin "1") (pinfunction "1_1") (pintype "input"))
      (node (ref "R66") (pin "1") (pinfunction "1_1") (pintype "input"))
      (node (ref "R68") (pin "1") (pinfunction "1_1") (pintype "input"))
      (node (ref "R72") (pin "1") (pinfunction "1_1") (pintype "input"))
      (node (ref "R74") (pin "1") (pinfunction "1_1") (pintype "input"))
      (node (ref "R78") (pin "1") (pinfunction "1_1") (pintype "input"))
      (node (ref "R80") (pin "1") (pinfunction "1_1") (pintype "input"))
      (node (ref "R82") (pin "1") (pinfunction "1_1") (pintype "input"))
      (node (ref "R84") (pin "1") (pinfunction "1_1") (pintype "input"))
      (node (ref "R87") (pin "1") (pinfunction "1_1") (pintype "input"))
      (node (ref "R89") (pin "2") (pinfunction "2_2") (pintype "input"))
      (node (ref "R90") (pin "2") (pinfunction "2_2") (pintype "input"))
      (node (ref "R93") (pin "1") (pinfunction "1_1") (pintype "input"))
      (node (ref "R94") (pin "1") (pinfunction "1_1") (pintype "input"))
      (node (ref "R95") (pin "1") (pinfunction "1_1") (pintype "input"))
      (node (ref "R99") (pin "2") (pinfunction "2_2") (pintype "input"))
      (node (ref "SJ12") (pin "1") (pinfunction "1_1") (pintype "unspecified"))
      (node (ref "SJ13") (pin "1") (pinfunction "1_1") (pintype "unspecified"))
      (node (ref "SJ14") (pin "1") (pinfunction "1_1") (pintype "unspecified"))
      (node (ref "SJ15") (pin "1") (pinfunction "1_1") (pintype "unspecified"))
      (node (ref "SW1") (pin "4") (pinfunction "4_4") (pintype "unspecified"))
      (node (ref "U1") (pin "3") (pinfunction "GND_3") (pintype "unspecified"))
      (node (ref "U1") (pin "5") (pinfunction "A0_5") (pintype "unspecified"))
      (node (ref "U10") (pin "4") (pinfunction "ON/OFF_4") (pintype "unspecified"))
      (node (ref "U10") (pin "5") (pinfunction "GND_5") (pintype "unspecified"))
      (node (ref "U10") (pin "6") (pinfunction "GND_6") (pintype "unspecified"))
      (node (ref "U10") (pin "7") (pinfunction "GND_7") (pintype "unspecified"))
      (node (ref "U10") (pin "8") (pinfunction "GND_8") (pintype "unspecified"))
      (node (ref "U11") (pin "13") (pinfunction "GND_13") (pintype "unspecified"))
      (node (ref "U11") (pin "18") (pinfunction "GND_18") (pintype "unspecified"))
      (node (ref "U11") (pin "23") (pinfunction "GND_23") (pintype "unspecified"))
      (node (ref "U11") (pin "28") (pinfunction "GND_28") (pintype "unspecified"))
      (node (ref "U11") (pin "3") (pinfunction "GND_3") (pintype "unspecified"))
      (node (ref "U11") (pin "33") (pinfunction "GND_33") (pintype "unspecified"))
      (node (ref "U11") (pin "38") (pinfunction "GND_38") (pintype "unspecified"))
      (node (ref "U11") (pin "8") (pinfunction "GND_8") (pintype "unspecified"))
      (node (ref "U13") (pin "4") (pinfunction "-VSS_4") (pintype "unspecified"))
      (node (ref "U14") (pin "4") (pinfunction "-VSS_4") (pintype "unspecified"))
      (node (ref "U15") (pin "4") (pinfunction "GND_4") (pintype "unspecified"))
      (node (ref "U16") (pin "4") (pinfunction "-VSS_4") (pintype "unspecified"))
      (node (ref "U17") (pin "4") (pinfunction "-VSS_4") (pintype "unspecified"))
      (node (ref "U18") (pin "4") (pinfunction "GND_4") (pintype "unspecified"))
      (node (ref "U2") (pin "3") (pinfunction "GND_3") (pintype "unspecified"))
      (node (ref "U3") (pin "3") (pinfunction "3_3") (pintype "unspecified"))
      (node (ref "U4") (pin "3") (pinfunction "3_3") (pintype "unspecified"))
      (node (ref "U5") (pin "5") (pinfunction "GND_5") (pintype "unspecified"))
      (node (ref "U51") (pin "1") (pinfunction "GND_1") (pintype "unspecified"))
      (node (ref "U58") (pin "1") (pinfunction "GND_1") (pintype "unspecified"))
      (node (ref "U59") (pin "1") (pinfunction "GND_1") (pintype "unspecified"))
      (node (ref "U6") (pin "1") (pinfunction "CLKIN_1") (pintype "unspecified"))
      (node (ref "U6") (pin "11") (pinfunction "FSYNC_11") (pintype "unspecified"))
      (node (ref "U6") (pin "18") (pinfunction "GND_18") (pintype "unspecified"))
      (node (ref "U6") (pin "25") (pinfunction "GND_25") (pintype "unspecified"))
      (node (ref "U6") (pin "9") (pinfunction "AD0_9") (pintype "unspecified"))
      (node (ref "U7") (pin "1") (pinfunction "A0_1") (pintype "unspecified"))
      (node (ref "U7") (pin "2") (pinfunction "A1_2") (pintype "unspecified"))
      (node (ref "U7") (pin "3") (pinfunction "A2_3") (pintype "unspecified"))
      (node (ref "U7") (pin "4") (pinfunction "VSS_4") (pintype "unspecified"))
      (node (ref "U9") (pin "3") (pinfunction "Gnd_3") (pintype "unspecified"))
      (node (ref "U9") (pin "5") (pinfunction "ON#/OFF_5") (pintype "unspecified"))
      (node (ref "U9") (pin "6") (pinfunction "TAB_6") (pintype "unspecified"))
    )
    (net (code "33") (name "MA1+") (class "Default")
      (node (ref "CN18") (pin "2") (pinfunction "2_2") (pintype "unspecified"))
      (node (ref "R16") (pin "1") (pinfunction "1_1") (pintype "unspecified"))
      (node (ref "R9") (pin "1") (pinfunction "1_1") (pintype "input"))
    )
    (net (code "34") (name "MA01+") (class "Default")
      (node (ref "R112") (pin "2") (pinfunction "2_2") (pintype "input"))
      (node (ref "R16") (pin "2") (pinfunction "2_2") (pintype "unspecified"))
      (node (ref "R8") (pin "1") (pinfunction "1_1") (pintype "input"))
    )
    (net (code "35") (name "Net-(C12-Pad2)") (class "Default")
      (node (ref "C12") (pin "2") (pinfunction "2_2") (pintype "input"))
      (node (ref "R110") (pin "2") (pinfunction "2_2") (pintype "input"))
    )
    (net (code "36") (name "Net-(C18-Pad2)") (class "Default")
      (node (ref "C18") (pin "2") (pinfunction "2_2") (pintype "input"))
      (node (ref "R15") (pin "1") (pinfunction "1_1") (pintype "input"))
    )
    (net (code "37") (name "Net-(C34-Pad2)") (class "Default")
      (node (ref "C34") (pin "2") (pinfunction "2_2") (pintype "input"))
      (node (ref "R111") (pin "2") (pinfunction "2_2") (pintype "input"))
    )
    (net (code "38") (name "Net-(C37-Pad2)") (class "Default")
      (node (ref "C37") (pin "2") (pinfunction "2_2") (pintype "input"))
      (node (ref "R10") (pin "1") (pinfunction "1_1") (pintype "input"))
    )
    (net (code "39") (name "Net-(C43-Pad2)") (class "Default")
      (node (ref "C43") (pin "2") (pinfunction "2_2") (pintype "input"))
      (node (ref "R50") (pin "1") (pinfunction "1_1") (pintype "input"))
    )
    (net (code "40") (name "Net-(C47-Pad2)") (class "Default")
      (node (ref "C47") (pin "2") (pinfunction "2_2") (pintype "input"))
      (node (ref "R55") (pin "1") (pinfunction "1_1") (pintype "input"))
    )
    (net (code "41") (name "Net-(C56-Pad2)") (class "Default")
      (node (ref "C56") (pin "2") (pinfunction "2_2") (pintype "input"))
      (node (ref "R117") (pin "2") (pinfunction "2_2") (pintype "input"))
    )
    (net (code "42") (name "Net-(C57-Pad2)") (class "Default")
      (node (ref "C57") (pin "2") (pinfunction "2_2") (pintype "input"))
      (node (ref "R118") (pin "2") (pinfunction "2_2") (pintype "input"))
    )
    (net (code "43") (name "Net-(CN3-Pad1)") (class "Default")
      (node (ref "CN3") (pin "1") (pinfunction "1_1") (pintype "unspecified"))
      (node (ref "R12") (pin "2") (pinfunction "2_2") (pintype "input"))
    )
    (net (code "44") (name "Net-(CN4-Pad1)") (class "Default")
      (node (ref "CN4") (pin "1") (pinfunction "1_1") (pintype "unspecified"))
      (node (ref "R44") (pin "2") (pinfunction "2_2") (pintype "input"))
    )
    (net (code "45") (name "Net-(CN5-Pad1)") (class "Default")
      (node (ref "CN5") (pin "1") (pinfunction "1_1") (pintype "unspecified"))
      (node (ref "R81") (pin "2") (pinfunction "2_2") (pintype "input"))
    )
    (net (code "46") (name "Net-(CN6-Pad1)") (class "Default")
      (node (ref "CN6") (pin "1") (pinfunction "1_1") (pintype "unspecified"))
      (node (ref "R62") (pin "1") (pinfunction "1_1") (pintype "input"))
    )
    (net (code "47") (name "Net-(CN7-Pad1)") (class "Default")
      (node (ref "CN7") (pin "1") (pinfunction "1_1") (pintype "unspecified"))
      (node (ref "R56") (pin "1") (pinfunction "1_1") (pintype "input"))
    )
    (net (code "48") (name "Net-(CN12-Pad1)") (class "Default")
      (node (ref "CN12") (pin "1") (pinfunction "1_1") (pintype "unspecified"))
      (node (ref "R6") (pin "1") (pinfunction "1_1") (pintype "input"))
    )
    (net (code "49") (name "Net-(D1-A)") (class "Default")
      (node (ref "D1") (pin "2") (pinfunction "A_2") (pintype "unspecified"))
      (node (ref "U13") (pin "7") (pinfunction "OUTB_7") (pintype "unspecified"))
    )
    (net (code "50") (name "Net-(D1-C)") (class "Default")
      (node (ref "D1") (pin "1") (pinfunction "C_1") (pintype "unspecified"))
      (node (ref "D2") (pin "2") (pinfunction "A_2") (pintype "unspecified"))
      (node (ref "R96") (pin "1") (pinfunction "1_1") (pintype "input"))
    )
    (net (code "51") (name "Net-(D2-C)") (class "Default")
      (node (ref "D2") (pin "1") (pinfunction "C_1") (pintype "unspecified"))
      (node (ref "R113") (pin "1") (pinfunction "1_1") (pintype "input"))
      (node (ref "U13") (pin "6") (pinfunction "-INB_6") (pintype "unspecified"))
    )
    (net (code "52") (name "Net-(D3-A)") (class "Default")
      (node (ref "D3") (pin "2") (pinfunction "A_2") (pintype "unspecified"))
      (node (ref "D4") (pin "1") (pinfunction "C_1") (pintype "unspecified"))
      (node (ref "R121") (pin "1") (pinfunction "1_1") (pintype "input"))
    )
    (net (code "53") (name "Net-(D3-C)") (class "Default")
      (node (ref "D3") (pin "1") (pinfunction "C_1") (pintype "unspecified"))
      (node (ref "R116") (pin "1") (pinfunction "1_1") (pintype "input"))
      (node (ref "U17") (pin "6") (pinfunction "-INB_6") (pintype "unspecified"))
    )
    (net (code "54") (name "Net-(D4-A)") (class "Default")
      (node (ref "D4") (pin "2") (pinfunction "A_2") (pintype "unspecified"))
      (node (ref "U17") (pin "7") (pinfunction "OUTB_7") (pintype "unspecified"))
    )
    (net (code "55") (name "Net-(D5-C)") (class "Default")
      (node (ref "C61") (pin "2") (pinfunction "2_2") (pintype "input"))
      (node (ref "D5") (pin "1") (pinfunction "C_1") (pintype "unspecified"))
      (node (ref "R77") (pin "1") (pinfunction "1_1") (pintype "input"))
      (node (ref "R79") (pin "1") (pinfunction "1_1") (pintype "input"))
      (node (ref "R82") (pin "2") (pinfunction "2_2") (pintype "input"))
    )
    (net (code "56") (name "Net-(D6-C)") (class "Default")
      (node (ref "C62") (pin "2") (pinfunction "2_2") (pintype "input"))
      (node (ref "D6") (pin "1") (pinfunction "C_1") (pintype "unspecified"))
      (node (ref "R134") (pin "1") (pinfunction "1_1") (pintype "input"))
      (node (ref "R78") (pin "2") (pinfunction "2_2") (pintype "input"))
      (node (ref "R86") (pin "1") (pinfunction "1_1") (pintype "input"))
    )
    (net (code "57") (name "Net-(D7-C)") (class "Default")
      (node (ref "D7") (pin "1") (pinfunction "C_1") (pintype "unspecified"))
      (node (ref "Q4") (pin "1") (pinfunction "B_1") (pintype "unspecified"))
      (node (ref "R37") (pin "2") (pinfunction "2_2") (pintype "unspecified"))
      (node (ref "R52") (pin "2") (pinfunction "2_2") (pintype "input"))
    )
    (net (code "58") (name "Net-(D10-A)") (class "Default")
      (node (ref "C65") (pin "2") (pinfunction "2_2") (pintype "input"))
      (node (ref "D10") (pin "2") (pinfunction "A_2") (pintype "unspecified"))
      (node (ref "D9") (pin "1") (pinfunction "C_1") (pintype "unspecified"))
      (node (ref "Q11") (pin "3") (pinfunction "D_3") (pintype "unspecified"))
      (node (ref "R114") (pin "2") (pinfunction "2_2") (pintype "input"))
      (node (ref "R151") (pin "1") (pinfunction "1_1") (pintype "input"))
    )
    (net (code "59") (name "Net-(D15-C)") (class "Default")
      (node (ref "D15") (pin "1") (pinfunction "C_1") (pintype "unspecified"))
      (node (ref "Q12") (pin "1") (pinfunction "B_1") (pintype "unspecified"))
      (node (ref "R20") (pin "2") (pinfunction "2_2") (pintype "input"))
      (node (ref "R54") (pin "2") (pinfunction "2_2") (pintype "unspecified"))
    )
    (net (code "60") (name "Net-(D20-C)") (class "Default")
      (node (ref "D20") (pin "1") (pinfunction "C_1") (pintype "unspecified"))
      (node (ref "Q1") (pin "1") (pinfunction "B_1") (pintype "unspecified"))
      (node (ref "R49") (pin "2") (pinfunction "2_2") (pintype "unspecified"))
      (node (ref "R66") (pin "2") (pinfunction "2_2") (pintype "input"))
    )
    (net (code "61") (name "Net-(D23-K)") (class "Default")
      (node (ref "C31") (pin "2") (pinfunction "2_2") (pintype "input"))
      (node (ref "D23") (pin "1") (pinfunction "K_1") (pintype "unspecified"))
      (node (ref "U11") (pin "39") (pinfunction "VSYS_39") (pintype "unspecified"))
    )
    (net (code "62") (name "Net-(D25-C)") (class "Default")
      (node (ref "D25") (pin "1") (pinfunction "C_1") (pintype "unspecified"))
      (node (ref "L2") (pin "1") (pinfunction "1_1") (pintype "unspecified"))
      (node (ref "U10") (pin "2") (pinfunction "OUTPUT_2") (pintype "unspecified"))
    )
    (net (code "63") (name "Net-(D28-C)") (class "Default")
      (node (ref "D28") (pin "1") (pinfunction "C_1") (pintype "unspecified"))
      (node (ref "Q3") (pin "1") (pinfunction "B_1") (pintype "unspecified"))
      (node (ref "R51") (pin "2") (pinfunction "2_2") (pintype "unspecified"))
      (node (ref "R53") (pin "2") (pinfunction "2_2") (pintype "input"))
    )
    (net (code "64") (name "Net-(LED1-A)") (class "Default")
      (node (ref "LED1") (pin "1") (pinfunction "A_1") (pintype "unspecified"))
      (node (ref "R47") (pin "2") (pinfunction "2_2") (pintype "input"))
    )
    (net (code "65") (name "Net-(LED1-K)") (class "Default")
      (node (ref "CN7") (pin "2") (pinfunction "2_2") (pintype "unspecified"))
      (node (ref "LED1") (pin "2") (pinfunction "K_2") (pintype "unspecified"))
      (node (ref "Q15") (pin "3") (pinfunction "C_3") (pintype "unspecified"))
    )
    (net (code "66") (name "Net-(LED2-A)") (class "Default")
      (node (ref "LED2") (pin "1") (pinfunction "A_1") (pintype "unspecified"))
      (node (ref "R48") (pin "2") (pinfunction "2_2") (pintype "input"))
    )
    (net (code "67") (name "Net-(LED3-A)") (class "Default")
      (node (ref "LED3") (pin "1") (pinfunction "A_1") (pintype "unspecified"))
      (node (ref "R46") (pin "2") (pinfunction "2_2") (pintype "input"))
    )
    (net (code "68") (name "Net-(LED3-K)") (class "Default")
      (node (ref "CN12") (pin "2") (pinfunction "2_2") (pintype "unspecified"))
      (node (ref "LED3") (pin "2") (pinfunction "K_2") (pintype "unspecified"))
      (node (ref "Q22") (pin "3") (pinfunction "C_3") (pintype "unspecified"))
    )
    (net (code "69") (name "Net-(LED4-A)") (class "Default")
      (node (ref "LED4") (pin "1") (pinfunction "A_1") (pintype "unspecified"))
      (node (ref "R61") (pin "2") (pinfunction "2_2") (pintype "input"))
    )
    (net (code "70") (name "Net-(LED4-K)") (class "Default")
      (node (ref "CN6") (pin "2") (pinfunction "2_2") (pintype "unspecified"))
      (node (ref "LED4") (pin "2") (pinfunction "K_2") (pintype "unspecified"))
      (node (ref "Q17") (pin "3") (pinfunction "C_3") (pintype "unspecified"))
    )
    (net (code "71") (name "Net-(LED5-A)") (class "Default")
      (node (ref "LED5") (pin "1") (pinfunction "A_1") (pintype "unspecified"))
      (node (ref "R65") (pin "2") (pinfunction "2_2") (pintype "input"))
    )
    (net (code "72") (name "Net-(LED6-A)") (class "Default")
      (node (ref "LED6") (pin "1") (pinfunction "A_1") (pintype "unspecified"))
      (node (ref "R1") (pin "2") (pinfunction "2_2") (pintype "input"))
    )
    (net (code "73") (name "Net-(LED7-A)") (class "Default")
      (node (ref "LED7") (pin "1") (pinfunction "A_1") (pintype "unspecified"))
      (node (ref "R85") (pin "1") (pinfunction "1_1") (pintype "input"))
    )
    (net (code "74") (name "Net-(LED7-K)") (class "Default")
      (node (ref "LED7") (pin "2") (pinfunction "K_2") (pintype "unspecified"))
      (node (ref "Q6") (pin "3") (pinfunction "C_3") (pintype "unspecified"))
    )
    (net (code "75") (name "Net-(LED8-A)") (class "Default")
      (node (ref "LED8") (pin "1") (pinfunction "A_1") (pintype "unspecified"))
      (node (ref "R296") (pin "1") (pinfunction "1_1") (pintype "input"))
    )
    (net (code "76") (name "Net-(LED9-A)") (class "Default")
      (node (ref "LED9") (pin "1") (pinfunction "A_1") (pintype "unspecified"))
      (node (ref "R75") (pin "1") (pinfunction "1_1") (pintype "input"))
    )
    (net (code "77") (name "Net-(LED10-A)") (class "Default")
      (node (ref "LED10") (pin "1") (pinfunction "A_1") (pintype "unspecified"))
      (node (ref "R298") (pin "1") (pinfunction "1_1") (pintype "input"))
    )
    (net (code "78") (name "Net-(LED11-A)") (class "Default")
      (node (ref "LED11") (pin "1") (pinfunction "A_1") (pintype "unspecified"))
      (node (ref "R76") (pin "1") (pinfunction "1_1") (pintype "input"))
    )
    (net (code "79") (name "Net-(LED12-A)") (class "Default")
      (node (ref "LED12") (pin "1") (pinfunction "A_1") (pintype "unspecified"))
      (node (ref "R362") (pin "1") (pinfunction "1_1") (pintype "input"))
    )
    (net (code "80") (name "Net-(LED13-A)") (class "Default")
      (node (ref "LED13") (pin "1") (pinfunction "A_1") (pintype "unspecified"))
      (node (ref "R67") (pin "2") (pinfunction "2_2") (pintype "input"))
    )
    (net (code "81") (name "Net-(LED15-A)") (class "Default")
      (node (ref "LED15") (pin "1") (pinfunction "A_1") (pintype "unspecified"))
      (node (ref "R30") (pin "2") (pinfunction "2_2") (pintype "input"))
    )
    (net (code "82") (name "Net-(LED15-K)") (class "Default")
      (node (ref "LED15") (pin "2") (pinfunction "K_2") (pintype "unspecified"))
      (node (ref "Q8") (pin "3") (pinfunction "C_3") (pintype "unspecified"))
    )
    (net (code "83") (name "Net-(LED17-A)") (class "Default")
      (node (ref "LED17") (pin "1") (pinfunction "A_1") (pintype "unspecified"))
      (node (ref "R151") (pin "2") (pinfunction "2_2") (pintype "input"))
    )
    (net (code "84") (name "Net-(Q2-B)") (class "Default")
      (node (ref "Q2") (pin "1") (pinfunction "B_1") (pintype "unspecified"))
      (node (ref "R4") (pin "1") (pinfunction "1_1") (pintype "input"))
      (node (ref "R5") (pin "2") (pinfunction "2_2") (pintype "input"))
    )
    (net (code "85") (name "Net-(Q5-C)") (class "Default")
      (node (ref "Q5") (pin "3") (pinfunction "C_3") (pintype "unspecified"))
      (node (ref "Q9") (pin "1") (pinfunction "G_1") (pintype "unspecified"))
      (node (ref "R58") (pin "1") (pinfunction "1_1") (pintype "input"))
    )
    (net (code "86") (name "Net-(Q6-B)") (class "Default")
      (node (ref "Q6") (pin "1") (pinfunction "B_1") (pintype "unspecified"))
      (node (ref "R25") (pin "2") (pinfunction "2_2") (pintype "input"))
    )
    (net (code "87") (name "Net-(Q8-B)") (class "Default")
      (node (ref "Q8") (pin "1") (pinfunction "B_1") (pintype "unspecified"))
      (node (ref "R92") (pin "2") (pinfunction "2_2") (pintype "input"))
    )
    (net (code "88") (name "Net-(Q9-D)") (class "Default")
      (node (ref "C129") (pin "2") (pinfunction "2_2") (pintype "input"))
      (node (ref "C51") (pin "2") (pinfunction "2_2") (pintype "input"))
      (node (ref "Q9") (pin "3") (pinfunction "D_3") (pintype "unspecified"))
      (node (ref "R5") (pin "1") (pinfunction "1_1") (pintype "input"))
      (node (ref "R57") (pin "2") (pinfunction "2_2") (pintype "input"))
      (node (ref "U51") (pin "4") (pinfunction "RST_4") (pintype "unspecified"))
      (node (ref "U51") (pin "8") (pinfunction "VCC_8") (pintype "unspecified"))
    )
    (net (code "89") (name "Net-(Q10-B)") (class "Default")
      (node (ref "Q10") (pin "1") (pinfunction "B_1") (pintype "unspecified"))
      (node (ref "R154") (pin "2") (pinfunction "2_2") (pintype "input"))
      (node (ref "R99") (pin "1") (pinfunction "1_1") (pintype "input"))
    )
    (net (code "90") (name "Net-(Q10-C)") (class "Default")
      (node (ref "Q10") (pin "3") (pinfunction "C_3") (pintype "unspecified"))
      (node (ref "Q11") (pin "1") (pinfunction "G_1") (pintype "unspecified"))
      (node (ref "R153") (pin "2") (pinfunction "2_2") (pintype "input"))
    )
    (net (code "91") (name "Net-(Q13-B)") (class "Default")
      (node (ref "Q13") (pin "1") (pinfunction "B_1") (pintype "unspecified"))
      (node (ref "R337") (pin "2") (pinfunction "2_2") (pintype "input"))
    )
    (net (code "92") (name "Net-(Q14-B)") (class "Default")
      (node (ref "Q14") (pin "1") (pinfunction "B_1") (pintype "unspecified"))
      (node (ref "R338") (pin "2") (pinfunction "2_2") (pintype "input"))
    )
    (net (code "93") (name "Net-(Q15-B)") (class "Default")
      (node (ref "Q15") (pin "1") (pinfunction "B_1") (pintype "unspecified"))
      (node (ref "R59") (pin "2") (pinfunction "2_2") (pintype "input"))
      (node (ref "R60") (pin "2") (pinfunction "2_2") (pintype "input"))
    )
    (net (code "94") (name "Net-(Q17-B)") (class "Default")
      (node (ref "Q17") (pin "1") (pinfunction "B_1") (pintype "unspecified"))
      (node (ref "R63") (pin "2") (pinfunction "2_2") (pintype "input"))
      (node (ref "R64") (pin "2") (pinfunction "2_2") (pintype "input"))
    )
    (net (code "95") (name "Net-(Q18-B)") (class "Default")
      (node (ref "Q18") (pin "1") (pinfunction "B_1") (pintype "unspecified"))
      (node (ref "R70") (pin "2") (pinfunction "2_2") (pintype "input"))
      (node (ref "R89") (pin "1") (pinfunction "1_1") (pintype "input"))
    )
    (net (code "96") (name "Net-(Q18-C)") (class "Default")
      (node (ref "Q18") (pin "3") (pinfunction "C_3") (pintype "unspecified"))
      (node (ref "R69") (pin "1") (pinfunction "1_1") (pintype "input"))
      (node (ref "SJ2") (pin "2") (pinfunction "2_2") (pintype "unspecified"))
    )
    (net (code "97") (name "Net-(Q19-D)") (class "Default")
      (node (ref "Q19") (pin "3") (pinfunction "D_3") (pintype "unspecified"))
      (node (ref "R25") (pin "1") (pinfunction "1_1") (pintype "input"))
      (node (ref "R80") (pin "2") (pinfunction "2_2") (pintype "input"))
    )
    (net (code "98") (name "Net-(Q19-G)") (class "Default")
      (node (ref "Q19") (pin "1") (pinfunction "G_1") (pintype "unspecified"))
      (node (ref "R79") (pin "2") (pinfunction "2_2") (pintype "input"))
    )
    (net (code "99") (name "Net-(Q20-D)") (class "Default")
      (node (ref "Q20") (pin "3") (pinfunction "D_3") (pintype "unspecified"))
      (node (ref "R135") (pin "2") (pinfunction "2_2") (pintype "input"))
      (node (ref "R92") (pin "1") (pinfunction "1_1") (pintype "input"))
    )
    (net (code "100") (name "Net-(Q20-G)") (class "Default")
      (node (ref "Q20") (pin "1") (pinfunction "G_1") (pintype "unspecified"))
      (node (ref "R86") (pin "2") (pinfunction "2_2") (pintype "input"))
    )
    (net (code "101") (name "Net-(Q21-B)") (class "Default")
      (node (ref "Q21") (pin "1") (pinfunction "B_1") (pintype "unspecified"))
      (node (ref "R145") (pin "2") (pinfunction "2_2") (pintype "input"))
      (node (ref "R45") (pin "2") (pinfunction "2_2") (pintype "input"))
    )
    (net (code "102") (name "Net-(Q21-C)") (class "Default")
      (node (ref "Q21") (pin "3") (pinfunction "C_3") (pintype "unspecified"))
      (node (ref "R115") (pin "1") (pinfunction "1_1") (pintype "input"))
      (node (ref "SJ17") (pin "2") (pinfunction "2_2") (pintype "unspecified"))
    )
    (net (code "103") (name "Net-(Q22-B)") (class "Default")
      (node (ref "Q22") (pin "1") (pinfunction "B_1") (pintype "unspecified"))
      (node (ref "R83") (pin "2") (pinfunction "2_2") (pintype "input"))
      (node (ref "R84") (pin "2") (pinfunction "2_2") (pintype "input"))
    )
    (net (code "104") (name "Net-(R11-Pad2)") (class "Default")
      (node (ref "R11") (pin "2") (pinfunction "2_2") (pintype "input"))
      (node (ref "R115") (pin "2") (pinfunction "2_2") (pintype "input"))
      (node (ref "R74") (pin "2") (pinfunction "2_2") (pintype "input"))
    )
    (net (code "105") (name "Net-(R34-Pad2)") (class "Default")
      (node (ref "R34") (pin "2") (pinfunction "2_2") (pintype "input"))
      (node (ref "R41") (pin "1") (pinfunction "1_1") (pintype "input"))
    )
    (net (code "106") (name "Net-(R39-Pad1)") (class "Default")
      (node (ref "R39") (pin "1") (pinfunction "1_1") (pintype "input"))
      (node (ref "R40") (pin "2") (pinfunction "2_2") (pintype "input"))
    )
    (net (code "107") (name "Net-(R42-Pad1)") (class "Default")
      (node (ref "R42") (pin "1") (pinfunction "1_1") (pintype "input"))
      (node (ref "SJ1") (pin "2") (pinfunction "2_2") (pintype "unspecified"))
    )
    (net (code "108") (name "Net-(R69-Pad2)") (class "Default")
      (node (ref "R69") (pin "2") (pinfunction "2_2") (pintype "input"))
      (node (ref "R90") (pin "1") (pinfunction "1_1") (pintype "input"))
      (node (ref "R91") (pin "2") (pinfunction "2_2") (pintype "input"))
    )
    (net (code "109") (name "Net-(R71-Pad2)") (class "Default")
      (node (ref "R71") (pin "2") (pinfunction "2_2") (pintype "input"))
      (node (ref "R72") (pin "2") (pinfunction "2_2") (pintype "input"))
      (node (ref "SJ6") (pin "1") (pinfunction "1_1") (pintype "unspecified"))
    )
    (net (code "110") (name "Net-(R73-Pad1)") (class "Default")
      (node (ref "R73") (pin "1") (pinfunction "1_1") (pintype "input"))
      (node (ref "SJ4") (pin "1") (pinfunction "1_1") (pintype "unspecified"))
    )
    (net (code "111") (name "Net-(R77-Pad2)") (class "Default")
      (node (ref "R77") (pin "2") (pinfunction "2_2") (pintype "input"))
      (node (ref "SJ2") (pin "1") (pinfunction "1_1") (pintype "unspecified"))
      (node (ref "SJ4") (pin "2") (pinfunction "2_2") (pintype "unspecified"))
      (node (ref "SJ5") (pin "2") (pinfunction "2_2") (pintype "unspecified"))
    )
    (net (code "112") (name "Net-(R87-Pad2)") (class "Default")
      (node (ref "R87") (pin "2") (pinfunction "2_2") (pintype "input"))
      (node (ref "R88") (pin "1") (pinfunction "1_1") (pintype "input"))
      (node (ref "SJ5") (pin "1") (pinfunction "1_1") (pintype "unspecified"))
    )
    (net (code "113") (name "Net-(R105-Pad1)") (class "Default")
      (node (ref "R105") (pin "1") (pinfunction "1_1") (pintype "input"))
      (node (ref "R107") (pin "2") (pinfunction "2_2") (pintype "input"))
      (node (ref "R112") (pin "1") (pinfunction "1_1") (pintype "input"))
    )
    (net (code "114") (name "Net-(R123-Pad1)") (class "Default")
      (node (ref "R123") (pin "1") (pinfunction "1_1") (pintype "input"))
      (node (ref "R125") (pin "2") (pinfunction "2_2") (pintype "input"))
      (node (ref "R127") (pin "1") (pinfunction "1_1") (pintype "input"))
    )
    (net (code "115") (name "Net-(R133-Pad2)") (class "Default")
      (node (ref "R133") (pin "2") (pinfunction "2_2") (pintype "input"))
      (node (ref "SJ3") (pin "1") (pinfunction "1_1") (pintype "unspecified"))
    )
    (net (code "116") (name "Net-(R134-Pad2)") (class "Default")
      (node (ref "R134") (pin "2") (pinfunction "2_2") (pintype "input"))
      (node (ref "SJ17") (pin "1") (pinfunction "1_1") (pintype "unspecified"))
      (node (ref "SJ3") (pin "2") (pinfunction "2_2") (pintype "unspecified"))
      (node (ref "SJ6") (pin "2") (pinfunction "2_2") (pintype "unspecified"))
    )
    (net (code "117") (name "Net-(U1-IN+1)") (class "Default")
      (node (ref "C16") (pin "2") (pinfunction "2_2") (pintype "input"))
      (node (ref "R2") (pin "2") (pinfunction "2_2") (pintype "input"))
      (node (ref "U1") (pin "12") (pinfunction "IN+1_12") (pintype "unspecified"))
    )
    (net (code "118") (name "Net-(U1-IN+2)") (class "Default")
      (node (ref "C4") (pin "2") (pinfunction "2_2") (pintype "input"))
      (node (ref "R9") (pin "2") (pinfunction "2_2") (pintype "input"))
      (node (ref "U1") (pin "15") (pinfunction "IN+2_15") (pintype "unspecified"))
    )
    (net (code "119") (name "Net-(U1-IN+3)") (class "Default")
      (node (ref "C5") (pin "2") (pinfunction "2_2") (pintype "input"))
      (node (ref "R14") (pin "2") (pinfunction "2_2") (pintype "input"))
      (node (ref "U1") (pin "2") (pinfunction "IN+3_2") (pintype "unspecified"))
    )
    (net (code "120") (name "Net-(U1-IN-1)") (class "Default")
      (node (ref "C16") (pin "1") (pinfunction "1_1") (pintype "input"))
      (node (ref "R3") (pin "2") (pinfunction "2_2") (pintype "input"))
      (node (ref "U1") (pin "11") (pinfunction "IN-1_11") (pintype "unspecified"))
    )
    (net (code "121") (name "Net-(U1-IN-2)") (class "Default")
      (node (ref "C4") (pin "1") (pinfunction "1_1") (pintype "input"))
      (node (ref "R8") (pin "2") (pinfunction "2_2") (pintype "input"))
      (node (ref "U1") (pin "14") (pinfunction "IN-2_14") (pintype "unspecified"))
    )
    (net (code "122") (name "Net-(U1-IN-3)") (class "Default")
      (node (ref "C5") (pin "1") (pinfunction "1_1") (pintype "input"))
      (node (ref "R13") (pin "2") (pinfunction "2_2") (pintype "input"))
      (node (ref "U1") (pin "1") (pinfunction "IN-3_1") (pintype "unspecified"))
    )
    (net (code "123") (name "Net-(U2-IN+1)") (class "Default")
      (node (ref "C6") (pin "2") (pinfunction "2_2") (pintype "input"))
      (node (ref "R24") (pin "2") (pinfunction "2_2") (pintype "input"))
      (node (ref "U2") (pin "12") (pinfunction "IN+1_12") (pintype "unspecified"))
    )
    (net (code "124") (name "Net-(U2-IN+2)") (class "Default")
      (node (ref "C7") (pin "2") (pinfunction "2_2") (pintype "input"))
      (node (ref "R19") (pin "2") (pinfunction "2_2") (pintype "input"))
      (node (ref "U2") (pin "15") (pinfunction "IN+2_15") (pintype "unspecified"))
    )
    (net (code "125") (name "Net-(U2-IN+3)") (class "Default")
      (node (ref "C11") (pin "2") (pinfunction "2_2") (pintype "input"))
      (node (ref "R29") (pin "2") (pinfunction "2_2") (pintype "input"))
      (node (ref "U2") (pin "2") (pinfunction "IN+3_2") (pintype "unspecified"))
    )
    (net (code "126") (name "Net-(U2-IN-1)") (class "Default")
      (node (ref "C6") (pin "1") (pinfunction "1_1") (pintype "input"))
      (node (ref "R23") (pin "2") (pinfunction "2_2") (pintype "input"))
      (node (ref "U2") (pin "11") (pinfunction "IN-1_11") (pintype "unspecified"))
    )
    (net (code "127") (name "Net-(U2-IN-2)") (class "Default")
      (node (ref "C7") (pin "1") (pinfunction "1_1") (pintype "input"))
      (node (ref "R18") (pin "2") (pinfunction "2_2") (pintype "input"))
      (node (ref "U2") (pin "14") (pinfunction "IN-2_14") (pintype "unspecified"))
    )
    (net (code "128") (name "Net-(U2-IN-3)") (class "Default")
      (node (ref "C11") (pin "1") (pinfunction "1_1") (pintype "input"))
      (node (ref "R28") (pin "2") (pinfunction "2_2") (pintype "input"))
      (node (ref "U2") (pin "1") (pinfunction "IN-3_1") (pintype "unspecified"))
    )
    (net (code "129") (name "Net-(U6-CPOUT)") (class "Default")
      (node (ref "C2") (pin "1") (pinfunction "1_1") (pintype "input"))
      (node (ref "U6") (pin "20") (pinfunction "CPOUT_20") (pintype "unspecified"))
    )
    (net (code "130") (name "Net-(U6-REGOUT)") (class "Default")
      (node (ref "C10") (pin "2") (pinfunction "2_2") (pintype "input"))
      (node (ref "U6") (pin "10") (pinfunction "REGOUT_10") (pintype "unspecified"))
    )
    (net (code "131") (name "Net-(U6-VLOGIC)") (class "Default")
      (node (ref "C26") (pin "2") (pinfunction "2_2") (pintype "input"))
      (node (ref "U6") (pin "8") (pinfunction "VLOGIC_8") (pintype "unspecified"))
    )
    (net (code "132") (name "Net-(U7-WP)") (class "Default")
      (node (ref "R33") (pin "1") (pinfunction "1_1") (pintype "input"))
      (node (ref "U7") (pin "7") (pinfunction "WP_7") (pintype "unspecified"))
    )
    (net (code "133") (name "Net-(U13-+INA)") (class "Default")
      (node (ref "R110") (pin "1") (pinfunction "1_1") (pintype "input"))
      (node (ref "R93") (pin "2") (pinfunction "2_2") (pintype "input"))
      (node (ref "U13") (pin "3") (pinfunction "+INA_3") (pintype "unspecified"))
    )
    (net (code "134") (name "Net-(U13-+INB)") (class "Default")
      (node (ref "R109") (pin "2") (pinfunction "2_2") (pintype "input"))
      (node (ref "U13") (pin "1") (pinfunction "OUTA_1") (pintype "unspecified"))
      (node (ref "U13") (pin "5") (pinfunction "+INB_5") (pintype "unspecified"))
    )
    (net (code "135") (name "Net-(U13--INA)") (class "Default")
      (node (ref "R109") (pin "1") (pinfunction "1_1") (pintype "input"))
      (node (ref "R111") (pin "1") (pinfunction "1_1") (pintype "input"))
      (node (ref "U13") (pin "2") (pinfunction "-INA_2") (pintype "unspecified"))
    )
    (net (code "136") (name "Net-(U14-+INB)") (class "Default")
      (node (ref "R97") (pin "2") (pinfunction "2_2") (pintype "input"))
      (node (ref "U14") (pin "5") (pinfunction "+INB_5") (pintype "unspecified"))
    )
    (net (code "137") (name "Net-(U14--INA)") (class "Default")
      (node (ref "R96") (pin "2") (pinfunction "2_2") (pintype "input"))
      (node (ref "R97") (pin "1") (pinfunction "1_1") (pintype "input"))
      (node (ref "U14") (pin "1") (pinfunction "OUTA_1") (pintype "unspecified"))
      (node (ref "U14") (pin "2") (pinfunction "-INA_2") (pintype "unspecified"))
    )
    (net (code "138") (name "Net-(U14--INB)") (class "Default")
      (node (ref "R100") (pin "1") (pinfunction "1_1") (pintype "input"))
      (node (ref "U14") (pin "6") (pinfunction "-INB_6") (pintype "unspecified"))
      (node (ref "U14") (pin "7") (pinfunction "OUTB_7") (pintype "unspecified"))
    )
    (net (code "139") (name "Net-(U15-1IN+)") (class "Default")
      (node (ref "C52") (pin "2") (pinfunction "2_2") (pintype "input"))
      (node (ref "R100") (pin "2") (pinfunction "2_2") (pintype "input"))
      (node (ref "R101") (pin "2") (pinfunction "2_2") (pintype "input"))
      (node (ref "U15") (pin "3") (pinfunction "1IN+_3") (pintype "unspecified"))
    )
    (net (code "140") (name "Net-(U15-1IN-)") (class "Default")
      (node (ref "C53") (pin "2") (pinfunction "2_2") (pintype "input"))
      (node (ref "R103") (pin "1") (pinfunction "1_1") (pintype "input"))
      (node (ref "R104") (pin "2") (pinfunction "2_2") (pintype "input"))
      (node (ref "U15") (pin "2") (pinfunction "1IN-_2") (pintype "unspecified"))
    )
    (net (code "141") (name "Net-(U15-1OUT)") (class "Default")
      (node (ref "C53") (pin "1") (pinfunction "1_1") (pintype "input"))
      (node (ref "R105") (pin "2") (pinfunction "2_2") (pintype "input"))
      (node (ref "R106") (pin "2") (pinfunction "2_2") (pintype "input"))
      (node (ref "U15") (pin "1") (pinfunction "1OUT_1") (pintype "unspecified"))
    )
    (net (code "142") (name "Net-(U15-2IN+)") (class "Default")
      (node (ref "R102") (pin "1") (pinfunction "1_1") (pintype "input"))
      (node (ref "R106") (pin "1") (pinfunction "1_1") (pintype "input"))
      (node (ref "U15") (pin "5") (pinfunction "2IN+_5") (pintype "unspecified"))
    )
    (net (code "143") (name "Net-(U15-2IN-)") (class "Default")
      (node (ref "C54") (pin "1") (pinfunction "1_1") (pintype "input"))
      (node (ref "R107") (pin "1") (pinfunction "1_1") (pintype "input"))
      (node (ref "R108") (pin "2") (pinfunction "2_2") (pintype "input"))
      (node (ref "U15") (pin "6") (pinfunction "2IN-_6") (pintype "unspecified"))
    )
    (net (code "144") (name "Net-(U15-2OUT)") (class "Default")
      (node (ref "C54") (pin "2") (pinfunction "2_2") (pintype "input"))
      (node (ref "R103") (pin "2") (pinfunction "2_2") (pintype "input"))
      (node (ref "R108") (pin "1") (pinfunction "1_1") (pintype "input"))
      (node (ref "U15") (pin "7") (pinfunction "2OUT_7") (pintype "unspecified"))
    )
    (net (code "145") (name "Net-(U16-+INB)") (class "Default")
      (node (ref "R120") (pin "2") (pinfunction "2_2") (pintype "input"))
      (node (ref "U16") (pin "5") (pinfunction "+INB_5") (pintype "unspecified"))
    )
    (net (code "146") (name "Net-(U16--INA)") (class "Default")
      (node (ref "R120") (pin "1") (pinfunction "1_1") (pintype "input"))
      (node (ref "R121") (pin "2") (pinfunction "2_2") (pintype "input"))
      (node (ref "U16") (pin "1") (pinfunction "OUTA_1") (pintype "unspecified"))
      (node (ref "U16") (pin "2") (pinfunction "-INA_2") (pintype "unspecified"))
    )
    (net (code "147") (name "Net-(U16--INB)") (class "Default")
      (node (ref "R132") (pin "1") (pinfunction "1_1") (pintype "input"))
      (node (ref "U16") (pin "6") (pinfunction "-INB_6") (pintype "unspecified"))
      (node (ref "U16") (pin "7") (pinfunction "OUTB_7") (pintype "unspecified"))
    )
    (net (code "148") (name "Net-(U17-+INA)") (class "Default")
      (node (ref "R118") (pin "1") (pinfunction "1_1") (pintype "input"))
      (node (ref "R94") (pin "2") (pinfunction "2_2") (pintype "input"))
      (node (ref "U17") (pin "3") (pinfunction "+INA_3") (pintype "unspecified"))
    )
    (net (code "149") (name "Net-(U17-+INB)") (class "Default")
      (node (ref "R119") (pin "2") (pinfunction "2_2") (pintype "input"))
      (node (ref "U17") (pin "1") (pinfunction "OUTA_1") (pintype "unspecified"))
      (node (ref "U17") (pin "5") (pinfunction "+INB_5") (pintype "unspecified"))
    )
    (net (code "150") (name "Net-(U17--INA)") (class "Default")
      (node (ref "R117") (pin "1") (pinfunction "1_1") (pintype "input"))
      (node (ref "R119") (pin "1") (pinfunction "1_1") (pintype "input"))
      (node (ref "U17") (pin "2") (pinfunction "-INA_2") (pintype "unspecified"))
    )
    (net (code "151") (name "Net-(U18-1IN+)") (class "Default")
      (node (ref "C60") (pin "2") (pinfunction "2_2") (pintype "input"))
      (node (ref "R131") (pin "2") (pinfunction "2_2") (pintype "input"))
      (node (ref "R132") (pin "2") (pinfunction "2_2") (pintype "input"))
      (node (ref "U18") (pin "3") (pinfunction "1IN+_3") (pintype "unspecified"))
    )
    (net (code "152") (name "Net-(U18-1IN-)") (class "Default")
      (node (ref "C59") (pin "2") (pinfunction "2_2") (pintype "input"))
      (node (ref "R128") (pin "2") (pinfunction "2_2") (pintype "input"))
      (node (ref "R129") (pin "1") (pinfunction "1_1") (pintype "input"))
      (node (ref "U18") (pin "2") (pinfunction "1IN-_2") (pintype "unspecified"))
    )
    (net (code "153") (name "Net-(U18-1OUT)") (class "Default")
      (node (ref "C59") (pin "1") (pinfunction "1_1") (pintype "input"))
      (node (ref "R126") (pin "2") (pinfunction "2_2") (pintype "input"))
      (node (ref "R127") (pin "2") (pinfunction "2_2") (pintype "input"))
      (node (ref "U18") (pin "1") (pinfunction "1OUT_1") (pintype "unspecified"))
    )
    (net (code "154") (name "Net-(U18-2IN+)") (class "Default")
      (node (ref "R126") (pin "1") (pinfunction "1_1") (pintype "input"))
      (node (ref "R130") (pin "1") (pinfunction "1_1") (pintype "input"))
      (node (ref "U18") (pin "5") (pinfunction "2IN+_5") (pintype "unspecified"))
    )
    (net (code "155") (name "Net-(U18-2IN-)") (class "Default")
      (node (ref "C58") (pin "1") (pinfunction "1_1") (pintype "input"))
      (node (ref "R124") (pin "2") (pinfunction "2_2") (pintype "input"))
      (node (ref "R125") (pin "1") (pinfunction "1_1") (pintype "input"))
      (node (ref "U18") (pin "6") (pinfunction "2IN-_6") (pintype "unspecified"))
    )
    (net (code "156") (name "Net-(U18-2OUT)") (class "Default")
      (node (ref "C58") (pin "2") (pinfunction "2_2") (pintype "input"))
      (node (ref "R124") (pin "1") (pinfunction "1_1") (pintype "input"))
      (node (ref "R129") (pin "2") (pinfunction "2_2") (pintype "input"))
      (node (ref "U18") (pin "7") (pinfunction "2OUT_7") (pintype "unspecified"))
    )
    (net (code "157") (name "Net-(U51-COUT)") (class "Default")
      (node (ref "C130") (pin "1") (pinfunction "1_1") (pintype "input"))
      (node (ref "U51") (pin "5") (pinfunction "COUT_5") (pintype "unspecified"))
    )
    (net (code "158") (name "Net-(U51-DISCH)") (class "Default")
      (node (ref "C128") (pin "1") (pinfunction "1_1") (pintype "input"))
      (node (ref "U51") (pin "7") (pinfunction "DISCH_7") (pintype "unspecified"))
    )
    (net (code "159") (name "Net-(U51-OUT)") (class "Default")
      (node (ref "R340") (pin "2") (pinfunction "2_2") (pintype "input"))
      (node (ref "R345") (pin "1") (pinfunction "1_1") (pintype "input"))
      (node (ref "U51") (pin "3") (pinfunction "OUT_3") (pintype "unspecified"))
    )
    (net (code "160") (name "Net-(U51-THRES)") (class "Default")
      (node (ref "C129") (pin "1") (pinfunction "1_1") (pintype "input"))
      (node (ref "R43") (pin "2") (pinfunction "2_2") (pintype "input"))
      (node (ref "U51") (pin "2") (pinfunction "TRIG_2") (pintype "unspecified"))
      (node (ref "U51") (pin "6") (pinfunction "THRES_6") (pintype "unspecified"))
    )
    (net (code "161") (name "Net-(U58-COUT)") (class "Default")
      (node (ref "C151") (pin "2") (pinfunction "2_2") (pintype "input"))
      (node (ref "U58") (pin "5") (pinfunction "COUT_5") (pintype "unspecified"))
    )
    (net (code "162") (name "Net-(U58-DISCH)") (class "Default")
      (node (ref "R348") (pin "1") (pinfunction "1_1") (pintype "input"))
      (node (ref "R358") (pin "2") (pinfunction "2_2") (pintype "input"))
      (node (ref "U58") (pin "7") (pinfunction "DISCH_7") (pintype "unspecified"))
    )
    (net (code "163") (name "Net-(U58-OUT)") (class "Default")
      (node (ref "R337") (pin "1") (pinfunction "1_1") (pintype "input"))
      (node (ref "R354") (pin "2") (pinfunction "2_2") (pintype "input"))
      (node (ref "U58") (pin "3") (pinfunction "OUT_3") (pintype "unspecified"))
    )
    (net (code "164") (name "Net-(U58-RST)") (class "Default")
      (node (ref "C142") (pin "1") (pinfunction "1_1") (pintype "input"))
      (node (ref "R340") (pin "1") (pinfunction "1_1") (pintype "input"))
      (node (ref "R359") (pin "1") (pinfunction "1_1") (pintype "input"))
      (node (ref "U58") (pin "4") (pinfunction "RST_4") (pintype "unspecified"))
    )
    (net (code "165") (name "Net-(U58-THRES)") (class "Default")
      (node (ref "C29") (pin "2") (pinfunction "2_2") (pintype "input"))
      (node (ref "R358") (pin "1") (pinfunction "1_1") (pintype "input"))
      (node (ref "U58") (pin "2") (pinfunction "TRIG_2") (pintype "unspecified"))
      (node (ref "U58") (pin "6") (pinfunction "THRES_6") (pintype "unspecified"))
    )
    (net (code "166") (name "Net-(U59-COUT)") (class "Default")
      (node (ref "C152") (pin "2") (pinfunction "2_2") (pintype "input"))
      (node (ref "U59") (pin "5") (pinfunction "COUT_5") (pintype "unspecified"))
    )
    (net (code "167") (name "Net-(U59-DISCH)") (class "Default")
      (node (ref "R349") (pin "1") (pinfunction "1_1") (pintype "input"))
      (node (ref "R357") (pin "2") (pinfunction "2_2") (pintype "input"))
      (node (ref "U59") (pin "7") (pinfunction "DISCH_7") (pintype "unspecified"))
    )
    (net (code "168") (name "Net-(U59-OUT)") (class "Default")
      (node (ref "R338") (pin "1") (pinfunction "1_1") (pintype "input"))
      (node (ref "R356") (pin "2") (pinfunction "2_2") (pintype "input"))
      (node (ref "U59") (pin "3") (pinfunction "OUT_3") (pintype "unspecified"))
    )
    (net (code "169") (name "Net-(U59-RST)") (class "Default")
      (node (ref "C143") (pin "1") (pinfunction "1_1") (pintype "input"))
      (node (ref "R341") (pin "1") (pinfunction "1_1") (pintype "input"))
      (node (ref "R360") (pin "1") (pinfunction "1_1") (pintype "input"))
      (node (ref "U59") (pin "4") (pinfunction "RST_4") (pintype "unspecified"))
    )
    (net (code "170") (name "Net-(U59-THRES)") (class "Default")
      (node (ref "C30") (pin "2") (pinfunction "2_2") (pintype "input"))
      (node (ref "R357") (pin "1") (pinfunction "1_1") (pintype "input"))
      (node (ref "U59") (pin "2") (pinfunction "TRIG_2") (pintype "unspecified"))
      (node (ref "U59") (pin "6") (pinfunction "THRES_6") (pintype "unspecified"))
    )
    (net (code "171") (name "P0-0") (class "Default")
      (node (ref "C19") (pin "2") (pinfunction "2_2") (pintype "input"))
      (node (ref "C22") (pin "2") (pinfunction "2_2") (pintype "input"))
      (node (ref "C36") (pin "2") (pinfunction "2_2") (pintype "input"))
      (node (ref "C39") (pin "2") (pinfunction "2_2") (pintype "input"))
      (node (ref "C46") (pin "2") (pinfunction "2_2") (pintype "input"))
      (node (ref "C48") (pin "2") (pinfunction "2_2") (pintype "input"))
      (node (ref "CN1") (pin "1") (pinfunction "1_1") (pintype "unspecified"))
      (node (ref "CN11") (pin "2") (pinfunction "2_2") (pintype "unspecified"))
      (node (ref "CN13") (pin "2") (pinfunction "2_2") (pintype "unspecified"))
      (node (ref "CN14") (pin "2") (pinfunction "2_2") (pintype "unspecified"))
      (node (ref "CN15") (pin "2") (pinfunction "2_2") (pintype "unspecified"))
      (node (ref "CN16") (pin "2") (pinfunction "2_2") (pintype "unspecified"))
      (node (ref "CN17") (pin "2") (pinfunction "2_2") (pintype "unspecified"))
      (node (ref "CN22") (pin "2") (pinfunction "2_2") (pintype "unspecified"))
      (node (ref "CN24") (pin "2") (pinfunction "2_2") (pintype "unspecified"))
      (node (ref "D13") (pin "1") (pinfunction "C_1") (pintype "unspecified"))
      (node (ref "D14") (pin "1") (pinfunction "C_1") (pintype "unspecified"))
      (node (ref "D19") (pin "1") (pinfunction "C_1") (pintype "unspecified"))
      (node (ref "D31") (pin "1") (pinfunction "C_1") (pintype "unspecified"))
      (node (ref "Q11") (pin "2") (pinfunction "S_2") (pintype "unspecified"))
      (node (ref "R1") (pin "1") (pinfunction "1_1") (pintype "input"))
      (node (ref "R10") (pin "2") (pinfunction "2_2") (pintype "input"))
      (node (ref "R11") (pin "1") (pinfunction "1_1") (pintype "input"))
      (node (ref "R12") (pin "1") (pinfunction "1_1") (pintype "input"))
      (node (ref "R15") (pin "2") (pinfunction "2_2") (pintype "input"))
      (node (ref "R153") (pin "1") (pinfunction "1_1") (pintype "input"))
      (node (ref "R362") (pin "2") (pinfunction "2_2") (pintype "input"))
      (node (ref "R46") (pin "1") (pinfunction "1_1") (pintype "input"))
      (node (ref "R47") (pin "1") (pinfunction "1_1") (pintype "input"))
      (node (ref "R48") (pin "1") (pinfunction "1_1") (pintype "input"))
      (node (ref "R50") (pin "2") (pinfunction "2_2") (pintype "input"))
      (node (ref "R55") (pin "2") (pinfunction "2_2") (pintype "input"))
      (node (ref "R56") (pin "2") (pinfunction "2_2") (pintype "input"))
      (node (ref "R6") (pin "2") (pinfunction "2_2") (pintype "input"))
      (node (ref "R61") (pin "1") (pinfunction "1_1") (pintype "input"))
      (node (ref "R62") (pin "2") (pinfunction "2_2") (pintype "input"))
      (node (ref "R65") (pin "1") (pinfunction "1_1") (pintype "input"))
      (node (ref "R67") (pin "1") (pinfunction "1_1") (pintype "input"))
      (node (ref "R91") (pin "1") (pinfunction "1_1") (pintype "input"))
      (node (ref "U10") (pin "1") (pinfunction "VIN_1") (pintype "unspecified"))
      (node (ref "U15") (pin "8") (pinfunction "VCC_8") (pintype "unspecified"))
      (node (ref "U18") (pin "8") (pinfunction "VCC_8") (pintype "unspecified"))
      (node (ref "U9") (pin "1") (pinfunction "Vin_1") (pintype "unspecified"))
    )
    (net (code "172") (name "P0-2") (class "Default")
      (node (ref "C1") (pin "2") (pinfunction "2_2") (pintype "input"))
      (node (ref "CN1") (pin "3") (pinfunction "3_3") (pintype "unspecified"))
      (node (ref "D10") (pin "1") (pinfunction "C_1") (pintype "unspecified"))
      (node (ref "D17") (pin "1") (pinfunction "C_1") (pintype "unspecified"))
      (node (ref "D18") (pin "1") (pinfunction "C_1") (pintype "unspecified"))
      (node (ref "Q5") (pin "1") (pinfunction "B_1") (pintype "unspecified"))
      (node (ref "R341") (pin "2") (pinfunction "2_2") (pintype "input"))
      (node (ref "R346") (pin "1") (pinfunction "1_1") (pintype "input"))
      (node (ref "R71") (pin "1") (pinfunction "1_1") (pintype "input"))
      (node (ref "R76") (pin "2") (pinfunction "2_2") (pintype "input"))
      (node (ref "R81") (pin "1") (pinfunction "1_1") (pintype "input"))
      (node (ref "R88") (pin "2") (pinfunction "2_2") (pintype "input"))
    )
    (net (code "173") (name "PICORUN") (class "Default")
      (node (ref "SW1") (pin "2") (pinfunction "2_2") (pintype "unspecified"))
      (node (ref "U11") (pin "30") (pinfunction "RUN_30") (pintype "unspecified"))
    )
    (net (code "174") (name "RST0") (class "Default")
      (node (ref "C55") (pin "2") (pinfunction "2_2") (pintype "unspecified"))
      (node (ref "Q20") (pin "2") (pinfunction "S_2") (pintype "unspecified"))
      (node (ref "R116") (pin "2") (pinfunction "2_2") (pintype "input"))
      (node (ref "R122") (pin "2") (pinfunction "2_2") (pintype "input"))
      (node (ref "U16") (pin "3") (pinfunction "+INA_3") (pintype "unspecified"))
    )
    (net (code "175") (name "RST1") (class "Default")
      (node (ref "C35") (pin "2") (pinfunction "2_2") (pintype "unspecified"))
      (node (ref "Q19") (pin "2") (pinfunction "S_2") (pintype "unspecified"))
      (node (ref "R113") (pin "2") (pinfunction "2_2") (pintype "input"))
      (node (ref "R95") (pin "2") (pinfunction "2_2") (pintype "input"))
      (node (ref "U14") (pin "3") (pinfunction "+INA_3") (pintype "unspecified"))
    )
    (net (code "176") (name "RTU_A") (class "Default")
      (node (ref "CN8") (pin "2") (pinfunction "2_2") (pintype "unspecified"))
      (node (ref "R41") (pin "2") (pinfunction "2_2") (pintype "input"))
      (node (ref "R42") (pin "2") (pinfunction "2_2") (pintype "input"))
      (node (ref "U5") (pin "6") (pinfunction "A_6") (pintype "unspecified"))
    )
    (net (code "177") (name "RTU_B") (class "Default")
      (node (ref "CN8") (pin "1") (pinfunction "1_1") (pintype "unspecified"))
      (node (ref "R39") (pin "2") (pinfunction "2_2") (pintype "input"))
      (node (ref "SJ1") (pin "1") (pinfunction "1_1") (pintype "unspecified"))
      (node (ref "U5") (pin "7") (pinfunction "B_7") (pintype "unspecified"))
    )
    (net (code "178") (name "SCL") (class "Default")
      (node (ref "R31") (pin "1") (pinfunction "1_1") (pintype "input"))
      (node (ref "U1") (pin "6") (pinfunction "SCL_6") (pintype "unspecified"))
      (node (ref "U11") (pin "12") (pinfunction "GP9_12") (pintype "unspecified"))
      (node (ref "U2") (pin "6") (pinfunction "SCL_6") (pintype "unspecified"))
      (node (ref "U6") (pin "23") (pinfunction "SCL_23") (pintype "unspecified"))
      (node (ref "U7") (pin "6") (pinfunction "SCL_6") (pintype "unspecified"))
    )
    (net (code "179") (name "SDA") (class "Default")
      (node (ref "R32") (pin "1") (pinfunction "1_1") (pintype "input"))
      (node (ref "U1") (pin "7") (pinfunction "SDA_7") (pintype "unspecified"))
      (node (ref "U11") (pin "11") (pinfunction "GP8_11") (pintype "unspecified"))
      (node (ref "U2") (pin "7") (pinfunction "SDA_7") (pintype "unspecified"))
      (node (ref "U6") (pin "24") (pinfunction "SDA_24") (pintype "unspecified"))
      (node (ref "U7") (pin "5") (pinfunction "SDA_5") (pintype "unspecified"))
    )
    (net (code "180") (name "SLV01_GND") (class "Default")
      (node (ref "C37") (pin "1") (pinfunction "1_1") (pintype "input"))
      (node (ref "C38") (pin "2") (pinfunction "2_2") (pintype "input"))
      (node (ref "CN22") (pin "1") (pinfunction "1_1") (pintype "unspecified"))
      (node (ref "D19") (pin "2") (pinfunction "A_2") (pintype "unspecified"))
      (node (ref "LED5") (pin "2") (pinfunction "K_2") (pintype "unspecified"))
      (node (ref "Q4") (pin "2") (pinfunction "C_2") (pintype "unspecified"))
    )
    (net (code "181") (name "SLV02_GND") (class "Default")
      (node (ref "C18") (pin "1") (pinfunction "1_1") (pintype "input"))
      (node (ref "C40") (pin "2") (pinfunction "2_2") (pintype "input"))
      (node (ref "CN14") (pin "1") (pinfunction "1_1") (pintype "unspecified"))
      (node (ref "D13") (pin "2") (pinfunction "A_2") (pintype "unspecified"))
      (node (ref "LED6") (pin "2") (pinfunction "K_2") (pintype "unspecified"))
      (node (ref "Q1") (pin "2") (pinfunction "C_2") (pintype "unspecified"))
    )
    (net (code "182") (name "SLV03_GND") (class "Default")
      (node (ref "C42") (pin "2") (pinfunction "2_2") (pintype "input"))
      (node (ref "C43") (pin "1") (pinfunction "1_1") (pintype "input"))
      (node (ref "CN15") (pin "1") (pinfunction "1_1") (pintype "unspecified"))
      (node (ref "D14") (pin "2") (pinfunction "A_2") (pintype "unspecified"))
      (node (ref "LED2") (pin "2") (pinfunction "K_2") (pintype "unspecified"))
      (node (ref "Q3") (pin "2") (pinfunction "C_2") (pintype "unspecified"))
    )
    (net (code "183") (name "SLV04_GND") (class "Default")
      (node (ref "C45") (pin "2") (pinfunction "2_2") (pintype "input"))
      (node (ref "C47") (pin "1") (pinfunction "1_1") (pintype "input"))
      (node (ref "CN16") (pin "1") (pinfunction "1_1") (pintype "unspecified"))
      (node (ref "D31") (pin "2") (pinfunction "A_2") (pintype "unspecified"))
      (node (ref "LED13") (pin "2") (pinfunction "K_2") (pintype "unspecified"))
      (node (ref "Q12") (pin "2") (pinfunction "C_2") (pintype "unspecified"))
    )
    (net (code "184") (name "SNS0") (class "Default")
      (node (ref "C57") (pin "1") (pinfunction "1_1") (pintype "input"))
      (node (ref "CN23") (pin "2") (pinfunction "2_2") (pintype "unspecified"))
    )
    (net (code "185") (name "SNS1") (class "Default")
      (node (ref "C12") (pin "1") (pinfunction "1_1") (pintype "input"))
      (node (ref "CN21") (pin "2") (pinfunction "2_2") (pintype "unspecified"))
    )
    (net (code "186") (name "SPI 1 CSn") (class "Default")
      (node (ref "H1") (pin "4") (pinfunction "CS_4") (pintype "unspecified"))
      (node (ref "U11") (pin "17") (pinfunction "GP13_17") (pintype "unspecified"))
    )
    (net (code "187") (name "SPI 1 SCK") (class "Default")
      (node (ref "H1") (pin "5") (pinfunction "CLK_5") (pintype "unspecified"))
      (node (ref "U11") (pin "14") (pinfunction "GP10_14") (pintype "unspecified"))
    )
    (net (code "188") (name "SPI 1 TX") (class "Default")
      (node (ref "H1") (pin "3") (pinfunction "DIN_3") (pintype "unspecified"))
      (node (ref "U11") (pin "15") (pinfunction "GP11_15") (pintype "unspecified"))
    )
    (net (code "189") (name "VBUS") (class "Default")
      (node (ref "C32") (pin "1") (pinfunction "1_1") (pintype "input"))
      (node (ref "D24") (pin "2") (pinfunction "A_2") (pintype "unspecified"))
      (node (ref "U11") (pin "40") (pinfunction "VBUS_40") (pintype "unspecified"))
    )
    (net (code "190") (name "unconnected-(CN3-Pad0)") (class "Default")
      (node (ref "CN3") (pin "0") (pinfunction "0_0") (pintype "unspecified+no_connect"))
    )
    (net (code "191") (name "unconnected-(CN4-Pad0)") (class "Default")
      (node (ref "CN4") (pin "0") (pinfunction "0_0") (pintype "unspecified+no_connect"))
    )
    (net (code "192") (name "unconnected-(CN5-Pad0)") (class "Default")
      (node (ref "CN5") (pin "0") (pinfunction "0_0") (pintype "unspecified+no_connect"))
    )
    (net (code "193") (name "unconnected-(CN6-Pad0)") (class "Default")
      (node (ref "CN6") (pin "0") (pinfunction "0_0") (pintype "unspecified+no_connect"))
    )
    (net (code "194") (name "unconnected-(CN7-Pad0)") (class "Default")
      (node (ref "CN7") (pin "0") (pinfunction "0_0") (pintype "unspecified+no_connect"))
    )
    (net (code "195") (name "unconnected-(CN12-Pad0)") (class "Default")
      (node (ref "CN12") (pin "0") (pinfunction "0_0") (pintype "unspecified+no_connect"))
    )
    (net (code "196") (name "unconnected-(H1-CLK-Pad6)") (class "Default")
      (node (ref "H1") (pin "6") (pinfunction "CLK_6") (pintype "unspecified+no_connect"))
    )
    (net (code "197") (name "unconnected-(H1-DOUT-Pad8)") (class "Default")
      (node (ref "H1") (pin "8") (pinfunction "DOUT_8") (pintype "unspecified+no_connect"))
    )
    (net (code "198") (name "unconnected-(H1-GND-Pad9)") (class "Default")
      (node (ref "H1") (pin "9") (pinfunction "GND_9") (pintype "unspecified+no_connect"))
    )
    (net (code "199") (name "unconnected-(H1-LODA-Pad7)") (class "Default")
      (node (ref "H1") (pin "7") (pinfunction "LODA_7") (pintype "unspecified+no_connect"))
    )
    (net (code "200") (name "unconnected-(H1-VCC-Pad10)") (class "Default")
      (node (ref "H1") (pin "10") (pinfunction "VCC_10") (pintype "unspecified+no_connect"))
    )
    (net (code "201") (name "unconnected-(SW1-Pad1)") (class "Default")
      (node (ref "SW1") (pin "1") (pinfunction "1_1") (pintype "unspecified+no_connect"))
    )
    (net (code "202") (name "unconnected-(SW1-Pad3)") (class "Default")
      (node (ref "SW1") (pin "3") (pinfunction "3_3") (pintype "unspecified+no_connect"))
    )
    (net (code "203") (name "unconnected-(U1-CRITICAL-Pad9)") (class "Default")
      (node (ref "U1") (pin "9") (pinfunction "CRITICAL_9") (pintype "unspecified+no_connect"))
    )
    (net (code "204") (name "unconnected-(U1-PAD-Pad17)") (class "Default")
      (node (ref "U1") (pin "17") (pinfunction "PAD_17") (pintype "unspecified+no_connect"))
    )
    (net (code "205") (name "unconnected-(U1-PV-Pad10)") (class "Default")
      (node (ref "U1") (pin "10") (pinfunction "PV_10") (pintype "unspecified+no_connect"))
    )
    (net (code "206") (name "unconnected-(U1-TC-Pad13)") (class "Default")
      (node (ref "U1") (pin "13") (pinfunction "TC_13") (pintype "unspecified+no_connect"))
    )
    (net (code "207") (name "unconnected-(U1-WARNING-Pad8)") (class "Default")
      (node (ref "U1") (pin "8") (pinfunction "WARNING_8") (pintype "unspecified+no_connect"))
    )
    (net (code "208") (name "unconnected-(U2-CRITICAL-Pad9)") (class "Default")
      (node (ref "U2") (pin "9") (pinfunction "CRITICAL_9") (pintype "unspecified+no_connect"))
    )
    (net (code "209") (name "unconnected-(U2-PAD-Pad17)") (class "Default")
      (node (ref "U2") (pin "17") (pinfunction "PAD_17") (pintype "unspecified+no_connect"))
    )
    (net (code "210") (name "unconnected-(U2-PV-Pad10)") (class "Default")
      (node (ref "U2") (pin "10") (pinfunction "PV_10") (pintype "unspecified+no_connect"))
    )
    (net (code "211") (name "unconnected-(U2-TC-Pad13)") (class "Default")
      (node (ref "U2") (pin "13") (pinfunction "TC_13") (pintype "unspecified+no_connect"))
    )
    (net (code "212") (name "unconnected-(U2-WARNING-Pad8)") (class "Default")
      (node (ref "U2") (pin "8") (pinfunction "WARNING_8") (pintype "unspecified+no_connect"))
    )
    (net (code "213") (name "unconnected-(U6-AUX_CL-Pad7)") (class "Default")
      (node (ref "U6") (pin "7") (pinfunction "AUX_CL_7") (pintype "unspecified+no_connect"))
    )
    (net (code "214") (name "unconnected-(U6-AUX_DA-Pad6)") (class "Default")
      (node (ref "U6") (pin "6") (pinfunction "AUX_DA_6") (pintype "unspecified+no_connect"))
    )
    (net (code "215") (name "unconnected-(U6-INT-Pad12)") (class "Default")
      (node (ref "U6") (pin "12") (pinfunction "INT_12") (pintype "unspecified+no_connect"))
    )
    (net (code "216") (name "unconnected-(U6-NC-Pad2)") (class "Default")
      (node (ref "U6") (pin "2") (pinfunction "NC_2") (pintype "unspecified+no_connect"))
    )
    (net (code "217") (name "unconnected-(U6-NC-Pad3)") (class "Default")
      (node (ref "U6") (pin "3") (pinfunction "NC_3") (pintype "unspecified+no_connect"))
    )
    (net (code "218") (name "unconnected-(U6-NC-Pad4)") (class "Default")
      (node (ref "U6") (pin "4") (pinfunction "NC_4") (pintype "unspecified+no_connect"))
    )
    (net (code "219") (name "unconnected-(U6-NC-Pad5)") (class "Default")
      (node (ref "U6") (pin "5") (pinfunction "NC_5") (pintype "unspecified+no_connect"))
    )
    (net (code "220") (name "unconnected-(U6-NC-Pad14)") (class "Default")
      (node (ref "U6") (pin "14") (pinfunction "NC_14") (pintype "unspecified+no_connect"))
    )
    (net (code "221") (name "unconnected-(U6-NC-Pad15)") (class "Default")
      (node (ref "U6") (pin "15") (pinfunction "NC_15") (pintype "unspecified+no_connect"))
    )
    (net (code "222") (name "unconnected-(U6-NC-Pad16)") (class "Default")
      (node (ref "U6") (pin "16") (pinfunction "NC_16") (pintype "unspecified+no_connect"))
    )
    (net (code "223") (name "unconnected-(U6-NC-Pad17)") (class "Default")
      (node (ref "U6") (pin "17") (pinfunction "NC_17") (pintype "unspecified+no_connect"))
    )
    (net (code "224") (name "unconnected-(U6-RESV-Pad19)") (class "Default")
      (node (ref "U6") (pin "19") (pinfunction "RESV_19") (pintype "unspecified+no_connect"))
    )
    (net (code "225") (name "unconnected-(U6-RESV-Pad21)") (class "Default")
      (node (ref "U6") (pin "21") (pinfunction "RESV_21") (pintype "unspecified+no_connect"))
    )
    (net (code "226") (name "unconnected-(U6-RESV-Pad22)") (class "Default")
      (node (ref "U6") (pin "22") (pinfunction "RESV_22") (pintype "unspecified+no_connect"))
    )
    (net (code "227") (name "unconnected-(U11-3V3_En-Pad37)") (class "Default")
      (node (ref "U11") (pin "37") (pinfunction "3V3_En_37") (pintype "unspecified+no_connect"))
    )
    (net (code "228") (name "unconnected-(U11-GP12-Pad16)") (class "Default")
      (node (ref "U11") (pin "16") (pinfunction "GP12_16") (pintype "unspecified+no_connect"))
    )
    (net (code "229") (name "unconnected-(U11-GP16{slash}MISO-Pad21)") (class "Default")
      (node (ref "U11") (pin "21") (pinfunction "GP16/MISO_21") (pintype "unspecified+no_connect"))
    )
    (net (code "230") (name "unconnected-(U11-GP17{slash}CSn-Pad22)") (class "Default")
      (node (ref "U11") (pin "22") (pinfunction "GP17/CSn_22") (pintype "unspecified+no_connect"))
    )
    (net (code "231") (name "unconnected-(U11-GP18{slash}SCLK-Pad24)") (class "Default")
      (node (ref "U11") (pin "24") (pinfunction "GP18/SCLK_24") (pintype "unspecified+no_connect"))
    )
    (net (code "232") (name "unconnected-(U11-GP19{slash}MOSI-Pad25)") (class "Default")
      (node (ref "U11") (pin "25") (pinfunction "GP19/MOSI_25") (pintype "unspecified+no_connect"))
    )
    (net (code "233") (name "unconnected-(U11-GP20{slash}RSTn-Pad26)") (class "Default")
      (node (ref "U11") (pin "26") (pinfunction "GP20/RSTn_26") (pintype "unspecified+no_connect"))
    )
    (net (code "234") (name "unconnected-(U11-GP21{slash}INTn-Pad27)") (class "Default")
      (node (ref "U11") (pin "27") (pinfunction "GP21/INTn_27") (pintype "unspecified+no_connect"))
    )
    (net (code "235") (name "unconnected-(U11-VRef-Pad35)") (class "Default")
      (node (ref "U11") (pin "35") (pinfunction "VRef_35") (pintype "unspecified+no_connect"))
    )
  )
)
